# shimboard_revC_V4.net
KiCad netlist of a schematic drawn in EAGLE
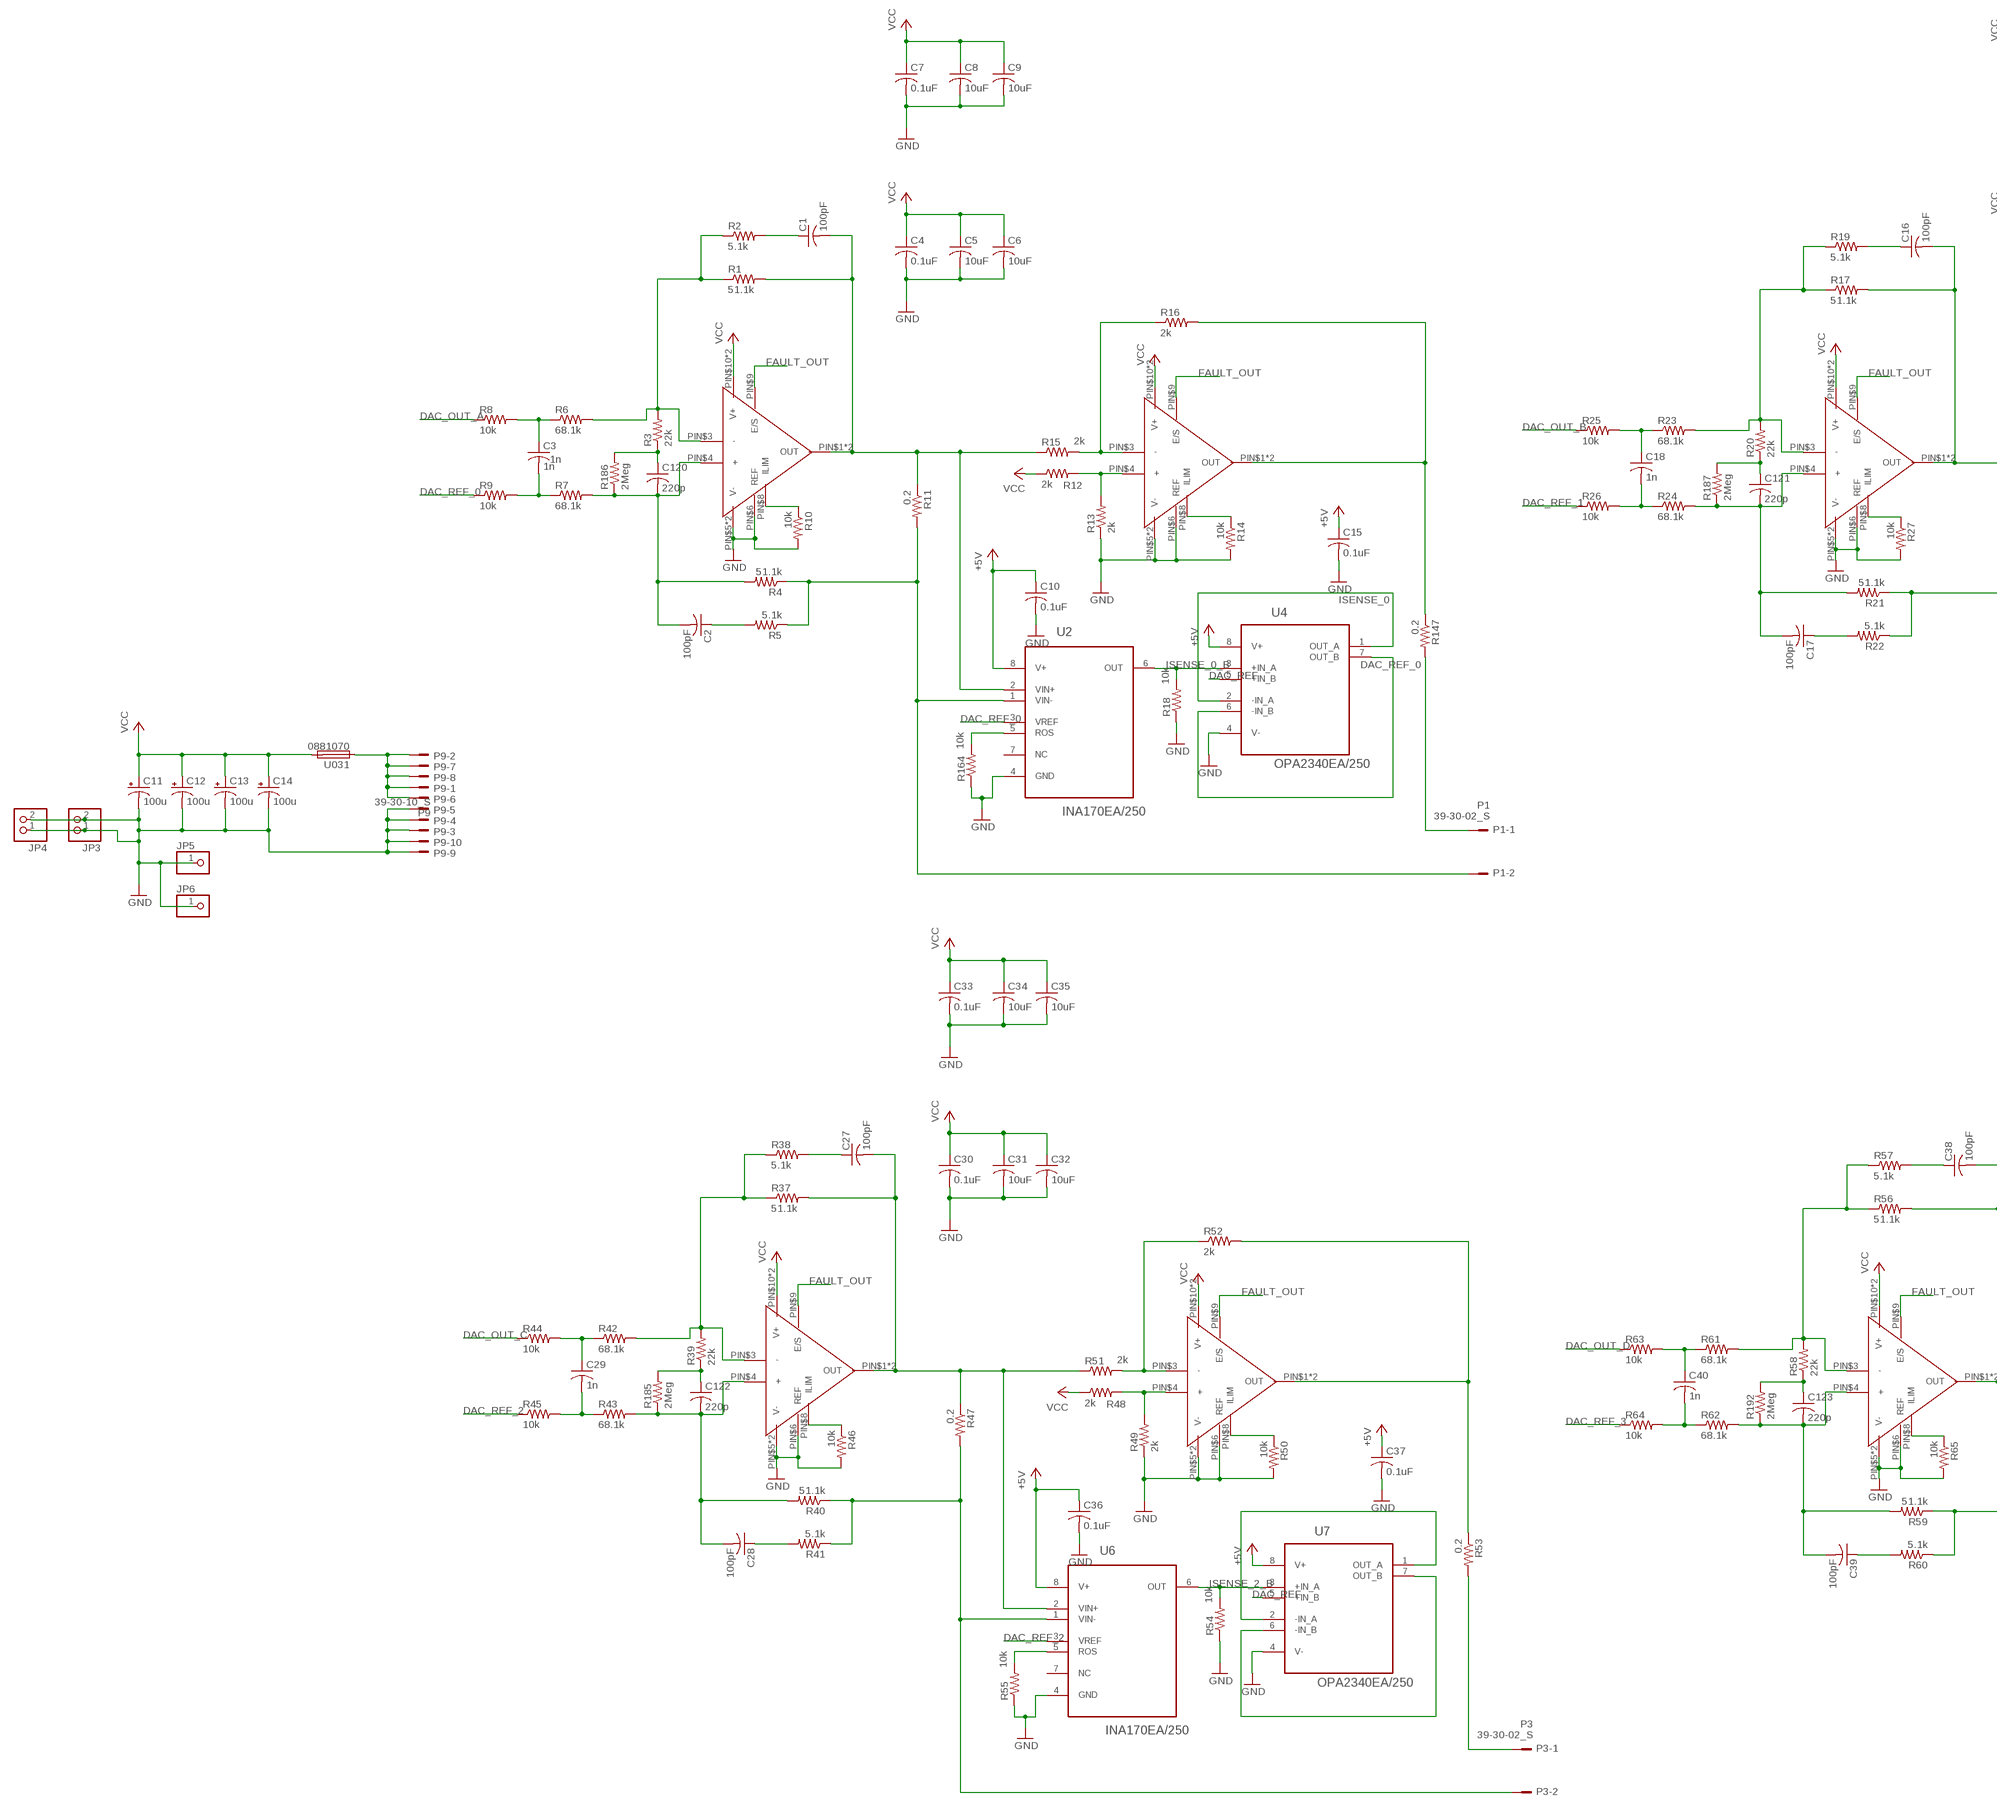
[diagram p0: schematic, sheet 1, part 1 of 3]
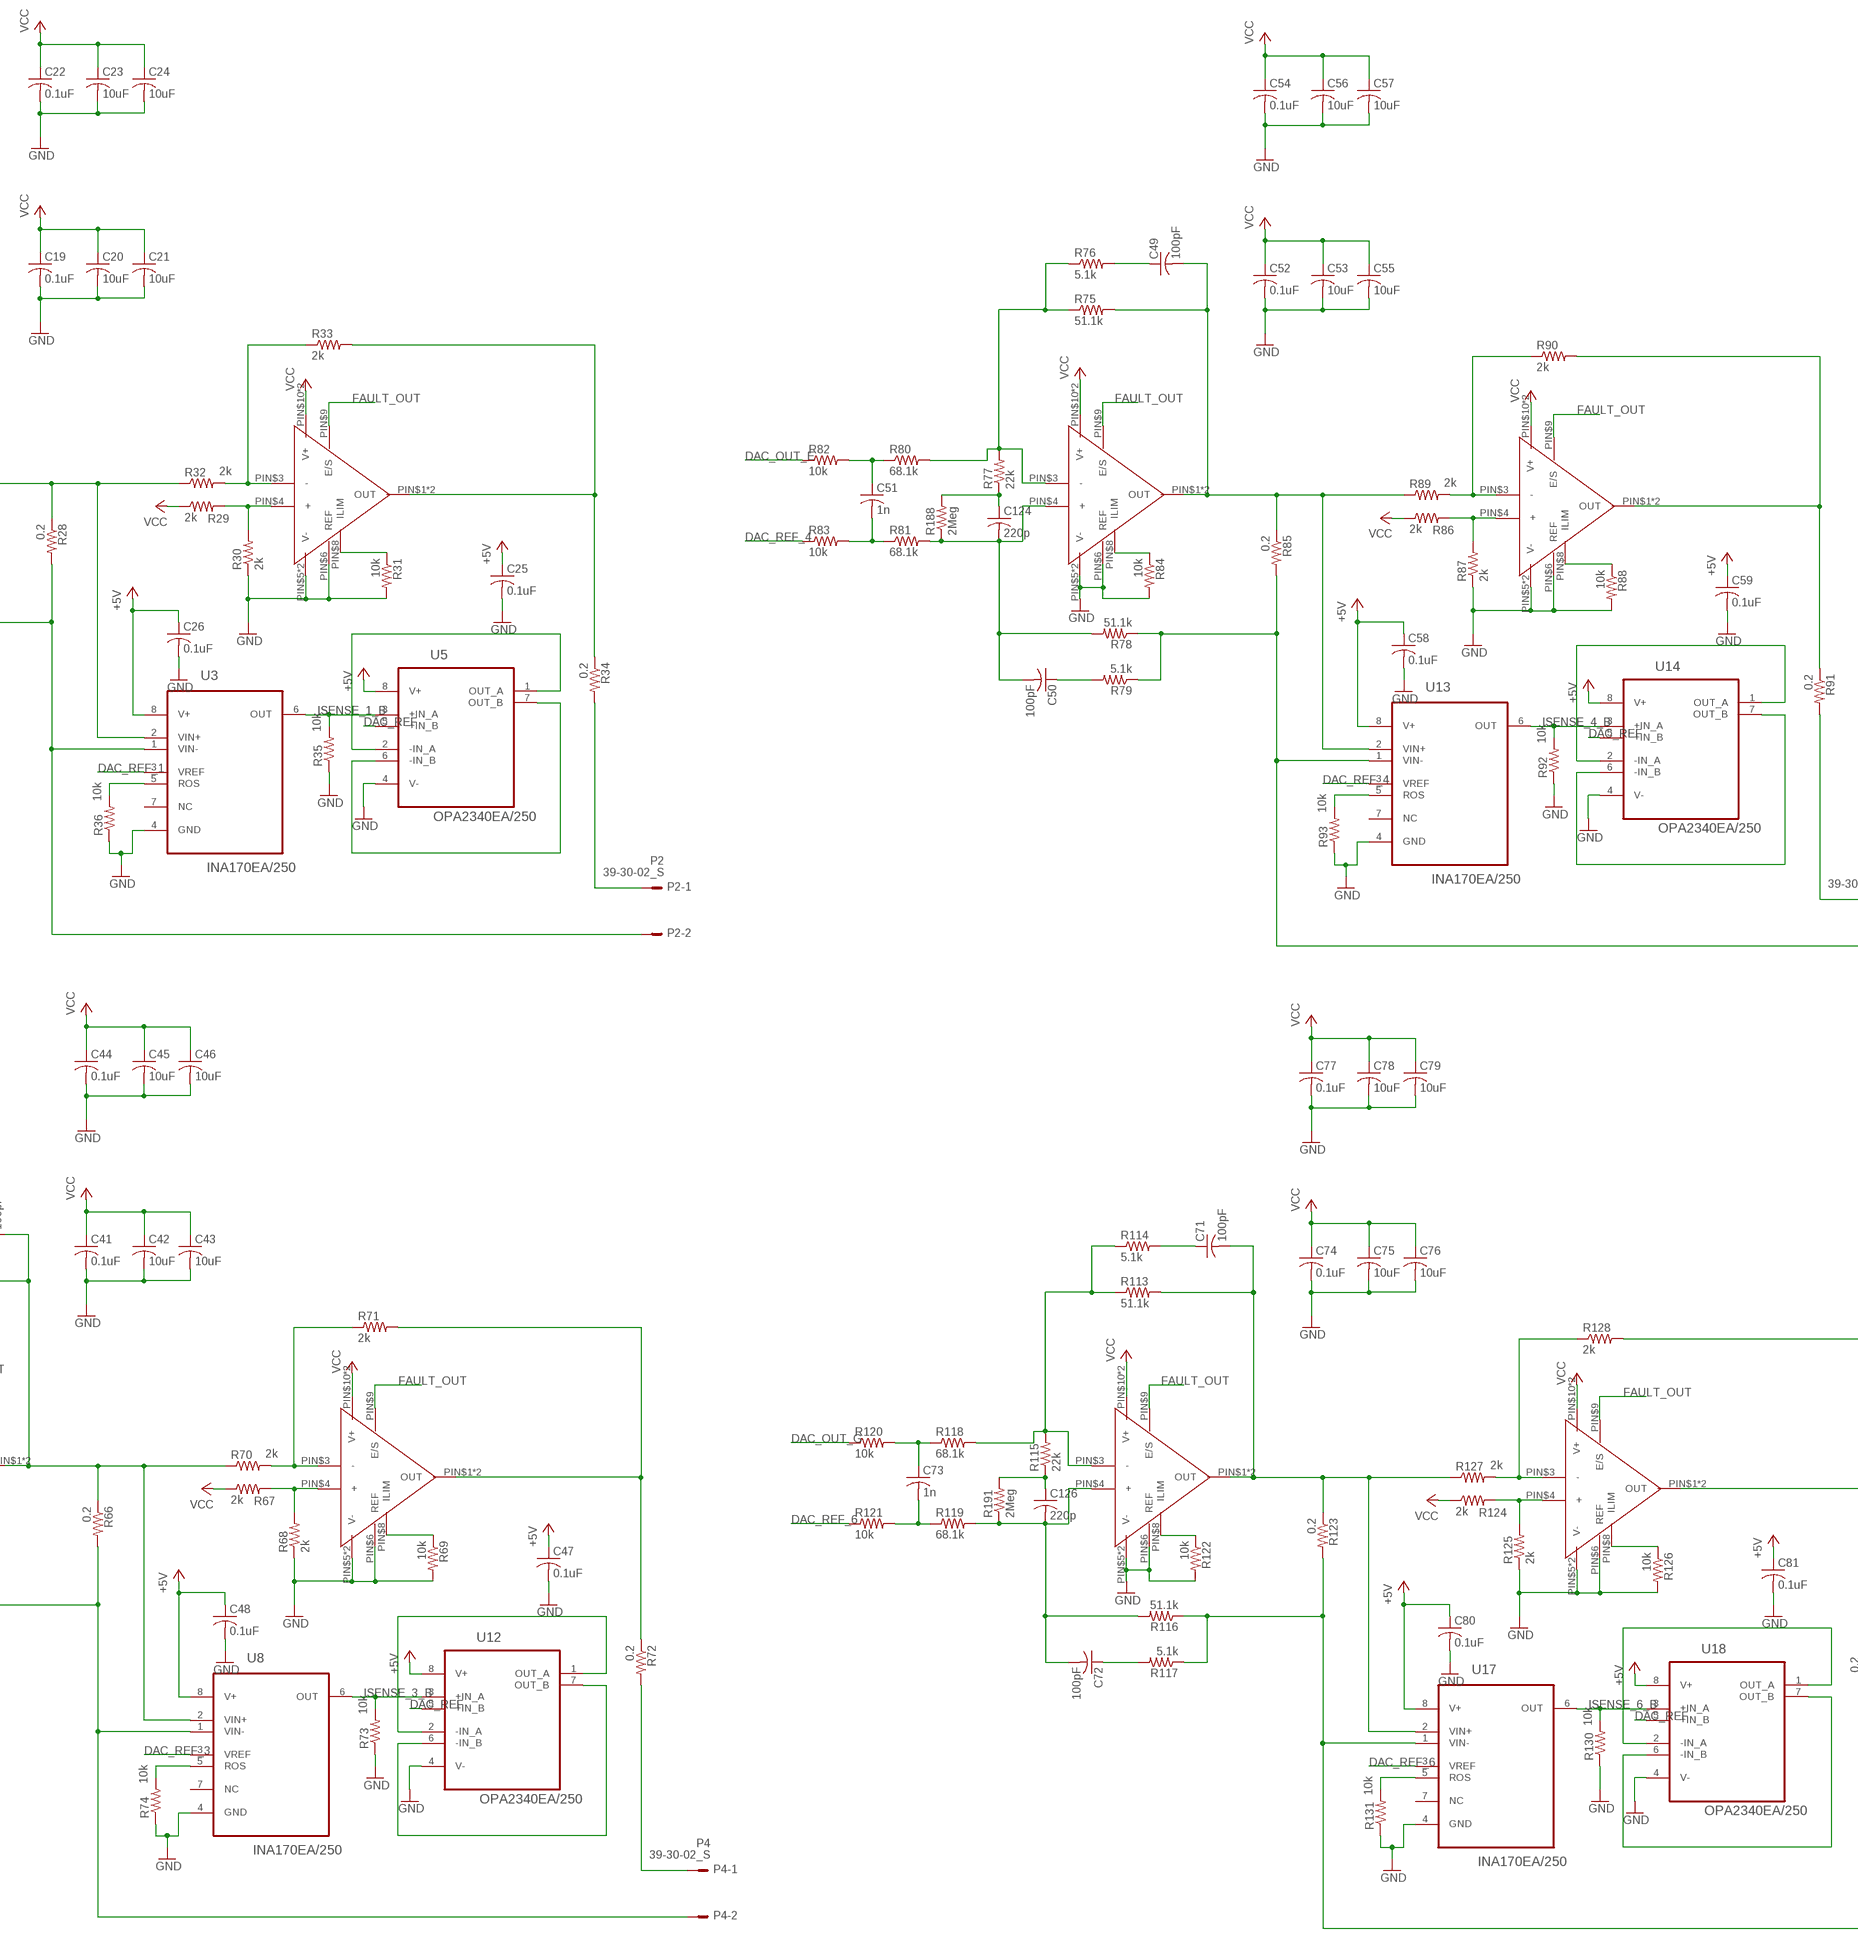
[diagram p1: schematic, sheet 1, part 2 of 3]
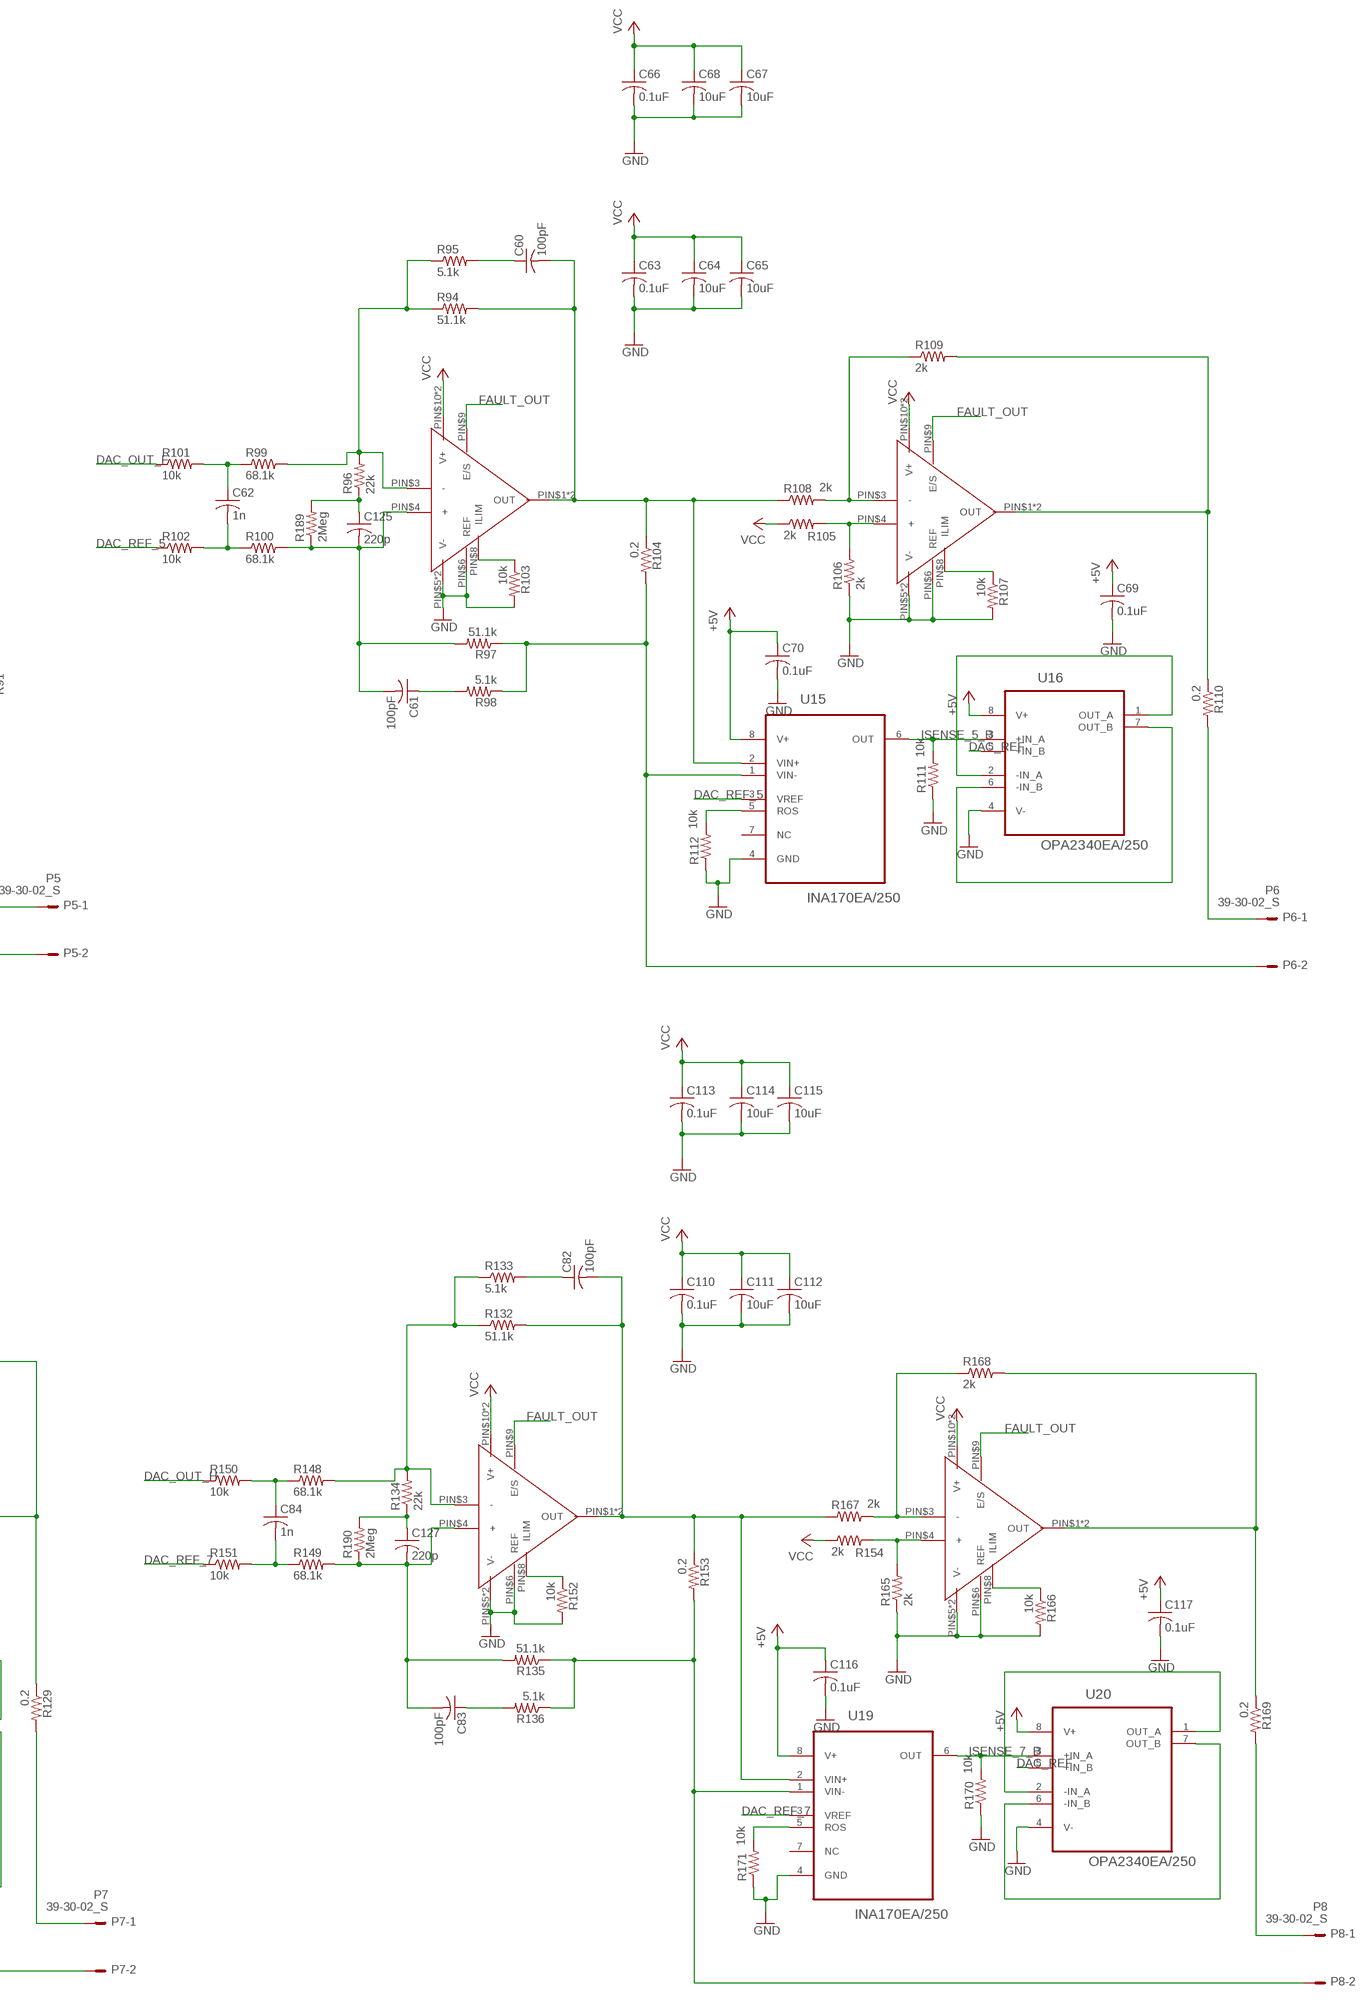
[diagram p2: schematic, sheet 1, part 3 of 3]
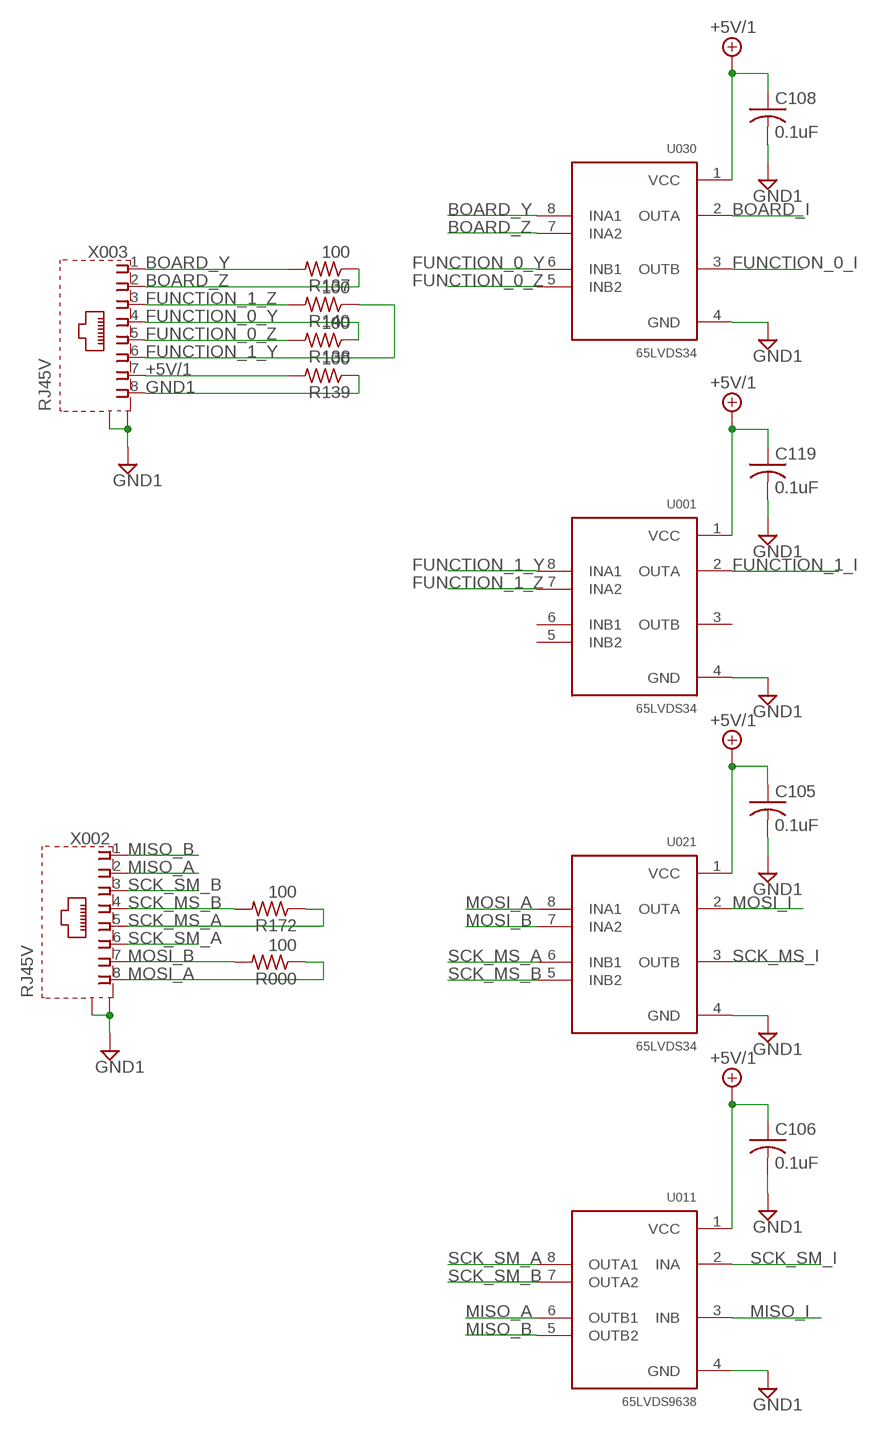
[diagram p3: schematic, sheet 2, part 1 of 2]
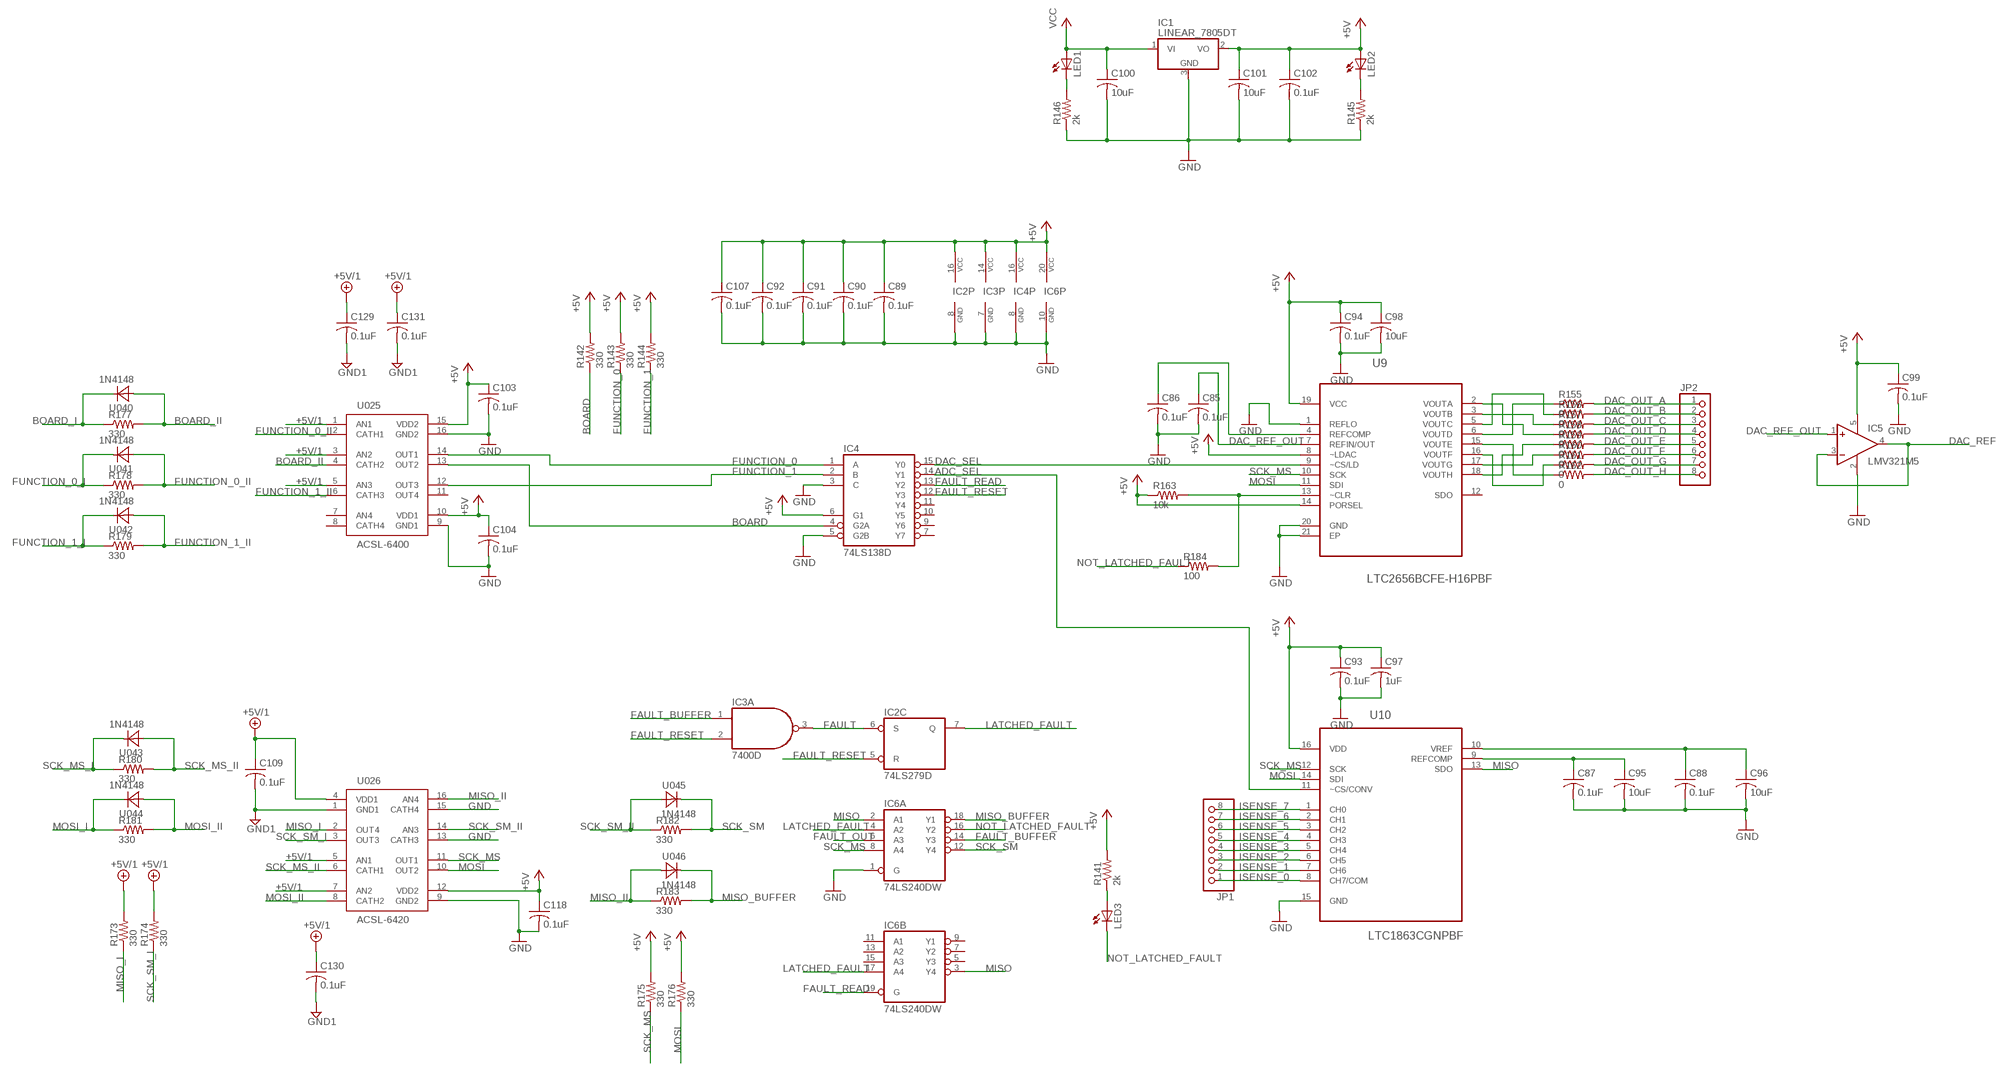
[diagram p4: schematic, sheet 2, part 2 of 2]

(export (version "E")
  (design (tool "Eeschema 10.0.6"))
  (components
    (comp (ref "C1")
      (value "100pF")
      (footprint "eagle-import:C0805")
      (libsource (lib "eagle-import") (part "C-USC0805"))
    )
    (comp (ref "C2")
      (value "100pF")
      (footprint "eagle-import:C0805")
      (libsource (lib "eagle-import") (part "C-USC0805"))
    )
    (comp (ref "C3")
      (value "1n")
      (footprint "eagle-import:C0805")
      (fields (field (name "SPICEPREFIX") "C") (field (name "SPICEPREFIX_1") "1n"))
      (libsource (lib "eagle-import") (part "C-USC0805"))
    )
    (comp (ref "C4")
      (value "0.1uF")
      (footprint "eagle-import:C0805")
      (libsource (lib "eagle-import") (part "C-USC0805"))
    )
    (comp (ref "C5")
      (value "10uF")
      (footprint "eagle-import:C1206")
      (libsource (lib "eagle-import") (part "C-USC1206"))
    )
    (comp (ref "C6")
      (value "10uF")
      (footprint "eagle-import:C1206")
      (libsource (lib "eagle-import") (part "C-USC1206"))
    )
    (comp (ref "C7")
      (value "0.1uF")
      (footprint "eagle-import:C0805")
      (libsource (lib "eagle-import") (part "C-USC0805"))
    )
    (comp (ref "C8")
      (value "10uF")
      (footprint "eagle-import:C1206")
      (libsource (lib "eagle-import") (part "C-USC1206"))
    )
    (comp (ref "C9")
      (value "10uF")
      (footprint "eagle-import:C1206")
      (libsource (lib "eagle-import") (part "C-USC1206"))
    )
    (comp (ref "C10")
      (value "0.1uF")
      (footprint "eagle-import:C0805")
      (libsource (lib "eagle-import") (part "C-USC0805"))
    )
    (comp (ref "C11")
      (value "100u")
      (footprint "eagle-import:D_7343-31W")
      (libsource (lib "eagle-import") (part "CPOL-USD/7343-31W"))
    )
    (comp (ref "C12")
      (value "100u")
      (footprint "eagle-import:D_7343-31W")
      (libsource (lib "eagle-import") (part "CPOL-USD/7343-31W"))
    )
    (comp (ref "C13")
      (value "100u")
      (footprint "eagle-import:D_7343-31W")
      (libsource (lib "eagle-import") (part "CPOL-USD/7343-31W"))
    )
    (comp (ref "C14")
      (value "100u")
      (footprint "eagle-import:D_7343-31W")
      (libsource (lib "eagle-import") (part "CPOL-USD/7343-31W"))
    )
    (comp (ref "C15")
      (value "0.1uF")
      (footprint "eagle-import:C0805")
      (libsource (lib "eagle-import") (part "C-USC0805"))
    )
    (comp (ref "C16")
      (value "100pF")
      (footprint "eagle-import:C0805")
      (libsource (lib "eagle-import") (part "C-USC0805"))
    )
    (comp (ref "C17")
      (value "100pF")
      (footprint "eagle-import:C0805")
      (libsource (lib "eagle-import") (part "C-USC0805"))
    )
    (comp (ref "C18")
      (value "1n")
      (footprint "eagle-import:C0805")
      (libsource (lib "eagle-import") (part "C-USC0805"))
    )
    (comp (ref "C19")
      (value "0.1uF")
      (footprint "eagle-import:C0805")
      (libsource (lib "eagle-import") (part "C-USC0805"))
    )
    (comp (ref "C20")
      (value "10uF")
      (footprint "eagle-import:C1206")
      (libsource (lib "eagle-import") (part "C-USC1206"))
    )
    (comp (ref "C21")
      (value "10uF")
      (footprint "eagle-import:C1206")
      (libsource (lib "eagle-import") (part "C-USC1206"))
    )
    (comp (ref "C22")
      (value "0.1uF")
      (footprint "eagle-import:C0805")
      (libsource (lib "eagle-import") (part "C-USC0805"))
    )
    (comp (ref "C23")
      (value "10uF")
      (footprint "eagle-import:C1206")
      (libsource (lib "eagle-import") (part "C-USC1206"))
    )
    (comp (ref "C24")
      (value "10uF")
      (footprint "eagle-import:C1206")
      (libsource (lib "eagle-import") (part "C-USC1206"))
    )
    (comp (ref "C25")
      (value "0.1uF")
      (footprint "eagle-import:C0805")
      (libsource (lib "eagle-import") (part "C-USC0805"))
    )
    (comp (ref "C26")
      (value "0.1uF")
      (footprint "eagle-import:C0805")
      (libsource (lib "eagle-import") (part "C-USC0805"))
    )
    (comp (ref "C27")
      (value "100pF")
      (footprint "eagle-import:C0805")
      (libsource (lib "eagle-import") (part "C-USC0805"))
    )
    (comp (ref "C28")
      (value "100pF")
      (footprint "eagle-import:C0805")
      (libsource (lib "eagle-import") (part "C-USC0805"))
    )
    (comp (ref "C29")
      (value "1n")
      (footprint "eagle-import:C0805")
      (libsource (lib "eagle-import") (part "C-USC0805"))
    )
    (comp (ref "C30")
      (value "0.1uF")
      (footprint "eagle-import:C0805")
      (libsource (lib "eagle-import") (part "C-USC0805"))
    )
    (comp (ref "C31")
      (value "10uF")
      (footprint "eagle-import:C1206")
      (libsource (lib "eagle-import") (part "C-USC1206"))
    )
    (comp (ref "C32")
      (value "10uF")
      (footprint "eagle-import:C1206")
      (libsource (lib "eagle-import") (part "C-USC1206"))
    )
    (comp (ref "C33")
      (value "0.1uF")
      (footprint "eagle-import:C0805")
      (libsource (lib "eagle-import") (part "C-USC0805"))
    )
    (comp (ref "C34")
      (value "10uF")
      (footprint "eagle-import:C1206")
      (libsource (lib "eagle-import") (part "C-USC1206"))
    )
    (comp (ref "C35")
      (value "10uF")
      (footprint "eagle-import:C1206")
      (libsource (lib "eagle-import") (part "C-USC1206"))
    )
    (comp (ref "C36")
      (value "0.1uF")
      (footprint "eagle-import:C0805")
      (libsource (lib "eagle-import") (part "C-USC0805"))
    )
    (comp (ref "C37")
      (value "0.1uF")
      (footprint "eagle-import:C0805")
      (libsource (lib "eagle-import") (part "C-USC0805"))
    )
    (comp (ref "C38")
      (value "100pF")
      (footprint "eagle-import:C0805")
      (libsource (lib "eagle-import") (part "C-USC0805"))
    )
    (comp (ref "C39")
      (value "100pF")
      (footprint "eagle-import:C0805")
      (libsource (lib "eagle-import") (part "C-USC0805"))
    )
    (comp (ref "C40")
      (value "1n")
      (footprint "eagle-import:C0805")
      (libsource (lib "eagle-import") (part "C-USC0805"))
    )
    (comp (ref "C41")
      (value "0.1uF")
      (footprint "eagle-import:C0805")
      (libsource (lib "eagle-import") (part "C-USC0805"))
    )
    (comp (ref "C42")
      (value "10uF")
      (footprint "eagle-import:C1206")
      (libsource (lib "eagle-import") (part "C-USC1206"))
    )
    (comp (ref "C43")
      (value "10uF")
      (footprint "eagle-import:C1206")
      (libsource (lib "eagle-import") (part "C-USC1206"))
    )
    (comp (ref "C44")
      (value "0.1uF")
      (footprint "eagle-import:C0805")
      (libsource (lib "eagle-import") (part "C-USC0805"))
    )
    (comp (ref "C45")
      (value "10uF")
      (footprint "eagle-import:C1206")
      (libsource (lib "eagle-import") (part "C-USC1206"))
    )
    (comp (ref "C46")
      (value "10uF")
      (footprint "eagle-import:C1206")
      (libsource (lib "eagle-import") (part "C-USC1206"))
    )
    (comp (ref "C47")
      (value "0.1uF")
      (footprint "eagle-import:C0805")
      (libsource (lib "eagle-import") (part "C-USC0805"))
    )
    (comp (ref "C48")
      (value "0.1uF")
      (footprint "eagle-import:C0805")
      (libsource (lib "eagle-import") (part "C-USC0805"))
    )
    (comp (ref "C49")
      (value "100pF")
      (footprint "eagle-import:C0805")
      (libsource (lib "eagle-import") (part "C-USC0805"))
    )
    (comp (ref "C50")
      (value "100pF")
      (footprint "eagle-import:C0805")
      (libsource (lib "eagle-import") (part "C-USC0805"))
    )
    (comp (ref "C51")
      (value "1n")
      (footprint "eagle-import:C0805")
      (libsource (lib "eagle-import") (part "C-USC0805"))
    )
    (comp (ref "C52")
      (value "0.1uF")
      (footprint "eagle-import:C0805")
      (libsource (lib "eagle-import") (part "C-USC0805"))
    )
    (comp (ref "C53")
      (value "10uF")
      (footprint "eagle-import:C1206")
      (libsource (lib "eagle-import") (part "C-USC1206"))
    )
    (comp (ref "C54")
      (value "0.1uF")
      (footprint "eagle-import:C0805")
      (libsource (lib "eagle-import") (part "C-USC0805"))
    )
    (comp (ref "C55")
      (value "10uF")
      (footprint "eagle-import:C1206")
      (libsource (lib "eagle-import") (part "C-USC1206"))
    )
    (comp (ref "C56")
      (value "10uF")
      (footprint "eagle-import:C1206")
      (libsource (lib "eagle-import") (part "C-USC1206"))
    )
    (comp (ref "C57")
      (value "10uF")
      (footprint "eagle-import:C1206")
      (libsource (lib "eagle-import") (part "C-USC1206"))
    )
    (comp (ref "C58")
      (value "0.1uF")
      (footprint "eagle-import:C0805")
      (libsource (lib "eagle-import") (part "C-USC0805"))
    )
    (comp (ref "C59")
      (value "0.1uF")
      (footprint "eagle-import:C0805")
      (libsource (lib "eagle-import") (part "C-USC0805"))
    )
    (comp (ref "C60")
      (value "100pF")
      (footprint "eagle-import:C0805")
      (libsource (lib "eagle-import") (part "C-USC0805"))
    )
    (comp (ref "C61")
      (value "100pF")
      (footprint "eagle-import:C0805")
      (libsource (lib "eagle-import") (part "C-USC0805"))
    )
    (comp (ref "C62")
      (value "1n")
      (footprint "eagle-import:C0805")
      (libsource (lib "eagle-import") (part "C-USC0805"))
    )
    (comp (ref "C63")
      (value "0.1uF")
      (footprint "eagle-import:C0805")
      (libsource (lib "eagle-import") (part "C-USC0805"))
    )
    (comp (ref "C64")
      (value "10uF")
      (footprint "eagle-import:C1206")
      (libsource (lib "eagle-import") (part "C-USC1206"))
    )
    (comp (ref "C65")
      (value "10uF")
      (footprint "eagle-import:C1206")
      (libsource (lib "eagle-import") (part "C-USC1206"))
    )
    (comp (ref "C66")
      (value "0.1uF")
      (footprint "eagle-import:C0805")
      (libsource (lib "eagle-import") (part "C-USC0805"))
    )
    (comp (ref "C67")
      (value "10uF")
      (footprint "eagle-import:C1206")
      (libsource (lib "eagle-import") (part "C-USC1206"))
    )
    (comp (ref "C68")
      (value "10uF")
      (footprint "eagle-import:C1206")
      (libsource (lib "eagle-import") (part "C-USC1206"))
    )
    (comp (ref "C69")
      (value "0.1uF")
      (footprint "eagle-import:C0805")
      (libsource (lib "eagle-import") (part "C-USC0805"))
    )
    (comp (ref "C70")
      (value "0.1uF")
      (footprint "eagle-import:C0805")
      (libsource (lib "eagle-import") (part "C-USC0805"))
    )
    (comp (ref "C71")
      (value "100pF")
      (footprint "eagle-import:C0805")
      (libsource (lib "eagle-import") (part "C-USC0805"))
    )
    (comp (ref "C72")
      (value "100pF")
      (footprint "eagle-import:C0805")
      (libsource (lib "eagle-import") (part "C-USC0805"))
    )
    (comp (ref "C73")
      (value "1n")
      (footprint "eagle-import:C0805")
      (libsource (lib "eagle-import") (part "C-USC0805"))
    )
    (comp (ref "C74")
      (value "0.1uF")
      (footprint "eagle-import:C0805")
      (libsource (lib "eagle-import") (part "C-USC0805"))
    )
    (comp (ref "C75")
      (value "10uF")
      (footprint "eagle-import:C1206")
      (libsource (lib "eagle-import") (part "C-USC1206"))
    )
    (comp (ref "C76")
      (value "10uF")
      (footprint "eagle-import:C1206")
      (libsource (lib "eagle-import") (part "C-USC1206"))
    )
    (comp (ref "C77")
      (value "0.1uF")
      (footprint "eagle-import:C0805")
      (libsource (lib "eagle-import") (part "C-USC0805"))
    )
    (comp (ref "C78")
      (value "10uF")
      (footprint "eagle-import:C1206")
      (libsource (lib "eagle-import") (part "C-USC1206"))
    )
    (comp (ref "C79")
      (value "10uF")
      (footprint "eagle-import:C1206")
      (libsource (lib "eagle-import") (part "C-USC1206"))
    )
    (comp (ref "C80")
      (value "0.1uF")
      (footprint "eagle-import:C0805")
      (libsource (lib "eagle-import") (part "C-USC0805"))
    )
    (comp (ref "C81")
      (value "0.1uF")
      (footprint "eagle-import:C0805")
      (libsource (lib "eagle-import") (part "C-USC0805"))
    )
    (comp (ref "C82")
      (value "100pF")
      (footprint "eagle-import:C0805")
      (libsource (lib "eagle-import") (part "C-USC0805"))
    )
    (comp (ref "C83")
      (value "100pF")
      (footprint "eagle-import:C0805")
      (libsource (lib "eagle-import") (part "C-USC0805"))
    )
    (comp (ref "C84")
      (value "1n")
      (footprint "eagle-import:C0805")
      (libsource (lib "eagle-import") (part "C-USC0805"))
    )
    (comp (ref "C110")
      (value "0.1uF")
      (footprint "eagle-import:C0805")
      (libsource (lib "eagle-import") (part "C-USC0805"))
    )
    (comp (ref "C111")
      (value "10uF")
      (footprint "eagle-import:C1206")
      (libsource (lib "eagle-import") (part "C-USC1206"))
    )
    (comp (ref "C112")
      (value "10uF")
      (footprint "eagle-import:C1206")
      (libsource (lib "eagle-import") (part "C-USC1206"))
    )
    (comp (ref "C113")
      (value "0.1uF")
      (footprint "eagle-import:C0805")
      (libsource (lib "eagle-import") (part "C-USC0805"))
    )
    (comp (ref "C114")
      (value "10uF")
      (footprint "eagle-import:C1206")
      (libsource (lib "eagle-import") (part "C-USC1206"))
    )
    (comp (ref "C115")
      (value "10uF")
      (footprint "eagle-import:C1206")
      (libsource (lib "eagle-import") (part "C-USC1206"))
    )
    (comp (ref "C116")
      (value "0.1uF")
      (footprint "eagle-import:C0805")
      (libsource (lib "eagle-import") (part "C-USC0805"))
    )
    (comp (ref "C117")
      (value "0.1uF")
      (footprint "eagle-import:C0805")
      (libsource (lib "eagle-import") (part "C-USC0805"))
    )
    (comp (ref "C120")
      (value "220p")
      (footprint "eagle-import:C0805")
      (libsource (lib "eagle-import") (part "C-USC0805"))
    )
    (comp (ref "C121")
      (value "220p")
      (footprint "eagle-import:C0805")
      (libsource (lib "eagle-import") (part "C-USC0805"))
    )
    (comp (ref "C122")
      (value "220p")
      (footprint "eagle-import:C0805")
      (libsource (lib "eagle-import") (part "C-USC0805"))
    )
    (comp (ref "C123")
      (value "220p")
      (footprint "eagle-import:C0805")
      (libsource (lib "eagle-import") (part "C-USC0805"))
    )
    (comp (ref "C124")
      (value "220p")
      (footprint "eagle-import:C0805")
      (libsource (lib "eagle-import") (part "C-USC0805"))
    )
    (comp (ref "C125")
      (value "220p")
      (footprint "eagle-import:C0805")
      (libsource (lib "eagle-import") (part "C-USC0805"))
    )
    (comp (ref "C126")
      (value "220p")
      (footprint "eagle-import:C0805")
      (libsource (lib "eagle-import") (part "C-USC0805"))
    )
    (comp (ref "C127")
      (value "220p")
      (footprint "eagle-import:C0805")
      (libsource (lib "eagle-import") (part "C-USC0805"))
    )
    (comp (ref "JP3")
      (value "PINHD-1X2")
      (footprint "eagle-import:1X02")
      (libsource (lib "eagle-import") (part "PINHD-1X2"))
    )
    (comp (ref "JP4")
      (value "PINHD-1X2")
      (footprint "eagle-import:1X02")
      (libsource (lib "eagle-import") (part "PINHD-1X2"))
    )
    (comp (ref "JP5")
      (value "PINHD-1X1")
      (footprint "eagle-import:1X01")
      (libsource (lib "eagle-import") (part "PINHD-1X1"))
    )
    (comp (ref "JP6")
      (value "PINHD-1X1")
      (footprint "eagle-import:1X01")
      (libsource (lib "eagle-import") (part "PINHD-1X1"))
    )
    (comp (ref "P1")
      (value "39-30-02_S")
      (footprint "eagle-import:39-30-_02_")
      (libsource (lib "eagle-import") (part "39-30-?02?_S"))
    )
    (comp (ref "P2")
      (value "39-30-02_S")
      (footprint "eagle-import:39-30-_02_")
      (libsource (lib "eagle-import") (part "39-30-?02?_S"))
    )
    (comp (ref "P3")
      (value "39-30-02_S")
      (footprint "eagle-import:39-30-_02_")
      (libsource (lib "eagle-import") (part "39-30-?02?_S"))
    )
    (comp (ref "P4")
      (value "39-30-02_S")
      (footprint "eagle-import:39-30-_02_")
      (libsource (lib "eagle-import") (part "39-30-?02?_S"))
    )
    (comp (ref "P5")
      (value "39-30-02_S")
      (footprint "eagle-import:39-30-_02_")
      (libsource (lib "eagle-import") (part "39-30-?02?_S"))
    )
    (comp (ref "P6")
      (value "39-30-02_S")
      (footprint "eagle-import:39-30-_02_")
      (libsource (lib "eagle-import") (part "39-30-?02?_S"))
    )
    (comp (ref "P7")
      (value "39-30-02_S")
      (footprint "eagle-import:39-30-_02_")
      (libsource (lib "eagle-import") (part "39-30-?02?_S"))
    )
    (comp (ref "P8")
      (value "39-30-02_S")
      (footprint "eagle-import:39-30-_02_")
      (libsource (lib "eagle-import") (part "39-30-?02?_S"))
    )
    (comp (ref "P9")
      (value "39-30-10_S")
      (footprint "eagle-import:39-30-_10_")
      (libsource (lib "eagle-import") (part "39-30-?10?_S"))
    )
    (comp (ref "R1")
      (value "51.1k")
      (footprint "eagle-import:R0805")
      (libsource (lib "eagle-import") (part "R-US_R0805"))
    )
    (comp (ref "R2")
      (value "5.1k")
      (footprint "eagle-import:R0805")
      (libsource (lib "eagle-import") (part "R-US_R0805"))
    )
    (comp (ref "R3")
      (value "22k")
      (footprint "eagle-import:R0805")
      (libsource (lib "eagle-import") (part "R-US_R0805"))
    )
    (comp (ref "R4")
      (value "51.1k")
      (footprint "eagle-import:R0805")
      (libsource (lib "eagle-import") (part "R-US_R0805"))
    )
    (comp (ref "R5")
      (value "5.1k")
      (footprint "eagle-import:R0805")
      (libsource (lib "eagle-import") (part "R-US_R0805"))
    )
    (comp (ref "R6")
      (value "68.1k")
      (footprint "eagle-import:R0805")
      (libsource (lib "eagle-import") (part "R-US_R0805"))
    )
    (comp (ref "R7")
      (value "68.1k")
      (footprint "eagle-import:R0805")
      (libsource (lib "eagle-import") (part "R-US_R0805"))
    )
    (comp (ref "R8")
      (value "10k")
      (footprint "eagle-import:R0805")
      (libsource (lib "eagle-import") (part "R-US_R0805"))
    )
    (comp (ref "R9")
      (value "10k")
      (footprint "eagle-import:R0805")
      (libsource (lib "eagle-import") (part "R-US_R0805"))
    )
    (comp (ref "R10")
      (value "10k")
      (footprint "eagle-import:R0805")
      (libsource (lib "eagle-import") (part "R-US_R0805"))
    )
    (comp (ref "R11")
      (value "0.2")
      (footprint "eagle-import:R4527")
      (libsource (lib "eagle-import") (part "R-US_R4527"))
    )
    (comp (ref "R12")
      (value "2k")
      (footprint "eagle-import:M0805")
      (libsource (lib "eagle-import") (part "R-US_M0805"))
    )
    (comp (ref "R13")
      (value "2k")
      (footprint "eagle-import:R0805")
      (libsource (lib "eagle-import") (part "R-US_R0805"))
    )
    (comp (ref "R14")
      (value "10k")
      (footprint "eagle-import:R0805")
      (libsource (lib "eagle-import") (part "R-US_R0805"))
    )
    (comp (ref "R15")
      (value "2k")
      (footprint "eagle-import:R0805")
      (libsource (lib "eagle-import") (part "R-US_R0805"))
    )
    (comp (ref "R16")
      (value "2k")
      (footprint "eagle-import:R0805")
      (libsource (lib "eagle-import") (part "R-US_R0805"))
    )
    (comp (ref "R17")
      (value "51.1k")
      (footprint "eagle-import:R0805")
      (libsource (lib "eagle-import") (part "R-US_R0805"))
    )
    (comp (ref "R18")
      (value "10k")
      (footprint "eagle-import:R0805")
      (libsource (lib "eagle-import") (part "R-US_R0805"))
    )
    (comp (ref "R19")
      (value "5.1k")
      (footprint "eagle-import:R0805")
      (libsource (lib "eagle-import") (part "R-US_R0805"))
    )
    (comp (ref "R20")
      (value "22k")
      (footprint "eagle-import:R0805")
      (libsource (lib "eagle-import") (part "R-US_R0805"))
    )
    (comp (ref "R21")
      (value "51.1k")
      (footprint "eagle-import:R0805")
      (libsource (lib "eagle-import") (part "R-US_R0805"))
    )
    (comp (ref "R22")
      (value "5.1k")
      (footprint "eagle-import:R0805")
      (libsource (lib "eagle-import") (part "R-US_R0805"))
    )
    (comp (ref "R23")
      (value "68.1k")
      (footprint "eagle-import:R0805")
      (libsource (lib "eagle-import") (part "R-US_R0805"))
    )
    (comp (ref "R24")
      (value "68.1k")
      (footprint "eagle-import:R0805")
      (libsource (lib "eagle-import") (part "R-US_R0805"))
    )
    (comp (ref "R25")
      (value "10k")
      (footprint "eagle-import:R0805")
      (libsource (lib "eagle-import") (part "R-US_R0805"))
    )
    (comp (ref "R26")
      (value "10k")
      (footprint "eagle-import:R0805")
      (libsource (lib "eagle-import") (part "R-US_R0805"))
    )
    (comp (ref "R27")
      (value "10k")
      (footprint "eagle-import:R0805")
      (libsource (lib "eagle-import") (part "R-US_R0805"))
    )
    (comp (ref "R28")
      (value "0.2")
      (footprint "eagle-import:R4527")
      (libsource (lib "eagle-import") (part "R-US_R4527"))
    )
    (comp (ref "R29")
      (value "2k")
      (footprint "eagle-import:M0805")
      (libsource (lib "eagle-import") (part "R-US_M0805"))
    )
    (comp (ref "R30")
      (value "2k")
      (footprint "eagle-import:R0805")
      (libsource (lib "eagle-import") (part "R-US_R0805"))
    )
    (comp (ref "R31")
      (value "10k")
      (footprint "eagle-import:R0805")
      (libsource (lib "eagle-import") (part "R-US_R0805"))
    )
    (comp (ref "R32")
      (value "2k")
      (footprint "eagle-import:R0805")
      (libsource (lib "eagle-import") (part "R-US_R0805"))
    )
    (comp (ref "R33")
      (value "2k")
      (footprint "eagle-import:R0805")
      (libsource (lib "eagle-import") (part "R-US_R0805"))
    )
    (comp (ref "R34")
      (value "0.2")
      (footprint "eagle-import:R4527")
      (libsource (lib "eagle-import") (part "R-US_R4527"))
    )
    (comp (ref "R35")
      (value "10k")
      (footprint "eagle-import:R0805")
      (libsource (lib "eagle-import") (part "R-US_R0805"))
    )
    (comp (ref "R36")
      (value "10k")
      (footprint "eagle-import:R0805")
      (libsource (lib "eagle-import") (part "R-US_R0805"))
    )
    (comp (ref "R37")
      (value "51.1k")
      (footprint "eagle-import:R0805")
      (libsource (lib "eagle-import") (part "R-US_R0805"))
    )
    (comp (ref "R38")
      (value "5.1k")
      (footprint "eagle-import:R0805")
      (libsource (lib "eagle-import") (part "R-US_R0805"))
    )
    (comp (ref "R39")
      (value "22k")
      (footprint "eagle-import:R0805")
      (libsource (lib "eagle-import") (part "R-US_R0805"))
    )
    (comp (ref "R40")
      (value "51.1k")
      (footprint "eagle-import:R0805")
      (libsource (lib "eagle-import") (part "R-US_R0805"))
    )
    (comp (ref "R41")
      (value "5.1k")
      (footprint "eagle-import:R0805")
      (libsource (lib "eagle-import") (part "R-US_R0805"))
    )
    (comp (ref "R42")
      (value "68.1k")
      (footprint "eagle-import:R0805")
      (libsource (lib "eagle-import") (part "R-US_R0805"))
    )
    (comp (ref "R43")
      (value "68.1k")
      (footprint "eagle-import:R0805")
      (libsource (lib "eagle-import") (part "R-US_R0805"))
    )
    (comp (ref "R44")
      (value "10k")
      (footprint "eagle-import:R0805")
      (libsource (lib "eagle-import") (part "R-US_R0805"))
    )
    (comp (ref "R45")
      (value "10k")
      (footprint "eagle-import:R0805")
      (libsource (lib "eagle-import") (part "R-US_R0805"))
    )
    (comp (ref "R46")
      (value "10k")
      (footprint "eagle-import:R0805")
      (libsource (lib "eagle-import") (part "R-US_R0805"))
    )
    (comp (ref "R47")
      (value "0.2")
      (footprint "eagle-import:R4527")
      (libsource (lib "eagle-import") (part "R-US_R4527"))
    )
    (comp (ref "R48")
      (value "2k")
      (footprint "eagle-import:M0805")
      (libsource (lib "eagle-import") (part "R-US_M0805"))
    )
    (comp (ref "R49")
      (value "2k")
      (footprint "eagle-import:R0805")
      (libsource (lib "eagle-import") (part "R-US_R0805"))
    )
    (comp (ref "R50")
      (value "10k")
      (footprint "eagle-import:R0805")
      (libsource (lib "eagle-import") (part "R-US_R0805"))
    )
    (comp (ref "R51")
      (value "2k")
      (footprint "eagle-import:R0805")
      (libsource (lib "eagle-import") (part "R-US_R0805"))
    )
    (comp (ref "R52")
      (value "2k")
      (footprint "eagle-import:R0805")
      (libsource (lib "eagle-import") (part "R-US_R0805"))
    )
    (comp (ref "R53")
      (value "0.2")
      (footprint "eagle-import:R4527")
      (libsource (lib "eagle-import") (part "R-US_R4527"))
    )
    (comp (ref "R54")
      (value "10k")
      (footprint "eagle-import:R0805")
      (libsource (lib "eagle-import") (part "R-US_R0805"))
    )
    (comp (ref "R55")
      (value "10k")
      (footprint "eagle-import:R0805")
      (libsource (lib "eagle-import") (part "R-US_R0805"))
    )
    (comp (ref "R56")
      (value "51.1k")
      (footprint "eagle-import:R0805")
      (libsource (lib "eagle-import") (part "R-US_R0805"))
    )
    (comp (ref "R57")
      (value "5.1k")
      (footprint "eagle-import:R0805")
      (libsource (lib "eagle-import") (part "R-US_R0805"))
    )
    (comp (ref "R58")
      (value "22k")
      (footprint "eagle-import:R0805")
      (libsource (lib "eagle-import") (part "R-US_R0805"))
    )
    (comp (ref "R59")
      (value "51.1k")
      (footprint "eagle-import:R0805")
      (libsource (lib "eagle-import") (part "R-US_R0805"))
    )
    (comp (ref "R60")
      (value "5.1k")
      (footprint "eagle-import:R0805")
      (libsource (lib "eagle-import") (part "R-US_R0805"))
    )
    (comp (ref "R61")
      (value "68.1k")
      (footprint "eagle-import:R0805")
      (libsource (lib "eagle-import") (part "R-US_R0805"))
    )
    (comp (ref "R62")
      (value "68.1k")
      (footprint "eagle-import:R0805")
      (libsource (lib "eagle-import") (part "R-US_R0805"))
    )
    (comp (ref "R63")
      (value "10k")
      (footprint "eagle-import:R0805")
      (libsource (lib "eagle-import") (part "R-US_R0805"))
    )
    (comp (ref "R64")
      (value "10k")
      (footprint "eagle-import:R0805")
      (libsource (lib "eagle-import") (part "R-US_R0805"))
    )
    (comp (ref "R65")
      (value "10k")
      (footprint "eagle-import:R0805")
      (libsource (lib "eagle-import") (part "R-US_R0805"))
    )
    (comp (ref "R66")
      (value "0.2")
      (footprint "eagle-import:R4527")
      (libsource (lib "eagle-import") (part "R-US_R4527"))
    )
    (comp (ref "R67")
      (value "2k")
      (footprint "eagle-import:M0805")
      (libsource (lib "eagle-import") (part "R-US_M0805"))
    )
    (comp (ref "R68")
      (value "2k")
      (footprint "eagle-import:R0805")
      (libsource (lib "eagle-import") (part "R-US_R0805"))
    )
    (comp (ref "R69")
      (value "10k")
      (footprint "eagle-import:R0805")
      (libsource (lib "eagle-import") (part "R-US_R0805"))
    )
    (comp (ref "R70")
      (value "2k")
      (footprint "eagle-import:R0805")
      (libsource (lib "eagle-import") (part "R-US_R0805"))
    )
    (comp (ref "R71")
      (value "2k")
      (footprint "eagle-import:R0805")
      (libsource (lib "eagle-import") (part "R-US_R0805"))
    )
    (comp (ref "R72")
      (value "0.2")
      (footprint "eagle-import:R4527")
      (libsource (lib "eagle-import") (part "R-US_R4527"))
    )
    (comp (ref "R73")
      (value "10k")
      (footprint "eagle-import:R0805")
      (libsource (lib "eagle-import") (part "R-US_R0805"))
    )
    (comp (ref "R74")
      (value "10k")
      (footprint "eagle-import:R0805")
      (libsource (lib "eagle-import") (part "R-US_R0805"))
    )
    (comp (ref "R75")
      (value "51.1k")
      (footprint "eagle-import:R0805")
      (libsource (lib "eagle-import") (part "R-US_R0805"))
    )
    (comp (ref "R76")
      (value "5.1k")
      (footprint "eagle-import:R0805")
      (libsource (lib "eagle-import") (part "R-US_R0805"))
    )
    (comp (ref "R77")
      (value "22k")
      (footprint "eagle-import:R0805")
      (libsource (lib "eagle-import") (part "R-US_R0805"))
    )
    (comp (ref "R78")
      (value "51.1k")
      (footprint "eagle-import:R0805")
      (libsource (lib "eagle-import") (part "R-US_R0805"))
    )
    (comp (ref "R79")
      (value "5.1k")
      (footprint "eagle-import:R0805")
      (libsource (lib "eagle-import") (part "R-US_R0805"))
    )
    (comp (ref "R80")
      (value "68.1k")
      (footprint "eagle-import:R0805")
      (libsource (lib "eagle-import") (part "R-US_R0805"))
    )
    (comp (ref "R81")
      (value "68.1k")
      (footprint "eagle-import:R0805")
      (libsource (lib "eagle-import") (part "R-US_R0805"))
    )
    (comp (ref "R82")
      (value "10k")
      (footprint "eagle-import:R0805")
      (libsource (lib "eagle-import") (part "R-US_R0805"))
    )
    (comp (ref "R83")
      (value "10k")
      (footprint "eagle-import:R0805")
      (libsource (lib "eagle-import") (part "R-US_R0805"))
    )
    (comp (ref "R84")
      (value "10k")
      (footprint "eagle-import:R0805")
      (libsource (lib "eagle-import") (part "R-US_R0805"))
    )
    (comp (ref "R85")
      (value "0.2")
      (footprint "eagle-import:R4527")
      (libsource (lib "eagle-import") (part "R-US_R4527"))
    )
    (comp (ref "R86")
      (value "2k")
      (footprint "eagle-import:M0805")
      (libsource (lib "eagle-import") (part "R-US_M0805"))
    )
    (comp (ref "R87")
      (value "2k")
      (footprint "eagle-import:R0805")
      (libsource (lib "eagle-import") (part "R-US_R0805"))
    )
    (comp (ref "R88")
      (value "10k")
      (footprint "eagle-import:R0805")
      (libsource (lib "eagle-import") (part "R-US_R0805"))
    )
    (comp (ref "R89")
      (value "2k")
      (footprint "eagle-import:R0805")
      (libsource (lib "eagle-import") (part "R-US_R0805"))
    )
    (comp (ref "R90")
      (value "2k")
      (footprint "eagle-import:R0805")
      (libsource (lib "eagle-import") (part "R-US_R0805"))
    )
    (comp (ref "R91")
      (value "0.2")
      (footprint "eagle-import:R4527")
      (libsource (lib "eagle-import") (part "R-US_R4527"))
    )
    (comp (ref "R92")
      (value "10k")
      (footprint "eagle-import:R0805")
      (libsource (lib "eagle-import") (part "R-US_R0805"))
    )
    (comp (ref "R93")
      (value "10k")
      (footprint "eagle-import:R0805")
      (libsource (lib "eagle-import") (part "R-US_R0805"))
    )
    (comp (ref "R94")
      (value "51.1k")
      (footprint "eagle-import:R0805")
      (libsource (lib "eagle-import") (part "R-US_R0805"))
    )
    (comp (ref "R95")
      (value "5.1k")
      (footprint "eagle-import:R0805")
      (libsource (lib "eagle-import") (part "R-US_R0805"))
    )
    (comp (ref "R96")
      (value "22k")
      (footprint "eagle-import:R0805")
      (libsource (lib "eagle-import") (part "R-US_R0805"))
    )
    (comp (ref "R97")
      (value "51.1k")
      (footprint "eagle-import:R0805")
      (libsource (lib "eagle-import") (part "R-US_R0805"))
    )
    (comp (ref "R98")
      (value "5.1k")
      (footprint "eagle-import:R0805")
      (libsource (lib "eagle-import") (part "R-US_R0805"))
    )
    (comp (ref "R99")
      (value "68.1k")
      (footprint "eagle-import:R0805")
      (libsource (lib "eagle-import") (part "R-US_R0805"))
    )
    (comp (ref "R100")
      (value "68.1k")
      (footprint "eagle-import:R0805")
      (libsource (lib "eagle-import") (part "R-US_R0805"))
    )
    (comp (ref "R101")
      (value "10k")
      (footprint "eagle-import:R0805")
      (libsource (lib "eagle-import") (part "R-US_R0805"))
    )
    (comp (ref "R102")
      (value "10k")
      (footprint "eagle-import:R0805")
      (libsource (lib "eagle-import") (part "R-US_R0805"))
    )
    (comp (ref "R103")
      (value "10k")
      (footprint "eagle-import:R0805")
      (libsource (lib "eagle-import") (part "R-US_R0805"))
    )
    (comp (ref "R104")
      (value "0.2")
      (footprint "eagle-import:R4527")
      (libsource (lib "eagle-import") (part "R-US_R4527"))
    )
    (comp (ref "R105")
      (value "2k")
      (footprint "eagle-import:M0805")
      (libsource (lib "eagle-import") (part "R-US_M0805"))
    )
    (comp (ref "R106")
      (value "2k")
      (footprint "eagle-import:R0805")
      (libsource (lib "eagle-import") (part "R-US_R0805"))
    )
    (comp (ref "R107")
      (value "10k")
      (footprint "eagle-import:R0805")
      (libsource (lib "eagle-import") (part "R-US_R0805"))
    )
    (comp (ref "R108")
      (value "2k")
      (footprint "eagle-import:R0805")
      (libsource (lib "eagle-import") (part "R-US_R0805"))
    )
    (comp (ref "R109")
      (value "2k")
      (footprint "eagle-import:R0805")
      (libsource (lib "eagle-import") (part "R-US_R0805"))
    )
    (comp (ref "R110")
      (value "0.2")
      (footprint "eagle-import:R4527")
      (libsource (lib "eagle-import") (part "R-US_R4527"))
    )
    (comp (ref "R111")
      (value "10k")
      (footprint "eagle-import:R0805")
      (libsource (lib "eagle-import") (part "R-US_R0805"))
    )
    (comp (ref "R112")
      (value "10k")
      (footprint "eagle-import:R0805")
      (libsource (lib "eagle-import") (part "R-US_R0805"))
    )
    (comp (ref "R113")
      (value "51.1k")
      (footprint "eagle-import:R0805")
      (libsource (lib "eagle-import") (part "R-US_R0805"))
    )
    (comp (ref "R114")
      (value "5.1k")
      (footprint "eagle-import:R0805")
      (libsource (lib "eagle-import") (part "R-US_R0805"))
    )
    (comp (ref "R115")
      (value "22k")
      (footprint "eagle-import:R0805")
      (libsource (lib "eagle-import") (part "R-US_R0805"))
    )
    (comp (ref "R116")
      (value "51.1k")
      (footprint "eagle-import:R0805")
      (libsource (lib "eagle-import") (part "R-US_R0805"))
    )
    (comp (ref "R117")
      (value "5.1k")
      (footprint "eagle-import:R0805")
      (libsource (lib "eagle-import") (part "R-US_R0805"))
    )
    (comp (ref "R118")
      (value "68.1k")
      (footprint "eagle-import:R0805")
      (libsource (lib "eagle-import") (part "R-US_R0805"))
    )
    (comp (ref "R119")
      (value "68.1k")
      (footprint "eagle-import:R0805")
      (libsource (lib "eagle-import") (part "R-US_R0805"))
    )
    (comp (ref "R120")
      (value "10k")
      (footprint "eagle-import:R0805")
      (libsource (lib "eagle-import") (part "R-US_R0805"))
    )
    (comp (ref "R121")
      (value "10k")
      (footprint "eagle-import:R0805")
      (libsource (lib "eagle-import") (part "R-US_R0805"))
    )
    (comp (ref "R122")
      (value "10k")
      (footprint "eagle-import:R0805")
      (libsource (lib "eagle-import") (part "R-US_R0805"))
    )
    (comp (ref "R123")
      (value "0.2")
      (footprint "eagle-import:R4527")
      (libsource (lib "eagle-import") (part "R-US_R4527"))
    )
    (comp (ref "R124")
      (value "2k")
      (footprint "eagle-import:M0805")
      (libsource (lib "eagle-import") (part "R-US_M0805"))
    )
    (comp (ref "R125")
      (value "2k")
      (footprint "eagle-import:R0805")
      (libsource (lib "eagle-import") (part "R-US_R0805"))
    )
    (comp (ref "R126")
      (value "10k")
      (footprint "eagle-import:R0805")
      (libsource (lib "eagle-import") (part "R-US_R0805"))
    )
    (comp (ref "R127")
      (value "2k")
      (footprint "eagle-import:R0805")
      (libsource (lib "eagle-import") (part "R-US_R0805"))
    )
    (comp (ref "R128")
      (value "2k")
      (footprint "eagle-import:R0805")
      (libsource (lib "eagle-import") (part "R-US_R0805"))
    )
    (comp (ref "R129")
      (value "0.2")
      (footprint "eagle-import:R4527")
      (libsource (lib "eagle-import") (part "R-US_R4527"))
    )
    (comp (ref "R130")
      (value "10k")
      (footprint "eagle-import:R0805")
      (libsource (lib "eagle-import") (part "R-US_R0805"))
    )
    (comp (ref "R131")
      (value "10k")
      (footprint "eagle-import:R0805")
      (libsource (lib "eagle-import") (part "R-US_R0805"))
    )
    (comp (ref "R132")
      (value "51.1k")
      (footprint "eagle-import:R0805")
      (libsource (lib "eagle-import") (part "R-US_R0805"))
    )
    (comp (ref "R133")
      (value "5.1k")
      (footprint "eagle-import:R0805")
      (libsource (lib "eagle-import") (part "R-US_R0805"))
    )
    (comp (ref "R134")
      (value "22k")
      (footprint "eagle-import:R0805")
      (libsource (lib "eagle-import") (part "R-US_R0805"))
    )
    (comp (ref "R135")
      (value "51.1k")
      (footprint "eagle-import:R0805")
      (libsource (lib "eagle-import") (part "R-US_R0805"))
    )
    (comp (ref "R136")
      (value "5.1k")
      (footprint "eagle-import:R0805")
      (libsource (lib "eagle-import") (part "R-US_R0805"))
    )
    (comp (ref "R147")
      (value "0.2")
      (footprint "eagle-import:R4527")
      (libsource (lib "eagle-import") (part "R-US_R4527"))
    )
    (comp (ref "R148")
      (value "68.1k")
      (footprint "eagle-import:R0805")
      (libsource (lib "eagle-import") (part "R-US_R0805"))
    )
    (comp (ref "R149")
      (value "68.1k")
      (footprint "eagle-import:R0805")
      (libsource (lib "eagle-import") (part "R-US_R0805"))
    )
    (comp (ref "R150")
      (value "10k")
      (footprint "eagle-import:R0805")
      (libsource (lib "eagle-import") (part "R-US_R0805"))
    )
    (comp (ref "R151")
      (value "10k")
      (footprint "eagle-import:R0805")
      (libsource (lib "eagle-import") (part "R-US_R0805"))
    )
    (comp (ref "R152")
      (value "10k")
      (footprint "eagle-import:R0805")
      (libsource (lib "eagle-import") (part "R-US_R0805"))
    )
    (comp (ref "R153")
      (value "0.2")
      (footprint "eagle-import:R4527")
      (libsource (lib "eagle-import") (part "R-US_R4527"))
    )
    (comp (ref "R154")
      (value "2k")
      (footprint "eagle-import:M0805")
      (libsource (lib "eagle-import") (part "R-US_M0805"))
    )
    (comp (ref "R164")
      (value "10k")
      (footprint "eagle-import:R0805")
      (libsource (lib "eagle-import") (part "R-US_R0805"))
    )
    (comp (ref "R165")
      (value "2k")
      (footprint "eagle-import:R0805")
      (libsource (lib "eagle-import") (part "R-US_R0805"))
    )
    (comp (ref "R166")
      (value "10k")
      (footprint "eagle-import:R0805")
      (libsource (lib "eagle-import") (part "R-US_R0805"))
    )
    (comp (ref "R167")
      (value "2k")
      (footprint "eagle-import:R0805")
      (libsource (lib "eagle-import") (part "R-US_R0805"))
    )
    (comp (ref "R168")
      (value "2k")
      (footprint "eagle-import:R0805")
      (libsource (lib "eagle-import") (part "R-US_R0805"))
    )
    (comp (ref "R169")
      (value "0.2")
      (footprint "eagle-import:R4527")
      (libsource (lib "eagle-import") (part "R-US_R4527"))
    )
    (comp (ref "R170")
      (value "10k")
      (footprint "eagle-import:R0805")
      (libsource (lib "eagle-import") (part "R-US_R0805"))
    )
    (comp (ref "R171")
      (value "10k")
      (footprint "eagle-import:R0805")
      (libsource (lib "eagle-import") (part "R-US_R0805"))
    )
    (comp (ref "R185")
      (value "2Meg")
      (footprint "eagle-import:R0805")
      (libsource (lib "eagle-import") (part "R-US_R0805"))
    )
    (comp (ref "R186")
      (value "2Meg")
      (footprint "eagle-import:R0805")
      (libsource (lib "eagle-import") (part "R-US_R0805"))
    )
    (comp (ref "R187")
      (value "2Meg")
      (footprint "eagle-import:R0805")
      (libsource (lib "eagle-import") (part "R-US_R0805"))
    )
    (comp (ref "R188")
      (value "2Meg")
      (footprint "eagle-import:R0805")
      (libsource (lib "eagle-import") (part "R-US_R0805"))
    )
    (comp (ref "R189")
      (value "2Meg")
      (footprint "eagle-import:R0805")
      (libsource (lib "eagle-import") (part "R-US_R0805"))
    )
    (comp (ref "R190")
      (value "2Meg")
      (footprint "eagle-import:R0805")
      (libsource (lib "eagle-import") (part "R-US_R0805"))
    )
    (comp (ref "R191")
      (value "2Meg")
      (footprint "eagle-import:R0805")
      (libsource (lib "eagle-import") (part "R-US_R0805"))
    )
    (comp (ref "R192")
      (value "2Meg")
      (footprint "eagle-import:R0805")
      (libsource (lib "eagle-import") (part "R-US_R0805"))
    )
    (comp (ref "U$1")
      (value "OPA549_HS677NOHS")
      (footprint "eagle-import:OPA549")
      (libsource (lib "eagle-import") (part "OPA549_HS677NOHS"))
    )
    (comp (ref "U$2")
      (value "OPA549_HS677NOHS")
      (footprint "eagle-import:OPA549")
      (libsource (lib "eagle-import") (part "OPA549_HS677NOHS"))
    )
    (comp (ref "U$3")
      (value "OPA549_HS677NOHS")
      (footprint "eagle-import:OPA549")
      (libsource (lib "eagle-import") (part "OPA549_HS677NOHS"))
    )
    (comp (ref "U$4")
      (value "OPA549_HS677NOHS")
      (footprint "eagle-import:OPA549")
      (libsource (lib "eagle-import") (part "OPA549_HS677NOHS"))
    )
    (comp (ref "U$5")
      (value "OPA549_HS677NOHS")
      (footprint "eagle-import:OPA549")
      (libsource (lib "eagle-import") (part "OPA549_HS677NOHS"))
    )
    (comp (ref "U$6")
      (value "OPA549_HS677NOHS")
      (footprint "eagle-import:OPA549")
      (libsource (lib "eagle-import") (part "OPA549_HS677NOHS"))
    )
    (comp (ref "U$7")
      (value "OPA549_HS677NOHS")
      (footprint "eagle-import:OPA549")
      (libsource (lib "eagle-import") (part "OPA549_HS677NOHS"))
    )
    (comp (ref "U$8")
      (value "OPA549_HS677NOHS")
      (footprint "eagle-import:OPA549")
      (libsource (lib "eagle-import") (part "OPA549_HS677NOHS"))
    )
    (comp (ref "U$9")
      (value "OPA549_HS677NOHS")
      (footprint "eagle-import:OPA549")
      (libsource (lib "eagle-import") (part "OPA549_HS677NOHS"))
    )
    (comp (ref "U$10")
      (value "OPA549_HS677NOHS")
      (footprint "eagle-import:OPA549")
      (libsource (lib "eagle-import") (part "OPA549_HS677NOHS"))
    )
    (comp (ref "U$11")
      (value "OPA549_HS677NOHS")
      (footprint "eagle-import:OPA549")
      (libsource (lib "eagle-import") (part "OPA549_HS677NOHS"))
    )
    (comp (ref "U$12")
      (value "OPA549_HS677NOHS")
      (footprint "eagle-import:OPA549")
      (libsource (lib "eagle-import") (part "OPA549_HS677NOHS"))
    )
    (comp (ref "U$13")
      (value "OPA549_HS677NOHS")
      (footprint "eagle-import:OPA549")
      (libsource (lib "eagle-import") (part "OPA549_HS677NOHS"))
    )
    (comp (ref "U$14")
      (value "OPA549_HS677NOHS")
      (footprint "eagle-import:OPA549")
      (libsource (lib "eagle-import") (part "OPA549_HS677NOHS"))
    )
    (comp (ref "U$15")
      (value "OPA549_HS677NOHS")
      (footprint "eagle-import:OPA549")
      (libsource (lib "eagle-import") (part "OPA549_HS677NOHS"))
    )
    (comp (ref "U$16")
      (value "OPA549_HS677NOHS")
      (footprint "eagle-import:OPA549")
      (libsource (lib "eagle-import") (part "OPA549_HS677NOHS"))
    )
    (comp (ref "U2")
      (value "INA170EA/250")
      (footprint "eagle-import:SOP65P490X110-8N")
      (libsource (lib "eagle-import") (part "INA170EA/250"))
    )
    (comp (ref "U3")
      (value "INA170EA/250")
      (footprint "eagle-import:SOP65P490X110-8N")
      (libsource (lib "eagle-import") (part "INA170EA/250"))
    )
    (comp (ref "U4")
      (value "OPA2340EA/250")
      (footprint "eagle-import:SOP65P490X110-8N")
      (libsource (lib "eagle-import") (part "OPA2340EA/250"))
    )
    (comp (ref "U5")
      (value "OPA2340EA/250")
      (footprint "eagle-import:SOP65P490X110-8N")
      (libsource (lib "eagle-import") (part "OPA2340EA/250"))
    )
    (comp (ref "U6")
      (value "INA170EA/250")
      (footprint "eagle-import:SOP65P490X110-8N")
      (libsource (lib "eagle-import") (part "INA170EA/250"))
    )
    (comp (ref "U7")
      (value "OPA2340EA/250")
      (footprint "eagle-import:SOP65P490X110-8N")
      (libsource (lib "eagle-import") (part "OPA2340EA/250"))
    )
    (comp (ref "U8")
      (value "INA170EA/250")
      (footprint "eagle-import:SOP65P490X110-8N")
      (libsource (lib "eagle-import") (part "INA170EA/250"))
    )
    (comp (ref "U12")
      (value "OPA2340EA/250")
      (footprint "eagle-import:SOP65P490X110-8N")
      (libsource (lib "eagle-import") (part "OPA2340EA/250"))
    )
    (comp (ref "U13")
      (value "INA170EA/250")
      (footprint "eagle-import:SOP65P490X110-8N")
      (libsource (lib "eagle-import") (part "INA170EA/250"))
    )
    (comp (ref "U14")
      (value "OPA2340EA/250")
      (footprint "eagle-import:SOP65P490X110-8N")
      (libsource (lib "eagle-import") (part "OPA2340EA/250"))
    )
    (comp (ref "U15")
      (value "INA170EA/250")
      (footprint "eagle-import:SOP65P490X110-8N")
      (libsource (lib "eagle-import") (part "INA170EA/250"))
    )
    (comp (ref "U16")
      (value "OPA2340EA/250")
      (footprint "eagle-import:SOP65P490X110-8N")
      (libsource (lib "eagle-import") (part "OPA2340EA/250"))
    )
    (comp (ref "U17")
      (value "INA170EA/250")
      (footprint "eagle-import:SOP65P490X110-8N")
      (libsource (lib "eagle-import") (part "INA170EA/250"))
    )
    (comp (ref "U18")
      (value "OPA2340EA/250")
      (footprint "eagle-import:SOP65P490X110-8N")
      (libsource (lib "eagle-import") (part "OPA2340EA/250"))
    )
    (comp (ref "U19")
      (value "INA170EA/250")
      (footprint "eagle-import:SOP65P490X110-8N")
      (libsource (lib "eagle-import") (part "INA170EA/250"))
    )
    (comp (ref "U20")
      (value "OPA2340EA/250")
      (footprint "eagle-import:SOP65P490X110-8N")
      (libsource (lib "eagle-import") (part "OPA2340EA/250"))
    )
    (comp (ref "U031")
      (value "0881070")
      (footprint "eagle-import:881")
      (libsource (lib "eagle-import") (part "0881070"))
    )
    (comp (ref "C85")
      (value "0.1uF")
      (footprint "eagle-import:C0603")
      (libsource (lib "eagle-import") (part "C-USC0603"))
    )
    (comp (ref "C86")
      (value "0.1uF")
      (footprint "eagle-import:C0603")
      (libsource (lib "eagle-import") (part "C-USC0603"))
    )
    (comp (ref "C87")
      (value "0.1uF")
      (footprint "eagle-import:C0603")
      (libsource (lib "eagle-import") (part "C-USC0603"))
    )
    (comp (ref "C88")
      (value "0.1uF")
      (footprint "eagle-import:C0603")
      (libsource (lib "eagle-import") (part "C-USC0603"))
    )
    (comp (ref "C89")
      (value "0.1uF")
      (footprint "eagle-import:C0603")
      (libsource (lib "eagle-import") (part "C-USC0603"))
    )
    (comp (ref "C90")
      (value "0.1uF")
      (footprint "eagle-import:C0603")
      (libsource (lib "eagle-import") (part "C-USC0603"))
    )
    (comp (ref "C91")
      (value "0.1uF")
      (footprint "eagle-import:C0603")
      (libsource (lib "eagle-import") (part "C-USC0603"))
    )
    (comp (ref "C92")
      (value "0.1uF")
      (footprint "eagle-import:C0603")
      (libsource (lib "eagle-import") (part "C-USC0603"))
    )
    (comp (ref "C93")
      (value "0.1uF")
      (footprint "eagle-import:C0603")
      (libsource (lib "eagle-import") (part "C-USC0603"))
    )
    (comp (ref "C94")
      (value "0.1uF")
      (footprint "eagle-import:C0603")
      (libsource (lib "eagle-import") (part "C-USC0603"))
    )
    (comp (ref "C95")
      (value "10uF")
      (footprint "eagle-import:C1206")
      (libsource (lib "eagle-import") (part "C-USC1206"))
    )
    (comp (ref "C96")
      (value "10uF")
      (footprint "eagle-import:C1206")
      (libsource (lib "eagle-import") (part "C-USC1206"))
    )
    (comp (ref "C97")
      (value "1uF")
      (footprint "eagle-import:C0603")
      (libsource (lib "eagle-import") (part "C-USC0603"))
    )
    (comp (ref "C98")
      (value "10uF")
      (footprint "eagle-import:C1206")
      (libsource (lib "eagle-import") (part "C-USC1206"))
    )
    (comp (ref "C99")
      (value "0.1uF")
      (footprint "eagle-import:C0603")
      (libsource (lib "eagle-import") (part "C-USC0603"))
    )
    (comp (ref "C100")
      (value "10uF")
      (footprint "eagle-import:C1206")
      (libsource (lib "eagle-import") (part "C-USC1206"))
    )
    (comp (ref "C101")
      (value "10uF")
      (footprint "eagle-import:C1206")
      (libsource (lib "eagle-import") (part "C-USC1206"))
    )
    (comp (ref "C102")
      (value "0.1uF")
      (footprint "eagle-import:C0603")
      (libsource (lib "eagle-import") (part "C-USC0603"))
    )
    (comp (ref "C103")
      (value "0.1uF")
      (footprint "eagle-import:C0603")
      (libsource (lib "eagle-import") (part "C-USC0603"))
    )
    (comp (ref "C104")
      (value "0.1uF")
      (footprint "eagle-import:C0603")
      (libsource (lib "eagle-import") (part "C-USC0603"))
    )
    (comp (ref "C105")
      (value "0.1uF")
      (footprint "eagle-import:C0603")
      (libsource (lib "eagle-import") (part "C-USC0603"))
    )
    (comp (ref "C106")
      (value "0.1uF")
      (footprint "eagle-import:C0603")
      (libsource (lib "eagle-import") (part "C-USC0603"))
    )
    (comp (ref "C107")
      (value "0.1uF")
      (footprint "eagle-import:C0603")
      (libsource (lib "eagle-import") (part "C-USC0603"))
    )
    (comp (ref "C108")
      (value "0.1uF")
      (footprint "eagle-import:C0603")
      (libsource (lib "eagle-import") (part "C-USC0603"))
    )
    (comp (ref "C109")
      (value "0.1uF")
      (footprint "eagle-import:C0603")
      (libsource (lib "eagle-import") (part "C-USC0603"))
    )
    (comp (ref "C118")
      (value "0.1uF")
      (footprint "eagle-import:C0603")
      (libsource (lib "eagle-import") (part "C-USC0603"))
    )
    (comp (ref "C119")
      (value "0.1uF")
      (footprint "eagle-import:C0603")
      (libsource (lib "eagle-import") (part "C-USC0603"))
    )
    (comp (ref "C129")
      (value "0.1uF")
      (footprint "eagle-import:C0603")
      (libsource (lib "eagle-import") (part "C-USC0603"))
    )
    (comp (ref "C130")
      (value "0.1uF")
      (footprint "eagle-import:C0603")
      (libsource (lib "eagle-import") (part "C-USC0603"))
    )
    (comp (ref "C131")
      (value "0.1uF")
      (footprint "eagle-import:C0603")
      (libsource (lib "eagle-import") (part "C-USC0603"))
    )
    (comp (ref "IC1")
      (value "LINEAR_7805DT")
      (footprint "eagle-import:LINEAR_TO252")
      (libsource (lib "eagle-import") (part "LINEAR_78DT05"))
    )
    (comp (ref "IC2")
      (value "74LS279D")
      (footprint "eagle-import:SO16")
      (libsource (lib "eagle-import") (part "74279DLS"))
    )
    (comp (ref "IC3")
      (value "7400D")
      (footprint "eagle-import:SO14")
      (libsource (lib "eagle-import") (part "7400D"))
    )
    (comp (ref "IC4")
      (value "74LS138D")
      (footprint "eagle-import:SO16")
      (libsource (lib "eagle-import") (part "74138DLS"))
    )
    (comp (ref "IC5")
      (value "LMV321M5")
      (footprint "eagle-import:SOT23-5")
      (libsource (lib "eagle-import") (part "LMV321?M5"))
    )
    (comp (ref "IC6")
      (value "74LS240DW")
      (footprint "eagle-import:SO20W")
      (libsource (lib "eagle-import") (part "74240DWLS"))
    )
    (comp (ref "JP1")
      (value "PINHD-1X8")
      (footprint "eagle-import:1X08")
      (libsource (lib "eagle-import") (part "PINHD-1X8"))
    )
    (comp (ref "JP2")
      (value "PINHD-1X8")
      (footprint "eagle-import:1X08")
      (libsource (lib "eagle-import") (part "PINHD-1X8"))
    )
    (comp (ref "LED1")
      (value "LEDCHIPLED_0805")
      (footprint "eagle-import:CHIPLED_0805")
      (libsource (lib "eagle-import") (part "LEDCHIPLED_0805"))
    )
    (comp (ref "LED2")
      (value "LEDCHIPLED_0805")
      (footprint "eagle-import:CHIPLED_0805")
      (libsource (lib "eagle-import") (part "LEDCHIPLED_0805"))
    )
    (comp (ref "LED3")
      (value "LEDCHIPLED_0805")
      (footprint "eagle-import:CHIPLED_0805")
      (libsource (lib "eagle-import") (part "LEDCHIPLED_0805"))
    )
    (comp (ref "R000")
      (value "100")
      (footprint "eagle-import:R0805")
      (fields (field (name "SPICEPREFIX") "100"))
      (libsource (lib "eagle-import") (part "R-US_R0805"))
    )
    (comp (ref "R137")
      (value "100")
      (footprint "eagle-import:R0805")
      (fields (field (name "SPICEPREFIX") "100"))
      (libsource (lib "eagle-import") (part "R-US_R0805"))
    )
    (comp (ref "R138")
      (value "100")
      (footprint "eagle-import:R0805")
      (fields (field (name "SPICEPREFIX") "100"))
      (libsource (lib "eagle-import") (part "R-US_R0805"))
    )
    (comp (ref "R139")
      (value "100")
      (footprint "eagle-import:R0805")
      (fields (field (name "SPICEPREFIX") "100"))
      (libsource (lib "eagle-import") (part "R-US_R0805"))
    )
    (comp (ref "R140")
      (value "100")
      (footprint "eagle-import:R0805")
      (fields (field (name "SPICEPREFIX") "100"))
      (libsource (lib "eagle-import") (part "R-US_R0805"))
    )
    (comp (ref "R141")
      (value "2k")
      (footprint "eagle-import:R0805")
      (fields (field (name "SPICEPREFIX") "2k"))
      (libsource (lib "eagle-import") (part "R-US_R0805"))
    )
    (comp (ref "R142")
      (value "330")
      (footprint "eagle-import:R0805")
      (fields (field (name "SPICEPREFIX") "330"))
      (libsource (lib "eagle-import") (part "R-US_R0805"))
    )
    (comp (ref "R143")
      (value "330")
      (footprint "eagle-import:R0805")
      (fields (field (name "SPICEPREFIX") "330"))
      (libsource (lib "eagle-import") (part "R-US_R0805"))
    )
    (comp (ref "R144")
      (value "330")
      (footprint "eagle-import:R0805")
      (fields (field (name "SPICEPREFIX") "330"))
      (libsource (lib "eagle-import") (part "R-US_R0805"))
    )
    (comp (ref "R145")
      (value "2k")
      (footprint "eagle-import:R0805")
      (libsource (lib "eagle-import") (part "R-US_R0805"))
    )
    (comp (ref "R146")
      (value "2k")
      (footprint "eagle-import:R0805")
      (libsource (lib "eagle-import") (part "R-US_R0805"))
    )
    (comp (ref "R155")
      (value "0")
      (footprint "eagle-import:R0603")
      (libsource (lib "eagle-import") (part "R-US_R0603"))
    )
    (comp (ref "R156")
      (value "0")
      (footprint "eagle-import:R0603")
      (libsource (lib "eagle-import") (part "R-US_R0603"))
    )
    (comp (ref "R157")
      (value "0")
      (footprint "eagle-import:R0603")
      (libsource (lib "eagle-import") (part "R-US_R0603"))
    )
    (comp (ref "R158")
      (value "0")
      (footprint "eagle-import:R0603")
      (libsource (lib "eagle-import") (part "R-US_R0603"))
    )
    (comp (ref "R159")
      (value "0")
      (footprint "eagle-import:R0603")
      (libsource (lib "eagle-import") (part "R-US_R0603"))
    )
    (comp (ref "R160")
      (value "0")
      (footprint "eagle-import:R0603")
      (libsource (lib "eagle-import") (part "R-US_R0603"))
    )
    (comp (ref "R161")
      (value "0")
      (footprint "eagle-import:R0603")
      (libsource (lib "eagle-import") (part "R-US_R0603"))
    )
    (comp (ref "R162")
      (value "0")
      (footprint "eagle-import:R0603")
      (libsource (lib "eagle-import") (part "R-US_R0603"))
    )
    (comp (ref "R163")
      (value "10k")
      (footprint "eagle-import:R0603")
      (libsource (lib "eagle-import") (part "R-US_R0603"))
    )
    (comp (ref "R172")
      (value "100")
      (footprint "eagle-import:R0805")
      (fields (field (name "SPICEPREFIX") "100"))
      (libsource (lib "eagle-import") (part "R-US_R0805"))
    )
    (comp (ref "R173")
      (value "330")
      (footprint "eagle-import:R0805")
      (fields (field (name "SPICEPREFIX") "330"))
      (libsource (lib "eagle-import") (part "R-US_R0805"))
    )
    (comp (ref "R174")
      (value "330")
      (footprint "eagle-import:R0805")
      (fields (field (name "SPICEPREFIX") "330"))
      (libsource (lib "eagle-import") (part "R-US_R0805"))
    )
    (comp (ref "R175")
      (value "330")
      (footprint "eagle-import:R0805")
      (fields (field (name "SPICEPREFIX") "330"))
      (libsource (lib "eagle-import") (part "R-US_R0805"))
    )
    (comp (ref "R176")
      (value "330")
      (footprint "eagle-import:R0805")
      (fields (field (name "SPICEPREFIX") "330"))
      (libsource (lib "eagle-import") (part "R-US_R0805"))
    )
    (comp (ref "R177")
      (value "330")
      (footprint "eagle-import:R0805")
      (fields (field (name "SPICEPREFIX") "330"))
      (libsource (lib "eagle-import") (part "R-US_R0805"))
    )
    (comp (ref "R178")
      (value "330")
      (footprint "eagle-import:R0805")
      (fields (field (name "SPICEPREFIX") "330"))
      (libsource (lib "eagle-import") (part "R-US_R0805"))
    )
    (comp (ref "R179")
      (value "330")
      (footprint "eagle-import:R0805")
      (fields (field (name "SPICEPREFIX") "330"))
      (libsource (lib "eagle-import") (part "R-US_R0805"))
    )
    (comp (ref "R180")
      (value "330")
      (footprint "eagle-import:R0805")
      (fields (field (name "SPICEPREFIX") "330"))
      (libsource (lib "eagle-import") (part "R-US_R0805"))
    )
    (comp (ref "R181")
      (value "330")
      (footprint "eagle-import:R0805")
      (fields (field (name "SPICEPREFIX") "330"))
      (libsource (lib "eagle-import") (part "R-US_R0805"))
    )
    (comp (ref "R182")
      (value "330")
      (footprint "eagle-import:R0805")
      (fields (field (name "SPICEPREFIX") "330"))
      (libsource (lib "eagle-import") (part "R-US_R0805"))
    )
    (comp (ref "R183")
      (value "330")
      (footprint "eagle-import:R0805")
      (fields (field (name "SPICEPREFIX") "330"))
      (libsource (lib "eagle-import") (part "R-US_R0805"))
    )
    (comp (ref "R184")
      (value "100")
      (footprint "eagle-import:R0805")
      (fields (field (name "SPICEPREFIX") "100"))
      (libsource (lib "eagle-import") (part "R-US_R0805"))
    )
    (comp (ref "U001")
      (value "65LVDS34")
      (footprint "eagle-import:SO08-1")
      (libsource (lib "eagle-import") (part "DS9637A"))
    )
    (comp (ref "U9")
      (value "LTC2656BCFE-H16PBF")
      (footprint "eagle-import:SOP65P640X120-21N")
      (fields (field (name "MPN") "LTC2656BCFE-H16#PBF"))
      (libsource (lib "eagle-import") (part "LTC2656BCFE-H16PBF"))
    )
    (comp (ref "U10")
      (value "LTC1863CGNPBF")
      (footprint "eagle-import:SOP63P600X175-16N")
      (fields (field (name "MPN") "LTC1863CGN#PBF"))
      (libsource (lib "eagle-import") (part "LTC1863CGNPBF"))
    )
    (comp (ref "U011")
      (value "65LVDS9638")
      (footprint "eagle-import:SO08-1")
      (libsource (lib "eagle-import") (part "DS9638"))
    )
    (comp (ref "U021")
      (value "65LVDS34")
      (footprint "eagle-import:SO08-1")
      (libsource (lib "eagle-import") (part "DS9637A"))
    )
    (comp (ref "U025")
      (value "ACSL-6400")
      (footprint "eagle-import:ACSL-SO16")
      (libsource (lib "eagle-import") (part "ACSL-6400"))
    )
    (comp (ref "U026")
      (value "ACSL-6420")
      (footprint "eagle-import:ACSL-SO16")
      (libsource (lib "eagle-import") (part "ACSL-6420"))
    )
    (comp (ref "U030")
      (value "65LVDS34")
      (footprint "eagle-import:SO08-1")
      (libsource (lib "eagle-import") (part "DS9637A"))
    )
    (comp (ref "U040")
      (value "1N4148")
      (footprint "eagle-import:1N4148")
      (libsource (lib "eagle-import") (part "1N4148"))
    )
    (comp (ref "U041")
      (value "1N4148")
      (footprint "eagle-import:1N4148")
      (libsource (lib "eagle-import") (part "1N4148"))
    )
    (comp (ref "U042")
      (value "1N4148")
      (footprint "eagle-import:1N4148")
      (libsource (lib "eagle-import") (part "1N4148"))
    )
    (comp (ref "U043")
      (value "1N4148")
      (footprint "eagle-import:1N4148")
      (libsource (lib "eagle-import") (part "1N4148"))
    )
    (comp (ref "U044")
      (value "1N4148")
      (footprint "eagle-import:1N4148")
      (libsource (lib "eagle-import") (part "1N4148"))
    )
    (comp (ref "U045")
      (value "1N4148")
      (footprint "eagle-import:1N4148")
      (libsource (lib "eagle-import") (part "1N4148"))
    )
    (comp (ref "U046")
      (value "1N4148")
      (footprint "eagle-import:1N4148")
      (libsource (lib "eagle-import") (part "1N4148"))
    )
    (comp (ref "X002")
      (value "RJ45V")
      (footprint "eagle-import:RJ45-VERTICAL")
      (libsource (lib "eagle-import") (part "RJ45V"))
    )
    (comp (ref "X003")
      (value "RJ45V")
      (footprint "eagle-import:RJ45-VERTICAL")
      (libsource (lib "eagle-import") (part "RJ45V"))
    )
  )
  (nets
    (net (code "1") (name "+5V") (class "Default")
      (node (ref "C10") (pin "1") (pinfunction "1_1") (pintype "passive"))
      (node (ref "C101") (pin "1") (pinfunction "1_1") (pintype "passive"))
      (node (ref "C102") (pin "1") (pinfunction "1_1") (pintype "passive"))
      (node (ref "C103") (pin "1") (pinfunction "1_1") (pintype "passive"))
      (node (ref "C104") (pin "1") (pinfunction "1_1") (pintype "passive"))
      (node (ref "C107") (pin "1") (pinfunction "1_1") (pintype "passive"))
      (node (ref "C116") (pin "1") (pinfunction "1_1") (pintype "passive"))
      (node (ref "C117") (pin "1") (pinfunction "1_1") (pintype "passive"))
      (node (ref "C118") (pin "1") (pinfunction "1_1") (pintype "passive"))
      (node (ref "C15") (pin "1") (pinfunction "1_1") (pintype "passive"))
      (node (ref "C25") (pin "1") (pinfunction "1_1") (pintype "passive"))
      (node (ref "C26") (pin "1") (pinfunction "1_1") (pintype "passive"))
      (node (ref "C36") (pin "1") (pinfunction "1_1") (pintype "passive"))
      (node (ref "C37") (pin "1") (pinfunction "1_1") (pintype "passive"))
      (node (ref "C47") (pin "1") (pinfunction "1_1") (pintype "passive"))
      (node (ref "C48") (pin "1") (pinfunction "1_1") (pintype "passive"))
      (node (ref "C58") (pin "1") (pinfunction "1_1") (pintype "passive"))
      (node (ref "C59") (pin "1") (pinfunction "1_1") (pintype "passive"))
      (node (ref "C69") (pin "1") (pinfunction "1_1") (pintype "passive"))
      (node (ref "C70") (pin "1") (pinfunction "1_1") (pintype "passive"))
      (node (ref "C80") (pin "1") (pinfunction "1_1") (pintype "passive"))
      (node (ref "C81") (pin "1") (pinfunction "1_1") (pintype "passive"))
      (node (ref "C89") (pin "1") (pinfunction "1_1") (pintype "passive"))
      (node (ref "C90") (pin "1") (pinfunction "1_1") (pintype "passive"))
      (node (ref "C91") (pin "1") (pinfunction "1_1") (pintype "passive"))
      (node (ref "C92") (pin "1") (pinfunction "1_1") (pintype "passive"))
      (node (ref "C93") (pin "1") (pinfunction "1_1") (pintype "passive"))
      (node (ref "C94") (pin "1") (pinfunction "1_1") (pintype "passive"))
      (node (ref "C97") (pin "1") (pinfunction "1_1") (pintype "passive"))
      (node (ref "C98") (pin "1") (pinfunction "1_1") (pintype "passive"))
      (node (ref "C99") (pin "1") (pinfunction "1_1") (pintype "passive"))
      (node (ref "IC1") (pin "2") (pinfunction "VO_2") (pintype "passive"))
      (node (ref "IC2") (pin "16") (pinfunction "VCC_16") (pintype "power_in"))
      (node (ref "IC3") (pin "14") (pinfunction "VCC_14") (pintype "power_in"))
      (node (ref "IC4") (pin "16") (pinfunction "VCC_16") (pintype "power_in"))
      (node (ref "IC4") (pin "6") (pinfunction "G1_6") (pintype "input"))
      (node (ref "IC5") (pin "5") (pinfunction "V+_5") (pintype "power_in"))
      (node (ref "IC6") (pin "20") (pinfunction "VCC_20") (pintype "power_in"))
      (node (ref "LED2") (pin "A") (pinfunction "A_A") (pintype "passive"))
      (node (ref "R141") (pin "2") (pinfunction "2_2") (pintype "passive"))
      (node (ref "R142") (pin "2") (pinfunction "2_2") (pintype "passive"))
      (node (ref "R143") (pin "2") (pinfunction "2_2") (pintype "passive"))
      (node (ref "R144") (pin "2") (pinfunction "2_2") (pintype "passive"))
      (node (ref "R163") (pin "1") (pinfunction "1_1") (pintype "passive"))
      (node (ref "R175") (pin "2") (pinfunction "2_2") (pintype "passive"))
      (node (ref "R176") (pin "2") (pinfunction "2_2") (pintype "passive"))
      (node (ref "U025") (pin "10") (pinfunction "VDD1_10") (pintype "bidirectional"))
      (node (ref "U025") (pin "15") (pinfunction "VDD2_15") (pintype "bidirectional"))
      (node (ref "U026") (pin "12") (pinfunction "VDD2_12") (pintype "bidirectional"))
      (node (ref "U10") (pin "16") (pinfunction "VDD_16") (pintype "power_in"))
      (node (ref "U12") (pin "8") (pinfunction "V+_8") (pintype "power_in"))
      (node (ref "U13") (pin "8") (pinfunction "V+_8") (pintype "power_in"))
      (node (ref "U14") (pin "8") (pinfunction "V+_8") (pintype "power_in"))
      (node (ref "U15") (pin "8") (pinfunction "V+_8") (pintype "power_in"))
      (node (ref "U16") (pin "8") (pinfunction "V+_8") (pintype "power_in"))
      (node (ref "U17") (pin "8") (pinfunction "V+_8") (pintype "power_in"))
      (node (ref "U18") (pin "8") (pinfunction "V+_8") (pintype "power_in"))
      (node (ref "U19") (pin "8") (pinfunction "V+_8") (pintype "power_in"))
      (node (ref "U2") (pin "8") (pinfunction "V+_8") (pintype "power_in"))
      (node (ref "U20") (pin "8") (pinfunction "V+_8") (pintype "power_in"))
      (node (ref "U3") (pin "8") (pinfunction "V+_8") (pintype "power_in"))
      (node (ref "U4") (pin "8") (pinfunction "V+_8") (pintype "power_in"))
      (node (ref "U5") (pin "8") (pinfunction "V+_8") (pintype "power_in"))
      (node (ref "U6") (pin "8") (pinfunction "V+_8") (pintype "power_in"))
      (node (ref "U7") (pin "8") (pinfunction "V+_8") (pintype "power_in"))
      (node (ref "U8") (pin "8") (pinfunction "V+_8") (pintype "power_in"))
      (node (ref "U9") (pin "14") (pinfunction "PORSEL_14") (pintype "input"))
      (node (ref "U9") (pin "19") (pinfunction "VCC_19") (pintype "power_in"))
      (node (ref "U9") (pin "8") (pinfunction "~{LDAC}_8") (pintype "input"))
    )
    (net (code "2") (name "+5V{slash}1") (class "Default")
      (node (ref "C105") (pin "1") (pinfunction "1_1") (pintype "passive"))
      (node (ref "C106") (pin "1") (pinfunction "1_1") (pintype "passive"))
      (node (ref "C108") (pin "1") (pinfunction "1_1") (pintype "passive"))
      (node (ref "C109") (pin "1") (pinfunction "1_1") (pintype "passive"))
      (node (ref "C119") (pin "1") (pinfunction "1_1") (pintype "passive"))
      (node (ref "C129") (pin "1") (pinfunction "1_1") (pintype "passive"))
      (node (ref "C130") (pin "1") (pinfunction "1_1") (pintype "passive"))
      (node (ref "C131") (pin "1") (pinfunction "1_1") (pintype "passive"))
      (node (ref "R139") (pin "2") (pinfunction "2_2") (pintype "passive"))
      (node (ref "R173") (pin "2") (pinfunction "2_2") (pintype "passive"))
      (node (ref "R174") (pin "2") (pinfunction "2_2") (pintype "passive"))
      (node (ref "U001") (pin "1") (pinfunction "VCC_1") (pintype "bidirectional"))
      (node (ref "U011") (pin "1") (pinfunction "VCC_1") (pintype "bidirectional"))
      (node (ref "U021") (pin "1") (pinfunction "VCC_1") (pintype "bidirectional"))
      (node (ref "U025") (pin "1") (pinfunction "AN1_1") (pintype "bidirectional"))
      (node (ref "U025") (pin "3") (pinfunction "AN2_3") (pintype "bidirectional"))
      (node (ref "U025") (pin "5") (pinfunction "AN3_5") (pintype "bidirectional"))
      (node (ref "U026") (pin "4") (pinfunction "VDD1_4") (pintype "bidirectional"))
      (node (ref "U026") (pin "5") (pinfunction "AN1_5") (pintype "bidirectional"))
      (node (ref "U026") (pin "7") (pinfunction "AN2_7") (pintype "bidirectional"))
      (node (ref "U030") (pin "1") (pinfunction "VCC_1") (pintype "bidirectional"))
      (node (ref "X003") (pin "7") (pinfunction "7_7") (pintype "passive"))
    )
    (net (code "3") (name "ADC_SEL") (class "Default")
      (node (ref "IC4") (pin "14") (pinfunction "Y1_14") (pintype "output"))
      (node (ref "U10") (pin "11") (pinfunction "~{CS/CONV}_11") (pintype "input"))
    )
    (net (code "4") (name "BOARD") (class "Default")
      (node (ref "IC4") (pin "4") (pinfunction "G2A_4") (pintype "input"))
      (node (ref "R142") (pin "1") (pinfunction "1_1") (pintype "passive"))
      (node (ref "U025") (pin "13") (pinfunction "OUT2_13") (pintype "bidirectional"))
    )
    (net (code "5") (name "BOARD_I") (class "Default")
      (node (ref "R177") (pin "1") (pinfunction "1_1") (pintype "passive"))
      (node (ref "U030") (pin "2") (pinfunction "OUTA_2") (pintype "bidirectional"))
      (node (ref "U040") (pin "2") (pinfunction "C_2") (pintype "passive"))
    )
    (net (code "6") (name "BOARD_II") (class "Default")
      (node (ref "R177") (pin "2") (pinfunction "2_2") (pintype "passive"))
      (node (ref "U025") (pin "4") (pinfunction "CATH2_4") (pintype "bidirectional"))
      (node (ref "U040") (pin "1") (pinfunction "A_1") (pintype "passive"))
    )
    (net (code "7") (name "BOARD_Y") (class "Default")
      (node (ref "R137") (pin "2") (pinfunction "2_2") (pintype "passive"))
      (node (ref "U030") (pin "8") (pinfunction "INA1_8") (pintype "bidirectional"))
      (node (ref "X003") (pin "1") (pinfunction "1_1") (pintype "passive"))
    )
    (net (code "8") (name "BOARD_Z") (class "Default")
      (node (ref "R137") (pin "1") (pinfunction "1_1") (pintype "passive"))
      (node (ref "U030") (pin "7") (pinfunction "INA2_7") (pintype "bidirectional"))
      (node (ref "X003") (pin "2") (pinfunction "2_2") (pintype "passive"))
    )
    (net (code "9") (name "DAC_OUT_A") (class "Default")
      (node (ref "JP2") (pin "1") (pinfunction "1_1") (pintype "passive"))
      (node (ref "R155") (pin "2") (pinfunction "2_2") (pintype "passive"))
      (node (ref "R8") (pin "1") (pinfunction "1_1") (pintype "passive"))
    )
    (net (code "10") (name "DAC_OUT_B") (class "Default")
      (node (ref "JP2") (pin "2") (pinfunction "2_2") (pintype "passive"))
      (node (ref "R156") (pin "2") (pinfunction "2_2") (pintype "passive"))
      (node (ref "R25") (pin "1") (pinfunction "1_1") (pintype "passive"))
    )
    (net (code "11") (name "DAC_OUT_C") (class "Default")
      (node (ref "JP2") (pin "3") (pinfunction "3_3") (pintype "passive"))
      (node (ref "R157") (pin "2") (pinfunction "2_2") (pintype "passive"))
      (node (ref "R44") (pin "1") (pinfunction "1_1") (pintype "passive"))
    )
    (net (code "12") (name "DAC_OUT_D") (class "Default")
      (node (ref "JP2") (pin "4") (pinfunction "4_4") (pintype "passive"))
      (node (ref "R158") (pin "2") (pinfunction "2_2") (pintype "passive"))
      (node (ref "R63") (pin "1") (pinfunction "1_1") (pintype "passive"))
    )
    (net (code "13") (name "DAC_OUT_E") (class "Default")
      (node (ref "JP2") (pin "5") (pinfunction "5_5") (pintype "passive"))
      (node (ref "R159") (pin "2") (pinfunction "2_2") (pintype "passive"))
      (node (ref "R82") (pin "1") (pinfunction "1_1") (pintype "passive"))
    )
    (net (code "14") (name "DAC_OUT_F") (class "Default")
      (node (ref "JP2") (pin "6") (pinfunction "6_6") (pintype "passive"))
      (node (ref "R101") (pin "1") (pinfunction "1_1") (pintype "passive"))
      (node (ref "R160") (pin "2") (pinfunction "2_2") (pintype "passive"))
    )
    (net (code "15") (name "DAC_OUT_G") (class "Default")
      (node (ref "JP2") (pin "7") (pinfunction "7_7") (pintype "passive"))
      (node (ref "R120") (pin "1") (pinfunction "1_1") (pintype "passive"))
      (node (ref "R161") (pin "2") (pinfunction "2_2") (pintype "passive"))
    )
    (net (code "16") (name "DAC_OUT_H") (class "Default")
      (node (ref "JP2") (pin "8") (pinfunction "8_8") (pintype "passive"))
      (node (ref "R150") (pin "1") (pinfunction "1_1") (pintype "passive"))
      (node (ref "R162") (pin "2") (pinfunction "2_2") (pintype "passive"))
    )
    (net (code "17") (name "DAC_REF") (class "Default")
      (node (ref "IC5") (pin "3") (pinfunction "-IN_3") (pintype "input"))
      (node (ref "IC5") (pin "4") (pinfunction "OUT_4") (pintype "output"))
      (node (ref "U12") (pin "5") (pinfunction "+IN_B_5") (pintype "input"))
      (node (ref "U14") (pin "5") (pinfunction "+IN_B_5") (pintype "input"))
      (node (ref "U16") (pin "5") (pinfunction "+IN_B_5") (pintype "input"))
      (node (ref "U18") (pin "5") (pinfunction "+IN_B_5") (pintype "input"))
      (node (ref "U20") (pin "5") (pinfunction "+IN_B_5") (pintype "input"))
      (node (ref "U4") (pin "5") (pinfunction "+IN_B_5") (pintype "input"))
      (node (ref "U5") (pin "5") (pinfunction "+IN_B_5") (pintype "input"))
      (node (ref "U7") (pin "5") (pinfunction "+IN_B_5") (pintype "input"))
    )
    (net (code "18") (name "DAC_REF_0") (class "Default")
      (node (ref "R9") (pin "1") (pinfunction "1_1") (pintype "passive"))
      (node (ref "U2") (pin "3") (pinfunction "VREF_3") (pintype "input"))
      (node (ref "U4") (pin "6") (pinfunction "-IN_B_6") (pintype "input"))
      (node (ref "U4") (pin "7") (pinfunction "OUT_B_7") (pintype "output"))
    )
    (net (code "19") (name "DAC_REF_1") (class "Default")
      (node (ref "R26") (pin "1") (pinfunction "1_1") (pintype "passive"))
      (node (ref "U3") (pin "3") (pinfunction "VREF_3") (pintype "input"))
      (node (ref "U5") (pin "6") (pinfunction "-IN_B_6") (pintype "input"))
      (node (ref "U5") (pin "7") (pinfunction "OUT_B_7") (pintype "output"))
    )
    (net (code "20") (name "DAC_REF_2") (class "Default")
      (node (ref "R45") (pin "1") (pinfunction "1_1") (pintype "passive"))
      (node (ref "U6") (pin "3") (pinfunction "VREF_3") (pintype "input"))
      (node (ref "U7") (pin "6") (pinfunction "-IN_B_6") (pintype "input"))
      (node (ref "U7") (pin "7") (pinfunction "OUT_B_7") (pintype "output"))
    )
    (net (code "21") (name "DAC_REF_3") (class "Default")
      (node (ref "R64") (pin "1") (pinfunction "1_1") (pintype "passive"))
      (node (ref "U12") (pin "6") (pinfunction "-IN_B_6") (pintype "input"))
      (node (ref "U12") (pin "7") (pinfunction "OUT_B_7") (pintype "output"))
      (node (ref "U8") (pin "3") (pinfunction "VREF_3") (pintype "input"))
    )
    (net (code "22") (name "DAC_REF_4") (class "Default")
      (node (ref "R83") (pin "1") (pinfunction "1_1") (pintype "passive"))
      (node (ref "U13") (pin "3") (pinfunction "VREF_3") (pintype "input"))
      (node (ref "U14") (pin "6") (pinfunction "-IN_B_6") (pintype "input"))
      (node (ref "U14") (pin "7") (pinfunction "OUT_B_7") (pintype "output"))
    )
    (net (code "23") (name "DAC_REF_5") (class "Default")
      (node (ref "R102") (pin "1") (pinfunction "1_1") (pintype "passive"))
      (node (ref "U15") (pin "3") (pinfunction "VREF_3") (pintype "input"))
      (node (ref "U16") (pin "6") (pinfunction "-IN_B_6") (pintype "input"))
      (node (ref "U16") (pin "7") (pinfunction "OUT_B_7") (pintype "output"))
    )
    (net (code "24") (name "DAC_REF_6") (class "Default")
      (node (ref "R121") (pin "1") (pinfunction "1_1") (pintype "passive"))
      (node (ref "U17") (pin "3") (pinfunction "VREF_3") (pintype "input"))
      (node (ref "U18") (pin "6") (pinfunction "-IN_B_6") (pintype "input"))
      (node (ref "U18") (pin "7") (pinfunction "OUT_B_7") (pintype "output"))
    )
    (net (code "25") (name "DAC_REF_7") (class "Default")
      (node (ref "R151") (pin "1") (pinfunction "1_1") (pintype "passive"))
      (node (ref "U19") (pin "3") (pinfunction "VREF_3") (pintype "input"))
      (node (ref "U20") (pin "6") (pinfunction "-IN_B_6") (pintype "input"))
      (node (ref "U20") (pin "7") (pinfunction "OUT_B_7") (pintype "output"))
    )
    (net (code "26") (name "DAC_REF_OUT") (class "Default")
      (node (ref "C85") (pin "1") (pinfunction "1_1") (pintype "passive"))
      (node (ref "IC5") (pin "1") (pinfunction "+IN_1") (pintype "input"))
      (node (ref "U9") (pin "7") (pinfunction "REFIN/OUT_7") (pintype "bidirectional"))
    )
    (net (code "27") (name "DAC_SEL") (class "Default")
      (node (ref "IC4") (pin "15") (pinfunction "Y0_15") (pintype "output"))
      (node (ref "U9") (pin "9") (pinfunction "~{CS/LD}_9") (pintype "input"))
    )
    (net (code "28") (name "FAULT") (class "Default")
      (node (ref "IC2") (pin "6") (pinfunction "S_6") (pintype "input"))
      (node (ref "IC3") (pin "3") (pinfunction "O_3") (pintype "output"))
    )
    (net (code "29") (name "FAULT_BUFFER") (class "Default")
      (node (ref "IC3") (pin "1") (pinfunction "I0_1") (pintype "input"))
      (node (ref "IC6") (pin "14") (pinfunction "Y3_14") (pintype "tri_state"))
    )
    (net (code "30") (name "FAULT_OUT") (class "Default")
      (node (ref "IC6") (pin "6") (pinfunction "A3_6") (pintype "input"))
      (node (ref "U$1") (pin "PIN$9") (pinfunction "E/S_PIN$9") (pintype "bidirectional"))
      (node (ref "U$10") (pin "PIN$9") (pinfunction "E/S_PIN$9") (pintype "bidirectional"))
      (node (ref "U$11") (pin "PIN$9") (pinfunction "E/S_PIN$9") (pintype "bidirectional"))
      (node (ref "U$12") (pin "PIN$9") (pinfunction "E/S_PIN$9") (pintype "bidirectional"))
      (node (ref "U$13") (pin "PIN$9") (pinfunction "E/S_PIN$9") (pintype "bidirectional"))
      (node (ref "U$14") (pin "PIN$9") (pinfunction "E/S_PIN$9") (pintype "bidirectional"))
      (node (ref "U$15") (pin "PIN$9") (pinfunction "E/S_PIN$9") (pintype "bidirectional"))
      (node (ref "U$16") (pin "PIN$9") (pinfunction "E/S_PIN$9") (pintype "bidirectional"))
      (node (ref "U$2") (pin "PIN$9") (pinfunction "E/S_PIN$9") (pintype "bidirectional"))
      (node (ref "U$3") (pin "PIN$9") (pinfunction "E/S_PIN$9") (pintype "bidirectional"))
      (node (ref "U$4") (pin "PIN$9") (pinfunction "E/S_PIN$9") (pintype "bidirectional"))
      (node (ref "U$5") (pin "PIN$9") (pinfunction "E/S_PIN$9") (pintype "bidirectional"))
      (node (ref "U$6") (pin "PIN$9") (pinfunction "E/S_PIN$9") (pintype "bidirectional"))
      (node (ref "U$7") (pin "PIN$9") (pinfunction "E/S_PIN$9") (pintype "bidirectional"))
      (node (ref "U$8") (pin "PIN$9") (pinfunction "E/S_PIN$9") (pintype "bidirectional"))
      (node (ref "U$9") (pin "PIN$9") (pinfunction "E/S_PIN$9") (pintype "bidirectional"))
    )
    (net (code "31") (name "FAULT_READ") (class "Default")
      (node (ref "IC4") (pin "13") (pinfunction "Y2_13") (pintype "output"))
      (node (ref "IC6") (pin "19") (pinfunction "G_19") (pintype "input"))
    )
    (net (code "32") (name "FAULT_RESET") (class "Default")
      (node (ref "IC2") (pin "5") (pinfunction "R_5") (pintype "input"))
      (node (ref "IC3") (pin "2") (pinfunction "I1_2") (pintype "input"))
      (node (ref "IC4") (pin "12") (pinfunction "Y3_12") (pintype "output"))
    )
    (net (code "33") (name "FUNCTION_0") (class "Default")
      (node (ref "IC4") (pin "1") (pinfunction "A_1") (pintype "input"))
      (node (ref "R143") (pin "1") (pinfunction "1_1") (pintype "passive"))
      (node (ref "U025") (pin "14") (pinfunction "OUT1_14") (pintype "bidirectional"))
    )
    (net (code "34") (name "FUNCTION_0_I") (class "Default")
      (node (ref "R178") (pin "1") (pinfunction "1_1") (pintype "passive"))
      (node (ref "U030") (pin "3") (pinfunction "OUTB_3") (pintype "bidirectional"))
      (node (ref "U041") (pin "2") (pinfunction "C_2") (pintype "passive"))
    )
    (net (code "35") (name "FUNCTION_0_II") (class "Default")
      (node (ref "R178") (pin "2") (pinfunction "2_2") (pintype "passive"))
      (node (ref "U025") (pin "2") (pinfunction "CATH1_2") (pintype "bidirectional"))
      (node (ref "U041") (pin "1") (pinfunction "A_1") (pintype "passive"))
    )
    (net (code "36") (name "FUNCTION_0_Y") (class "Default")
      (node (ref "R138") (pin "1") (pinfunction "1_1") (pintype "passive"))
      (node (ref "U030") (pin "6") (pinfunction "INB1_6") (pintype "bidirectional"))
      (node (ref "X003") (pin "4") (pinfunction "4_4") (pintype "passive"))
    )
    (net (code "37") (name "FUNCTION_0_Z") (class "Default")
      (node (ref "R138") (pin "2") (pinfunction "2_2") (pintype "passive"))
      (node (ref "U030") (pin "5") (pinfunction "INB2_5") (pintype "bidirectional"))
      (node (ref "X003") (pin "5") (pinfunction "5_5") (pintype "passive"))
    )
    (net (code "38") (name "FUNCTION_1") (class "Default")
      (node (ref "IC4") (pin "2") (pinfunction "B_2") (pintype "input"))
      (node (ref "R144") (pin "1") (pinfunction "1_1") (pintype "passive"))
      (node (ref "U025") (pin "12") (pinfunction "OUT3_12") (pintype "bidirectional"))
    )
    (net (code "39") (name "FUNCTION_1_I") (class "Default")
      (node (ref "R179") (pin "1") (pinfunction "1_1") (pintype "passive"))
      (node (ref "U001") (pin "2") (pinfunction "OUTA_2") (pintype "bidirectional"))
      (node (ref "U042") (pin "2") (pinfunction "C_2") (pintype "passive"))
    )
    (net (code "40") (name "FUNCTION_1_II") (class "Default")
      (node (ref "R179") (pin "2") (pinfunction "2_2") (pintype "passive"))
      (node (ref "U025") (pin "6") (pinfunction "CATH3_6") (pintype "bidirectional"))
      (node (ref "U042") (pin "1") (pinfunction "A_1") (pintype "passive"))
    )
    (net (code "41") (name "FUNCTION_1_Y") (class "Default")
      (node (ref "R140") (pin "1") (pinfunction "1_1") (pintype "passive"))
      (node (ref "U001") (pin "8") (pinfunction "INA1_8") (pintype "bidirectional"))
      (node (ref "X003") (pin "6") (pinfunction "6_6") (pintype "passive"))
    )
    (net (code "42") (name "FUNCTION_1_Z") (class "Default")
      (node (ref "R140") (pin "2") (pinfunction "2_2") (pintype "passive"))
      (node (ref "U001") (pin "7") (pinfunction "INA2_7") (pintype "bidirectional"))
      (node (ref "X003") (pin "3") (pinfunction "3_3") (pintype "passive"))
    )
    (net (code "43") (name "GND") (class "Default")
      (node (ref "C10") (pin "2") (pinfunction "2_2") (pintype "passive"))
      (node (ref "C100") (pin "2") (pinfunction "2_2") (pintype "passive"))
      (node (ref "C101") (pin "2") (pinfunction "2_2") (pintype "passive"))
      (node (ref "C102") (pin "2") (pinfunction "2_2") (pintype "passive"))
      (node (ref "C103") (pin "2") (pinfunction "2_2") (pintype "passive"))
      (node (ref "C104") (pin "2") (pinfunction "2_2") (pintype "passive"))
      (node (ref "C107") (pin "2") (pinfunction "2_2") (pintype "passive"))
      (node (ref "C11") (pin "-") (pinfunction "-_-") (pintype "passive"))
      (node (ref "C110") (pin "2") (pinfunction "2_2") (pintype "passive"))
      (node (ref "C111") (pin "2") (pinfunction "2_2") (pintype "passive"))
      (node (ref "C112") (pin "2") (pinfunction "2_2") (pintype "passive"))
      (node (ref "C113") (pin "2") (pinfunction "2_2") (pintype "passive"))
      (node (ref "C114") (pin "2") (pinfunction "2_2") (pintype "passive"))
      (node (ref "C115") (pin "2") (pinfunction "2_2") (pintype "passive"))
      (node (ref "C116") (pin "2") (pinfunction "2_2") (pintype "passive"))
      (node (ref "C117") (pin "2") (pinfunction "2_2") (pintype "passive"))
      (node (ref "C118") (pin "2") (pinfunction "2_2") (pintype "passive"))
      (node (ref "C12") (pin "-") (pinfunction "-_-") (pintype "passive"))
      (node (ref "C13") (pin "-") (pinfunction "-_-") (pintype "passive"))
      (node (ref "C14") (pin "-") (pinfunction "-_-") (pintype "passive"))
      (node (ref "C15") (pin "2") (pinfunction "2_2") (pintype "passive"))
      (node (ref "C19") (pin "2") (pinfunction "2_2") (pintype "passive"))
      (node (ref "C20") (pin "2") (pinfunction "2_2") (pintype "passive"))
      (node (ref "C21") (pin "2") (pinfunction "2_2") (pintype "passive"))
      (node (ref "C22") (pin "2") (pinfunction "2_2") (pintype "passive"))
      (node (ref "C23") (pin "2") (pinfunction "2_2") (pintype "passive"))
      (node (ref "C24") (pin "2") (pinfunction "2_2") (pintype "passive"))
      (node (ref "C25") (pin "2") (pinfunction "2_2") (pintype "passive"))
      (node (ref "C26") (pin "2") (pinfunction "2_2") (pintype "passive"))
      (node (ref "C30") (pin "2") (pinfunction "2_2") (pintype "passive"))
      (node (ref "C31") (pin "2") (pinfunction "2_2") (pintype "passive"))
      (node (ref "C32") (pin "2") (pinfunction "2_2") (pintype "passive"))
      (node (ref "C33") (pin "2") (pinfunction "2_2") (pintype "passive"))
      (node (ref "C34") (pin "2") (pinfunction "2_2") (pintype "passive"))
      (node (ref "C35") (pin "2") (pinfunction "2_2") (pintype "passive"))
      (node (ref "C36") (pin "2") (pinfunction "2_2") (pintype "passive"))
      (node (ref "C37") (pin "2") (pinfunction "2_2") (pintype "passive"))
      (node (ref "C4") (pin "2") (pinfunction "2_2") (pintype "passive"))
      (node (ref "C41") (pin "2") (pinfunction "2_2") (pintype "passive"))
      (node (ref "C42") (pin "2") (pinfunction "2_2") (pintype "passive"))
      (node (ref "C43") (pin "2") (pinfunction "2_2") (pintype "passive"))
      (node (ref "C44") (pin "2") (pinfunction "2_2") (pintype "passive"))
      (node (ref "C45") (pin "2") (pinfunction "2_2") (pintype "passive"))
      (node (ref "C46") (pin "2") (pinfunction "2_2") (pintype "passive"))
      (node (ref "C47") (pin "2") (pinfunction "2_2") (pintype "passive"))
      (node (ref "C48") (pin "2") (pinfunction "2_2") (pintype "passive"))
      (node (ref "C5") (pin "2") (pinfunction "2_2") (pintype "passive"))
      (node (ref "C52") (pin "2") (pinfunction "2_2") (pintype "passive"))
      (node (ref "C53") (pin "2") (pinfunction "2_2") (pintype "passive"))
      (node (ref "C54") (pin "2") (pinfunction "2_2") (pintype "passive"))
      (node (ref "C55") (pin "2") (pinfunction "2_2") (pintype "passive"))
      (node (ref "C56") (pin "2") (pinfunction "2_2") (pintype "passive"))
      (node (ref "C57") (pin "2") (pinfunction "2_2") (pintype "passive"))
      (node (ref "C58") (pin "2") (pinfunction "2_2") (pintype "passive"))
      (node (ref "C59") (pin "2") (pinfunction "2_2") (pintype "passive"))
      (node (ref "C6") (pin "2") (pinfunction "2_2") (pintype "passive"))
      (node (ref "C63") (pin "2") (pinfunction "2_2") (pintype "passive"))
      (node (ref "C64") (pin "2") (pinfunction "2_2") (pintype "passive"))
      (node (ref "C65") (pin "2") (pinfunction "2_2") (pintype "passive"))
      (node (ref "C66") (pin "2") (pinfunction "2_2") (pintype "passive"))
      (node (ref "C67") (pin "2") (pinfunction "2_2") (pintype "passive"))
      (node (ref "C68") (pin "2") (pinfunction "2_2") (pintype "passive"))
      (node (ref "C69") (pin "2") (pinfunction "2_2") (pintype "passive"))
      (node (ref "C7") (pin "2") (pinfunction "2_2") (pintype "passive"))
      (node (ref "C70") (pin "2") (pinfunction "2_2") (pintype "passive"))
      (node (ref "C74") (pin "2") (pinfunction "2_2") (pintype "passive"))
      (node (ref "C75") (pin "2") (pinfunction "2_2") (pintype "passive"))
      (node (ref "C76") (pin "2") (pinfunction "2_2") (pintype "passive"))
      (node (ref "C77") (pin "2") (pinfunction "2_2") (pintype "passive"))
      (node (ref "C78") (pin "2") (pinfunction "2_2") (pintype "passive"))
      (node (ref "C79") (pin "2") (pinfunction "2_2") (pintype "passive"))
      (node (ref "C8") (pin "2") (pinfunction "2_2") (pintype "passive"))
      (node (ref "C80") (pin "2") (pinfunction "2_2") (pintype "passive"))
      (node (ref "C81") (pin "2") (pinfunction "2_2") (pintype "passive"))
      (node (ref "C85") (pin "2") (pinfunction "2_2") (pintype "passive"))
      (node (ref "C86") (pin "2") (pinfunction "2_2") (pintype "passive"))
      (node (ref "C87") (pin "2") (pinfunction "2_2") (pintype "passive"))
      (node (ref "C88") (pin "2") (pinfunction "2_2") (pintype "passive"))
      (node (ref "C89") (pin "2") (pinfunction "2_2") (pintype "passive"))
      (node (ref "C9") (pin "2") (pinfunction "2_2") (pintype "passive"))
      (node (ref "C90") (pin "2") (pinfunction "2_2") (pintype "passive"))
      (node (ref "C91") (pin "2") (pinfunction "2_2") (pintype "passive"))
      (node (ref "C92") (pin "2") (pinfunction "2_2") (pintype "passive"))
      (node (ref "C93") (pin "2") (pinfunction "2_2") (pintype "passive"))
      (node (ref "C94") (pin "2") (pinfunction "2_2") (pintype "passive"))
      (node (ref "C95") (pin "2") (pinfunction "2_2") (pintype "passive"))
      (node (ref "C96") (pin "2") (pinfunction "2_2") (pintype "passive"))
      (node (ref "C97") (pin "2") (pinfunction "2_2") (pintype "passive"))
      (node (ref "C98") (pin "2") (pinfunction "2_2") (pintype "passive"))
      (node (ref "C99") (pin "2") (pinfunction "2_2") (pintype "passive"))
      (node (ref "IC1") (pin "3") (pinfunction "GND_3") (pintype "passive"))
      (node (ref "IC2") (pin "8") (pinfunction "GND_8") (pintype "power_in"))
      (node (ref "IC3") (pin "7") (pinfunction "GND_7") (pintype "power_in"))
      (node (ref "IC4") (pin "3") (pinfunction "C_3") (pintype "input"))
      (node (ref "IC4") (pin "5") (pinfunction "G2B_5") (pintype "input"))
      (node (ref "IC4") (pin "8") (pinfunction "GND_8") (pintype "power_in"))
      (node (ref "IC5") (pin "2") (pinfunction "V-_2") (pintype "power_in"))
      (node (ref "IC6") (pin "1") (pinfunction "G_1") (pintype "input"))
      (node (ref "IC6") (pin "10") (pinfunction "GND_10") (pintype "power_in"))
      (node (ref "JP3") (pin "1") (pinfunction "1_1") (pintype "passive"))
      (node (ref "JP3") (pin "2") (pinfunction "2_2") (pintype "passive"))
      (node (ref "JP4") (pin "1") (pinfunction "1_1") (pintype "passive"))
      (node (ref "JP4") (pin "2") (pinfunction "2_2") (pintype "passive"))
      (node (ref "JP5") (pin "1") (pinfunction "1_1") (pintype "passive"))
      (node (ref "JP6") (pin "1") (pinfunction "1_1") (pintype "passive"))
      (node (ref "P9") (pin "10") (pinfunction "P_10") (pintype "passive"))
      (node (ref "P9") (pin "3") (pinfunction "P_3") (pintype "passive"))
      (node (ref "P9") (pin "4") (pinfunction "P_4") (pintype "passive"))
      (node (ref "P9") (pin "5") (pinfunction "P_5") (pintype "passive"))
      (node (ref "P9") (pin "9") (pinfunction "P_9") (pintype "passive"))
      (node (ref "R10") (pin "2") (pinfunction "2_2") (pintype "passive"))
      (node (ref "R103") (pin "2") (pinfunction "2_2") (pintype "passive"))
      (node (ref "R106") (pin "1") (pinfunction "1_1") (pintype "passive"))
      (node (ref "R107") (pin "2") (pinfunction "2_2") (pintype "passive"))
      (node (ref "R111") (pin "1") (pinfunction "1_1") (pintype "passive"))
      (node (ref "R112") (pin "1") (pinfunction "1_1") (pintype "passive"))
      (node (ref "R122") (pin "2") (pinfunction "2_2") (pintype "passive"))
      (node (ref "R125") (pin "1") (pinfunction "1_1") (pintype "passive"))
      (node (ref "R126") (pin "2") (pinfunction "2_2") (pintype "passive"))
      (node (ref "R13") (pin "1") (pinfunction "1_1") (pintype "passive"))
      (node (ref "R130") (pin "1") (pinfunction "1_1") (pintype "passive"))
      (node (ref "R131") (pin "1") (pinfunction "1_1") (pintype "passive"))
      (node (ref "R14") (pin "2") (pinfunction "2_2") (pintype "passive"))
      (node (ref "R145") (pin "1") (pinfunction "1_1") (pintype "passive"))
      (node (ref "R146") (pin "1") (pinfunction "1_1") (pintype "passive"))
      (node (ref "R152") (pin "2") (pinfunction "2_2") (pintype "passive"))
      (node (ref "R164") (pin "1") (pinfunction "1_1") (pintype "passive"))
      (node (ref "R165") (pin "1") (pinfunction "1_1") (pintype "passive"))
      (node (ref "R166") (pin "2") (pinfunction "2_2") (pintype "passive"))
      (node (ref "R170") (pin "1") (pinfunction "1_1") (pintype "passive"))
      (node (ref "R171") (pin "1") (pinfunction "1_1") (pintype "passive"))
      (node (ref "R18") (pin "1") (pinfunction "1_1") (pintype "passive"))
      (node (ref "R27") (pin "2") (pinfunction "2_2") (pintype "passive"))
      (node (ref "R30") (pin "1") (pinfunction "1_1") (pintype "passive"))
      (node (ref "R31") (pin "2") (pinfunction "2_2") (pintype "passive"))
      (node (ref "R35") (pin "1") (pinfunction "1_1") (pintype "passive"))
      (node (ref "R36") (pin "1") (pinfunction "1_1") (pintype "passive"))
      (node (ref "R46") (pin "2") (pinfunction "2_2") (pintype "passive"))
      (node (ref "R49") (pin "1") (pinfunction "1_1") (pintype "passive"))
      (node (ref "R50") (pin "2") (pinfunction "2_2") (pintype "passive"))
      (node (ref "R54") (pin "1") (pinfunction "1_1") (pintype "passive"))
      (node (ref "R55") (pin "1") (pinfunction "1_1") (pintype "passive"))
      (node (ref "R65") (pin "2") (pinfunction "2_2") (pintype "passive"))
      (node (ref "R68") (pin "1") (pinfunction "1_1") (pintype "passive"))
      (node (ref "R69") (pin "2") (pinfunction "2_2") (pintype "passive"))
      (node (ref "R73") (pin "1") (pinfunction "1_1") (pintype "passive"))
      (node (ref "R74") (pin "1") (pinfunction "1_1") (pintype "passive"))
      (node (ref "R84") (pin "2") (pinfunction "2_2") (pintype "passive"))
      (node (ref "R87") (pin "1") (pinfunction "1_1") (pintype "passive"))
      (node (ref "R88") (pin "2") (pinfunction "2_2") (pintype "passive"))
      (node (ref "R92") (pin "1") (pinfunction "1_1") (pintype "passive"))
      (node (ref "R93") (pin "1") (pinfunction "1_1") (pintype "passive"))
      (node (ref "U$1") (pin "PIN$5") (pinfunction "V-_PIN$5") (pintype "bidirectional"))
      (node (ref "U$1") (pin "PIN$6") (pinfunction "REF_PIN$6") (pintype "bidirectional"))
      (node (ref "U$1") (pin "PIN$7") (pinfunction "V-_PIN$7") (pintype "bidirectional"))
      (node (ref "U$10") (pin "PIN$5") (pinfunction "V-_PIN$5") (pintype "bidirectional"))
      (node (ref "U$10") (pin "PIN$6") (pinfunction "REF_PIN$6") (pintype "bidirectional"))
      (node (ref "U$10") (pin "PIN$7") (pinfunction "V-_PIN$7") (pintype "bidirectional"))
      (node (ref "U$11") (pin "PIN$5") (pinfunction "V-_PIN$5") (pintype "bidirectional"))
      (node (ref "U$11") (pin "PIN$6") (pinfunction "REF_PIN$6") (pintype "bidirectional"))
      (node (ref "U$11") (pin "PIN$7") (pinfunction "V-_PIN$7") (pintype "bidirectional"))
      (node (ref "U$12") (pin "PIN$5") (pinfunction "V-_PIN$5") (pintype "bidirectional"))
      (node (ref "U$12") (pin "PIN$6") (pinfunction "REF_PIN$6") (pintype "bidirectional"))
      (node (ref "U$12") (pin "PIN$7") (pinfunction "V-_PIN$7") (pintype "bidirectional"))
      (node (ref "U$13") (pin "PIN$5") (pinfunction "V-_PIN$5") (pintype "bidirectional"))
      (node (ref "U$13") (pin "PIN$6") (pinfunction "REF_PIN$6") (pintype "bidirectional"))
      (node (ref "U$13") (pin "PIN$7") (pinfunction "V-_PIN$7") (pintype "bidirectional"))
      (node (ref "U$14") (pin "PIN$5") (pinfunction "V-_PIN$5") (pintype "bidirectional"))
      (node (ref "U$14") (pin "PIN$6") (pinfunction "REF_PIN$6") (pintype "bidirectional"))
      (node (ref "U$14") (pin "PIN$7") (pinfunction "V-_PIN$7") (pintype "bidirectional"))
      (node (ref "U$15") (pin "PIN$5") (pinfunction "V-_PIN$5") (pintype "bidirectional"))
      (node (ref "U$15") (pin "PIN$6") (pinfunction "REF_PIN$6") (pintype "bidirectional"))
      (node (ref "U$15") (pin "PIN$7") (pinfunction "V-_PIN$7") (pintype "bidirectional"))
      (node (ref "U$16") (pin "PIN$5") (pinfunction "V-_PIN$5") (pintype "bidirectional"))
      (node (ref "U$16") (pin "PIN$6") (pinfunction "REF_PIN$6") (pintype "bidirectional"))
      (node (ref "U$16") (pin "PIN$7") (pinfunction "V-_PIN$7") (pintype "bidirectional"))
      (node (ref "U$2") (pin "PIN$5") (pinfunction "V-_PIN$5") (pintype "bidirectional"))
      (node (ref "U$2") (pin "PIN$6") (pinfunction "REF_PIN$6") (pintype "bidirectional"))
      (node (ref "U$2") (pin "PIN$7") (pinfunction "V-_PIN$7") (pintype "bidirectional"))
      (node (ref "U$3") (pin "PIN$5") (pinfunction "V-_PIN$5") (pintype "bidirectional"))
      (node (ref "U$3") (pin "PIN$6") (pinfunction "REF_PIN$6") (pintype "bidirectional"))
      (node (ref "U$3") (pin "PIN$7") (pinfunction "V-_PIN$7") (pintype "bidirectional"))
      (node (ref "U$4") (pin "PIN$5") (pinfunction "V-_PIN$5") (pintype "bidirectional"))
      (node (ref "U$4") (pin "PIN$6") (pinfunction "REF_PIN$6") (pintype "bidirectional"))
      (node (ref "U$4") (pin "PIN$7") (pinfunction "V-_PIN$7") (pintype "bidirectional"))
      (node (ref "U$5") (pin "PIN$5") (pinfunction "V-_PIN$5") (pintype "bidirectional"))
      (node (ref "U$5") (pin "PIN$6") (pinfunction "REF_PIN$6") (pintype "bidirectional"))
      (node (ref "U$5") (pin "PIN$7") (pinfunction "V-_PIN$7") (pintype "bidirectional"))
      (node (ref "U$6") (pin "PIN$5") (pinfunction "V-_PIN$5") (pintype "bidirectional"))
      (node (ref "U$6") (pin "PIN$6") (pinfunction "REF_PIN$6") (pintype "bidirectional"))
      (node (ref "U$6") (pin "PIN$7") (pinfunction "V-_PIN$7") (pintype "bidirectional"))
      (node (ref "U$7") (pin "PIN$5") (pinfunction "V-_PIN$5") (pintype "bidirectional"))
      (node (ref "U$7") (pin "PIN$6") (pinfunction "REF_PIN$6") (pintype "bidirectional"))
      (node (ref "U$7") (pin "PIN$7") (pinfunction "V-_PIN$7") (pintype "bidirectional"))
      (node (ref "U$8") (pin "PIN$5") (pinfunction "V-_PIN$5") (pintype "bidirectional"))
      (node (ref "U$8") (pin "PIN$6") (pinfunction "REF_PIN$6") (pintype "bidirectional"))
      (node (ref "U$8") (pin "PIN$7") (pinfunction "V-_PIN$7") (pintype "bidirectional"))
      (node (ref "U$9") (pin "PIN$5") (pinfunction "V-_PIN$5") (pintype "bidirectional"))
      (node (ref "U$9") (pin "PIN$6") (pinfunction "REF_PIN$6") (pintype "bidirectional"))
      (node (ref "U$9") (pin "PIN$7") (pinfunction "V-_PIN$7") (pintype "bidirectional"))
      (node (ref "U025") (pin "16") (pinfunction "GND2_16") (pintype "bidirectional"))
      (node (ref "U025") (pin "9") (pinfunction "GND1_9") (pintype "bidirectional"))
      (node (ref "U026") (pin "13") (pinfunction "CATH3_13") (pintype "bidirectional"))
      (node (ref "U026") (pin "15") (pinfunction "CATH4_15") (pintype "bidirectional"))
      (node (ref "U026") (pin "9") (pinfunction "GND2_9") (pintype "bidirectional"))
      (node (ref "U10") (pin "15") (pinfunction "GND_15") (pintype "passive"))
      (node (ref "U12") (pin "4") (pinfunction "V-_4") (pintype "power_in"))
      (node (ref "U13") (pin "4") (pinfunction "GND_4") (pintype "passive"))
      (node (ref "U14") (pin "4") (pinfunction "V-_4") (pintype "power_in"))
      (node (ref "U15") (pin "4") (pinfunction "GND_4") (pintype "passive"))
      (node (ref "U16") (pin "4") (pinfunction "V-_4") (pintype "power_in"))
      (node (ref "U17") (pin "4") (pinfunction "GND_4") (pintype "passive"))
      (node (ref "U18") (pin "4") (pinfunction "V-_4") (pintype "power_in"))
      (node (ref "U19") (pin "4") (pinfunction "GND_4") (pintype "passive"))
      (node (ref "U2") (pin "4") (pinfunction "GND_4") (pintype "passive"))
      (node (ref "U20") (pin "4") (pinfunction "V-_4") (pintype "power_in"))
      (node (ref "U3") (pin "4") (pinfunction "GND_4") (pintype "passive"))
      (node (ref "U4") (pin "4") (pinfunction "V-_4") (pintype "power_in"))
      (node (ref "U5") (pin "4") (pinfunction "V-_4") (pintype "power_in"))
      (node (ref "U6") (pin "4") (pinfunction "GND_4") (pintype "passive"))
      (node (ref "U7") (pin "4") (pinfunction "V-_4") (pintype "power_in"))
      (node (ref "U8") (pin "4") (pinfunction "GND_4") (pintype "passive"))
      (node (ref "U9") (pin "1") (pinfunction "REFLO_1") (pintype "input"))
      (node (ref "U9") (pin "20") (pinfunction "GND_20") (pintype "passive"))
      (node (ref "U9") (pin "21") (pinfunction "EP_21") (pintype "passive"))
    )
    (net (code "44") (name "GND1") (class "Default")
      (node (ref "C105") (pin "2") (pinfunction "2_2") (pintype "passive"))
      (node (ref "C106") (pin "2") (pinfunction "2_2") (pintype "passive"))
      (node (ref "C108") (pin "2") (pinfunction "2_2") (pintype "passive"))
      (node (ref "C109") (pin "2") (pinfunction "2_2") (pintype "passive"))
      (node (ref "C119") (pin "2") (pinfunction "2_2") (pintype "passive"))
      (node (ref "C129") (pin "2") (pinfunction "2_2") (pintype "passive"))
      (node (ref "C130") (pin "2") (pinfunction "2_2") (pintype "passive"))
      (node (ref "C131") (pin "2") (pinfunction "2_2") (pintype "passive"))
      (node (ref "R139") (pin "1") (pinfunction "1_1") (pintype "passive"))
      (node (ref "U001") (pin "4") (pinfunction "GND_4") (pintype "bidirectional"))
      (node (ref "U011") (pin "4") (pinfunction "GND_4") (pintype "bidirectional"))
      (node (ref "U021") (pin "4") (pinfunction "GND_4") (pintype "bidirectional"))
      (node (ref "U026") (pin "1") (pinfunction "GND1_1") (pintype "bidirectional"))
      (node (ref "U030") (pin "4") (pinfunction "GND_4") (pintype "bidirectional"))
      (node (ref "X002") (pin "G1") (pinfunction "S_G1") (pintype "passive"))
      (node (ref "X002") (pin "G2") (pinfunction "S_G2") (pintype "passive"))
      (node (ref "X003") (pin "8") (pinfunction "8_8") (pintype "passive"))
      (node (ref "X003") (pin "G1") (pinfunction "S_G1") (pintype "passive"))
      (node (ref "X003") (pin "G2") (pinfunction "S_G2") (pintype "passive"))
    )
    (net (code "45") (name "ISENSE_0") (class "Default")
      (node (ref "JP1") (pin "1") (pinfunction "1_1") (pintype "passive"))
      (node (ref "U10") (pin "8") (pinfunction "CH7/COM_8") (pintype "input"))
      (node (ref "U4") (pin "1") (pinfunction "OUT_A_1") (pintype "output"))
      (node (ref "U4") (pin "2") (pinfunction "-IN_A_2") (pintype "input"))
    )
    (net (code "46") (name "ISENSE_0_B") (class "Default")
      (node (ref "R18") (pin "2") (pinfunction "2_2") (pintype "passive"))
      (node (ref "U2") (pin "6") (pinfunction "OUT_6") (pintype "output"))
      (node (ref "U4") (pin "3") (pinfunction "+IN_A_3") (pintype "input"))
    )
    (net (code "47") (name "ISENSE_1") (class "Default")
      (node (ref "JP1") (pin "2") (pinfunction "2_2") (pintype "passive"))
      (node (ref "U10") (pin "7") (pinfunction "CH6_7") (pintype "input"))
      (node (ref "U5") (pin "1") (pinfunction "OUT_A_1") (pintype "output"))
      (node (ref "U5") (pin "2") (pinfunction "-IN_A_2") (pintype "input"))
    )
    (net (code "48") (name "ISENSE_1_B") (class "Default")
      (node (ref "R35") (pin "2") (pinfunction "2_2") (pintype "passive"))
      (node (ref "U3") (pin "6") (pinfunction "OUT_6") (pintype "output"))
      (node (ref "U5") (pin "3") (pinfunction "+IN_A_3") (pintype "input"))
    )
    (net (code "49") (name "ISENSE_2") (class "Default")
      (node (ref "JP1") (pin "3") (pinfunction "3_3") (pintype "passive"))
      (node (ref "U10") (pin "6") (pinfunction "CH5_6") (pintype "input"))
      (node (ref "U7") (pin "1") (pinfunction "OUT_A_1") (pintype "output"))
      (node (ref "U7") (pin "2") (pinfunction "-IN_A_2") (pintype "input"))
    )
    (net (code "50") (name "ISENSE_2_B") (class "Default")
      (node (ref "R54") (pin "2") (pinfunction "2_2") (pintype "passive"))
      (node (ref "U6") (pin "6") (pinfunction "OUT_6") (pintype "output"))
      (node (ref "U7") (pin "3") (pinfunction "+IN_A_3") (pintype "input"))
    )
    (net (code "51") (name "ISENSE_3") (class "Default")
      (node (ref "JP1") (pin "4") (pinfunction "4_4") (pintype "passive"))
      (node (ref "U10") (pin "5") (pinfunction "CH4_5") (pintype "input"))
      (node (ref "U12") (pin "1") (pinfunction "OUT_A_1") (pintype "output"))
      (node (ref "U12") (pin "2") (pinfunction "-IN_A_2") (pintype "input"))
    )
    (net (code "52") (name "ISENSE_3_B") (class "Default")
      (node (ref "R73") (pin "2") (pinfunction "2_2") (pintype "passive"))
      (node (ref "U12") (pin "3") (pinfunction "+IN_A_3") (pintype "input"))
      (node (ref "U8") (pin "6") (pinfunction "OUT_6") (pintype "output"))
    )
    (net (code "53") (name "ISENSE_4") (class "Default")
      (node (ref "JP1") (pin "5") (pinfunction "5_5") (pintype "passive"))
      (node (ref "U10") (pin "4") (pinfunction "CH3_4") (pintype "input"))
      (node (ref "U14") (pin "1") (pinfunction "OUT_A_1") (pintype "output"))
      (node (ref "U14") (pin "2") (pinfunction "-IN_A_2") (pintype "input"))
    )
    (net (code "54") (name "ISENSE_4_B") (class "Default")
      (node (ref "R92") (pin "2") (pinfunction "2_2") (pintype "passive"))
      (node (ref "U13") (pin "6") (pinfunction "OUT_6") (pintype "output"))
      (node (ref "U14") (pin "3") (pinfunction "+IN_A_3") (pintype "input"))
    )
    (net (code "55") (name "ISENSE_5") (class "Default")
      (node (ref "JP1") (pin "6") (pinfunction "6_6") (pintype "passive"))
      (node (ref "U10") (pin "3") (pinfunction "CH2_3") (pintype "input"))
      (node (ref "U16") (pin "1") (pinfunction "OUT_A_1") (pintype "output"))
      (node (ref "U16") (pin "2") (pinfunction "-IN_A_2") (pintype "input"))
    )
    (net (code "56") (name "ISENSE_5_B") (class "Default")
      (node (ref "R111") (pin "2") (pinfunction "2_2") (pintype "passive"))
      (node (ref "U15") (pin "6") (pinfunction "OUT_6") (pintype "output"))
      (node (ref "U16") (pin "3") (pinfunction "+IN_A_3") (pintype "input"))
    )
    (net (code "57") (name "ISENSE_6") (class "Default")
      (node (ref "JP1") (pin "7") (pinfunction "7_7") (pintype "passive"))
      (node (ref "U10") (pin "2") (pinfunction "CH1_2") (pintype "input"))
      (node (ref "U18") (pin "1") (pinfunction "OUT_A_1") (pintype "output"))
      (node (ref "U18") (pin "2") (pinfunction "-IN_A_2") (pintype "input"))
    )
    (net (code "58") (name "ISENSE_6_B") (class "Default")
      (node (ref "R130") (pin "2") (pinfunction "2_2") (pintype "passive"))
      (node (ref "U17") (pin "6") (pinfunction "OUT_6") (pintype "output"))
      (node (ref "U18") (pin "3") (pinfunction "+IN_A_3") (pintype "input"))
    )
    (net (code "59") (name "ISENSE_7") (class "Default")
      (node (ref "JP1") (pin "8") (pinfunction "8_8") (pintype "passive"))
      (node (ref "U10") (pin "1") (pinfunction "CH0_1") (pintype "input"))
      (node (ref "U20") (pin "1") (pinfunction "OUT_A_1") (pintype "output"))
      (node (ref "U20") (pin "2") (pinfunction "-IN_A_2") (pintype "input"))
    )
    (net (code "60") (name "ISENSE_7_B") (class "Default")
      (node (ref "R170") (pin "2") (pinfunction "2_2") (pintype "passive"))
      (node (ref "U19") (pin "6") (pinfunction "OUT_6") (pintype "output"))
      (node (ref "U20") (pin "3") (pinfunction "+IN_A_3") (pintype "input"))
    )
    (net (code "61") (name "LATCHED_FAULT") (class "Default")
      (node (ref "IC2") (pin "7") (pinfunction "Q_7") (pintype "output"))
      (node (ref "IC6") (pin "17") (pinfunction "A4_17") (pintype "input"))
      (node (ref "IC6") (pin "4") (pinfunction "A2_4") (pintype "input"))
    )
    (net (code "62") (name "MISO") (class "Default")
      (node (ref "IC6") (pin "2") (pinfunction "A1_2") (pintype "input"))
      (node (ref "IC6") (pin "3") (pinfunction "Y4_3") (pintype "tri_state"))
      (node (ref "U10") (pin "13") (pinfunction "SDO_13") (pintype "output"))
    )
    (net (code "63") (name "MISO_A") (class "Default")
      (node (ref "U011") (pin "6") (pinfunction "OUTB1_6") (pintype "bidirectional"))
      (node (ref "X002") (pin "2") (pinfunction "2_2") (pintype "passive"))
    )
    (net (code "64") (name "MISO_B") (class "Default")
      (node (ref "U011") (pin "5") (pinfunction "OUTB2_5") (pintype "bidirectional"))
      (node (ref "X002") (pin "1") (pinfunction "1_1") (pintype "passive"))
    )
    (net (code "65") (name "MISO_BUFFER") (class "Default")
      (node (ref "IC6") (pin "18") (pinfunction "Y1_18") (pintype "tri_state"))
      (node (ref "R183") (pin "2") (pinfunction "2_2") (pintype "passive"))
      (node (ref "U046") (pin "2") (pinfunction "C_2") (pintype "passive"))
    )
    (net (code "66") (name "MISO_I") (class "Default")
      (node (ref "R173") (pin "1") (pinfunction "1_1") (pintype "passive"))
      (node (ref "U011") (pin "3") (pinfunction "INB_3") (pintype "bidirectional"))
      (node (ref "U026") (pin "2") (pinfunction "OUT4_2") (pintype "bidirectional"))
    )
    (net (code "67") (name "MISO_II") (class "Default")
      (node (ref "R183") (pin "1") (pinfunction "1_1") (pintype "passive"))
      (node (ref "U026") (pin "16") (pinfunction "AN4_16") (pintype "bidirectional"))
      (node (ref "U046") (pin "1") (pinfunction "A_1") (pintype "passive"))
    )
    (net (code "68") (name "MOSI") (class "Default")
      (node (ref "R176") (pin "1") (pinfunction "1_1") (pintype "passive"))
      (node (ref "U026") (pin "10") (pinfunction "OUT2_10") (pintype "bidirectional"))
      (node (ref "U10") (pin "14") (pinfunction "SDI_14") (pintype "input"))
      (node (ref "U9") (pin "11") (pinfunction "SDI_11") (pintype "input"))
    )
    (net (code "69") (name "MOSI_A") (class "Default")
      (node (ref "R000") (pin "1") (pinfunction "1_1") (pintype "passive"))
      (node (ref "U021") (pin "8") (pinfunction "INA1_8") (pintype "bidirectional"))
      (node (ref "X002") (pin "8") (pinfunction "8_8") (pintype "passive"))
    )
    (net (code "70") (name "MOSI_B") (class "Default")
      (node (ref "R000") (pin "2") (pinfunction "2_2") (pintype "passive"))
      (node (ref "U021") (pin "7") (pinfunction "INA2_7") (pintype "bidirectional"))
      (node (ref "X002") (pin "7") (pinfunction "7_7") (pintype "passive"))
    )
    (net (code "71") (name "MOSI_I") (class "Default")
      (node (ref "R181") (pin "1") (pinfunction "1_1") (pintype "passive"))
      (node (ref "U021") (pin "2") (pinfunction "OUTA_2") (pintype "bidirectional"))
      (node (ref "U044") (pin "2") (pinfunction "C_2") (pintype "passive"))
    )
    (net (code "72") (name "MOSI_II") (class "Default")
      (node (ref "R181") (pin "2") (pinfunction "2_2") (pintype "passive"))
      (node (ref "U026") (pin "8") (pinfunction "CATH2_8") (pintype "bidirectional"))
      (node (ref "U044") (pin "1") (pinfunction "A_1") (pintype "passive"))
    )
    (net (code "73") (name "NOT_LATCHED_FAULT") (class "Default")
      (node (ref "IC6") (pin "16") (pinfunction "Y2_16") (pintype "tri_state"))
      (node (ref "LED3") (pin "C") (pinfunction "C_C") (pintype "passive"))
      (node (ref "R184") (pin "1") (pinfunction "1_1") (pintype "passive"))
    )
    (net (code "74") (name "Net-(C1-Pad1)") (class "Default")
      (node (ref "C1") (pin "1") (pinfunction "1_1") (pintype "passive"))
      (node (ref "R2") (pin "2") (pinfunction "2_2") (pintype "passive"))
    )
    (net (code "75") (name "Net-(C2-Pad1)") (class "Default")
      (node (ref "C2") (pin "1") (pinfunction "1_1") (pintype "passive"))
      (node (ref "R5") (pin "2") (pinfunction "2_2") (pintype "passive"))
    )
    (net (code "76") (name "Net-(C3-Pad1)") (class "Default")
      (node (ref "C3") (pin "1") (pinfunction "1_1") (pintype "passive"))
      (node (ref "R6") (pin "1") (pinfunction "1_1") (pintype "passive"))
      (node (ref "R8") (pin "2") (pinfunction "2_2") (pintype "passive"))
    )
    (net (code "77") (name "Net-(C3-Pad2)") (class "Default")
      (node (ref "C3") (pin "2") (pinfunction "2_2") (pintype "passive"))
      (node (ref "R7") (pin "1") (pinfunction "1_1") (pintype "passive"))
      (node (ref "R9") (pin "2") (pinfunction "2_2") (pintype "passive"))
    )
    (net (code "78") (name "Net-(C16-Pad1)") (class "Default")
      (node (ref "C16") (pin "1") (pinfunction "1_1") (pintype "passive"))
      (node (ref "R19") (pin "2") (pinfunction "2_2") (pintype "passive"))
    )
    (net (code "79") (name "Net-(C17-Pad1)") (class "Default")
      (node (ref "C17") (pin "1") (pinfunction "1_1") (pintype "passive"))
      (node (ref "R22") (pin "2") (pinfunction "2_2") (pintype "passive"))
    )
    (net (code "80") (name "Net-(C18-Pad1)") (class "Default")
      (node (ref "C18") (pin "1") (pinfunction "1_1") (pintype "passive"))
      (node (ref "R23") (pin "1") (pinfunction "1_1") (pintype "passive"))
      (node (ref "R25") (pin "2") (pinfunction "2_2") (pintype "passive"))
    )
    (net (code "81") (name "Net-(C18-Pad2)") (class "Default")
      (node (ref "C18") (pin "2") (pinfunction "2_2") (pintype "passive"))
      (node (ref "R24") (pin "1") (pinfunction "1_1") (pintype "passive"))
      (node (ref "R26") (pin "2") (pinfunction "2_2") (pintype "passive"))
    )
    (net (code "82") (name "Net-(C27-Pad1)") (class "Default")
      (node (ref "C27") (pin "1") (pinfunction "1_1") (pintype "passive"))
      (node (ref "R38") (pin "2") (pinfunction "2_2") (pintype "passive"))
    )
    (net (code "83") (name "Net-(C28-Pad1)") (class "Default")
      (node (ref "C28") (pin "1") (pinfunction "1_1") (pintype "passive"))
      (node (ref "R41") (pin "2") (pinfunction "2_2") (pintype "passive"))
    )
    (net (code "84") (name "Net-(C29-Pad1)") (class "Default")
      (node (ref "C29") (pin "1") (pinfunction "1_1") (pintype "passive"))
      (node (ref "R42") (pin "1") (pinfunction "1_1") (pintype "passive"))
      (node (ref "R44") (pin "2") (pinfunction "2_2") (pintype "passive"))
    )
    (net (code "85") (name "Net-(C29-Pad2)") (class "Default")
      (node (ref "C29") (pin "2") (pinfunction "2_2") (pintype "passive"))
      (node (ref "R43") (pin "1") (pinfunction "1_1") (pintype "passive"))
      (node (ref "R45") (pin "2") (pinfunction "2_2") (pintype "passive"))
    )
    (net (code "86") (name "Net-(C38-Pad1)") (class "Default")
      (node (ref "C38") (pin "1") (pinfunction "1_1") (pintype "passive"))
      (node (ref "R57") (pin "2") (pinfunction "2_2") (pintype "passive"))
    )
    (net (code "87") (name "Net-(C39-Pad1)") (class "Default")
      (node (ref "C39") (pin "1") (pinfunction "1_1") (pintype "passive"))
      (node (ref "R60") (pin "2") (pinfunction "2_2") (pintype "passive"))
    )
    (net (code "88") (name "Net-(C40-Pad1)") (class "Default")
      (node (ref "C40") (pin "1") (pinfunction "1_1") (pintype "passive"))
      (node (ref "R61") (pin "1") (pinfunction "1_1") (pintype "passive"))
      (node (ref "R63") (pin "2") (pinfunction "2_2") (pintype "passive"))
    )
    (net (code "89") (name "Net-(C40-Pad2)") (class "Default")
      (node (ref "C40") (pin "2") (pinfunction "2_2") (pintype "passive"))
      (node (ref "R62") (pin "1") (pinfunction "1_1") (pintype "passive"))
      (node (ref "R64") (pin "2") (pinfunction "2_2") (pintype "passive"))
    )
    (net (code "90") (name "Net-(C49-Pad1)") (class "Default")
      (node (ref "C49") (pin "1") (pinfunction "1_1") (pintype "passive"))
      (node (ref "R76") (pin "2") (pinfunction "2_2") (pintype "passive"))
    )
    (net (code "91") (name "Net-(C50-Pad1)") (class "Default")
      (node (ref "C50") (pin "1") (pinfunction "1_1") (pintype "passive"))
      (node (ref "R79") (pin "2") (pinfunction "2_2") (pintype "passive"))
    )
    (net (code "92") (name "Net-(C51-Pad1)") (class "Default")
      (node (ref "C51") (pin "1") (pinfunction "1_1") (pintype "passive"))
      (node (ref "R80") (pin "1") (pinfunction "1_1") (pintype "passive"))
      (node (ref "R82") (pin "2") (pinfunction "2_2") (pintype "passive"))
    )
    (net (code "93") (name "Net-(C51-Pad2)") (class "Default")
      (node (ref "C51") (pin "2") (pinfunction "2_2") (pintype "passive"))
      (node (ref "R81") (pin "1") (pinfunction "1_1") (pintype "passive"))
      (node (ref "R83") (pin "2") (pinfunction "2_2") (pintype "passive"))
    )
    (net (code "94") (name "Net-(C60-Pad1)") (class "Default")
      (node (ref "C60") (pin "1") (pinfunction "1_1") (pintype "passive"))
      (node (ref "R95") (pin "2") (pinfunction "2_2") (pintype "passive"))
    )
    (net (code "95") (name "Net-(C61-Pad1)") (class "Default")
      (node (ref "C61") (pin "1") (pinfunction "1_1") (pintype "passive"))
      (node (ref "R98") (pin "2") (pinfunction "2_2") (pintype "passive"))
    )
    (net (code "96") (name "Net-(C62-Pad1)") (class "Default")
      (node (ref "C62") (pin "1") (pinfunction "1_1") (pintype "passive"))
      (node (ref "R101") (pin "2") (pinfunction "2_2") (pintype "passive"))
      (node (ref "R99") (pin "1") (pinfunction "1_1") (pintype "passive"))
    )
    (net (code "97") (name "Net-(C62-Pad2)") (class "Default")
      (node (ref "C62") (pin "2") (pinfunction "2_2") (pintype "passive"))
      (node (ref "R100") (pin "1") (pinfunction "1_1") (pintype "passive"))
      (node (ref "R102") (pin "2") (pinfunction "2_2") (pintype "passive"))
    )
    (net (code "98") (name "Net-(C71-Pad1)") (class "Default")
      (node (ref "C71") (pin "1") (pinfunction "1_1") (pintype "passive"))
      (node (ref "R114") (pin "2") (pinfunction "2_2") (pintype "passive"))
    )
    (net (code "99") (name "Net-(C72-Pad1)") (class "Default")
      (node (ref "C72") (pin "1") (pinfunction "1_1") (pintype "passive"))
      (node (ref "R117") (pin "2") (pinfunction "2_2") (pintype "passive"))
    )
    (net (code "100") (name "Net-(C73-Pad1)") (class "Default")
      (node (ref "C73") (pin "1") (pinfunction "1_1") (pintype "passive"))
      (node (ref "R118") (pin "1") (pinfunction "1_1") (pintype "passive"))
      (node (ref "R120") (pin "2") (pinfunction "2_2") (pintype "passive"))
    )
    (net (code "101") (name "Net-(C73-Pad2)") (class "Default")
      (node (ref "C73") (pin "2") (pinfunction "2_2") (pintype "passive"))
      (node (ref "R119") (pin "1") (pinfunction "1_1") (pintype "passive"))
      (node (ref "R121") (pin "2") (pinfunction "2_2") (pintype "passive"))
    )
    (net (code "102") (name "Net-(C82-Pad1)") (class "Default")
      (node (ref "C82") (pin "1") (pinfunction "1_1") (pintype "passive"))
      (node (ref "R133") (pin "2") (pinfunction "2_2") (pintype "passive"))
    )
    (net (code "103") (name "Net-(C83-Pad1)") (class "Default")
      (node (ref "C83") (pin "1") (pinfunction "1_1") (pintype "passive"))
      (node (ref "R136") (pin "2") (pinfunction "2_2") (pintype "passive"))
    )
    (net (code "104") (name "Net-(C84-Pad1)") (class "Default")
      (node (ref "C84") (pin "1") (pinfunction "1_1") (pintype "passive"))
      (node (ref "R148") (pin "1") (pinfunction "1_1") (pintype "passive"))
      (node (ref "R150") (pin "2") (pinfunction "2_2") (pintype "passive"))
    )
    (net (code "105") (name "Net-(C84-Pad2)") (class "Default")
      (node (ref "C84") (pin "2") (pinfunction "2_2") (pintype "passive"))
      (node (ref "R149") (pin "1") (pinfunction "1_1") (pintype "passive"))
      (node (ref "R151") (pin "2") (pinfunction "2_2") (pintype "passive"))
    )
    (net (code "106") (name "Net-(C120-Pad1)") (class "Default")
      (node (ref "C120") (pin "1") (pinfunction "1_1") (pintype "passive"))
      (node (ref "R186") (pin "2") (pinfunction "2_2") (pintype "passive"))
      (node (ref "R3") (pin "1") (pinfunction "1_1") (pintype "passive"))
    )
    (net (code "107") (name "Net-(C121-Pad1)") (class "Default")
      (node (ref "C121") (pin "1") (pinfunction "1_1") (pintype "passive"))
      (node (ref "R187") (pin "2") (pinfunction "2_2") (pintype "passive"))
      (node (ref "R20") (pin "1") (pinfunction "1_1") (pintype "passive"))
    )
    (net (code "108") (name "Net-(C122-Pad1)") (class "Default")
      (node (ref "C122") (pin "1") (pinfunction "1_1") (pintype "passive"))
      (node (ref "R185") (pin "2") (pinfunction "2_2") (pintype "passive"))
      (node (ref "R39") (pin "1") (pinfunction "1_1") (pintype "passive"))
    )
    (net (code "109") (name "Net-(C123-Pad1)") (class "Default")
      (node (ref "C123") (pin "1") (pinfunction "1_1") (pintype "passive"))
      (node (ref "R192") (pin "2") (pinfunction "2_2") (pintype "passive"))
      (node (ref "R58") (pin "1") (pinfunction "1_1") (pintype "passive"))
    )
    (net (code "110") (name "Net-(C124-Pad1)") (class "Default")
      (node (ref "C124") (pin "1") (pinfunction "1_1") (pintype "passive"))
      (node (ref "R188") (pin "2") (pinfunction "2_2") (pintype "passive"))
      (node (ref "R77") (pin "1") (pinfunction "1_1") (pintype "passive"))
    )
    (net (code "111") (name "Net-(C125-Pad1)") (class "Default")
      (node (ref "C125") (pin "1") (pinfunction "1_1") (pintype "passive"))
      (node (ref "R189") (pin "2") (pinfunction "2_2") (pintype "passive"))
      (node (ref "R96") (pin "1") (pinfunction "1_1") (pintype "passive"))
    )
    (net (code "112") (name "Net-(C126-Pad1)") (class "Default")
      (node (ref "C126") (pin "1") (pinfunction "1_1") (pintype "passive"))
      (node (ref "R115") (pin "1") (pinfunction "1_1") (pintype "passive"))
      (node (ref "R191") (pin "2") (pinfunction "2_2") (pintype "passive"))
    )
    (net (code "113") (name "Net-(C127-Pad1)") (class "Default")
      (node (ref "C127") (pin "1") (pinfunction "1_1") (pintype "passive"))
      (node (ref "R134") (pin "1") (pinfunction "1_1") (pintype "passive"))
      (node (ref "R190") (pin "2") (pinfunction "2_2") (pintype "passive"))
    )
    (net (code "114") (name "Net-(LED1-PadC)") (class "Default")
      (node (ref "LED1") (pin "C") (pinfunction "C_C") (pintype "passive"))
      (node (ref "R146") (pin "2") (pinfunction "2_2") (pintype "passive"))
    )
    (net (code "115") (name "Net-(LED2-PadC)") (class "Default")
      (node (ref "LED2") (pin "C") (pinfunction "C_C") (pintype "passive"))
      (node (ref "R145") (pin "2") (pinfunction "2_2") (pintype "passive"))
    )
    (net (code "116") (name "Net-(LED3-PadA)") (class "Default")
      (node (ref "LED3") (pin "A") (pinfunction "A_A") (pintype "passive"))
      (node (ref "R141") (pin "1") (pinfunction "1_1") (pintype "passive"))
    )
    (net (code "117") (name "Net-(P1A-P)") (class "Default")
      (node (ref "P1") (pin "1") (pinfunction "P_1") (pintype "passive"))
      (node (ref "R147") (pin "2") (pinfunction "2_2") (pintype "passive"))
    )
    (net (code "118") (name "Net-(P1B-P)") (class "Default")
      (node (ref "P1") (pin "2") (pinfunction "P_2") (pintype "passive"))
      (node (ref "R11") (pin "2") (pinfunction "2_2") (pintype "passive"))
      (node (ref "R4") (pin "1") (pinfunction "1_1") (pintype "passive"))
      (node (ref "R5") (pin "1") (pinfunction "1_1") (pintype "passive"))
      (node (ref "U2") (pin "1") (pinfunction "VIN-_1") (pintype "input"))
    )
    (net (code "119") (name "Net-(P2A-P)") (class "Default")
      (node (ref "P2") (pin "1") (pinfunction "P_1") (pintype "passive"))
      (node (ref "R34") (pin "2") (pinfunction "2_2") (pintype "passive"))
    )
    (net (code "120") (name "Net-(P2B-P)") (class "Default")
      (node (ref "P2") (pin "2") (pinfunction "P_2") (pintype "passive"))
      (node (ref "R21") (pin "1") (pinfunction "1_1") (pintype "passive"))
      (node (ref "R22") (pin "1") (pinfunction "1_1") (pintype "passive"))
      (node (ref "R28") (pin "2") (pinfunction "2_2") (pintype "passive"))
      (node (ref "U3") (pin "1") (pinfunction "VIN-_1") (pintype "input"))
    )
    (net (code "121") (name "Net-(P3A-P)") (class "Default")
      (node (ref "P3") (pin "1") (pinfunction "P_1") (pintype "passive"))
      (node (ref "R53") (pin "2") (pinfunction "2_2") (pintype "passive"))
    )
    (net (code "122") (name "Net-(P3B-P)") (class "Default")
      (node (ref "P3") (pin "2") (pinfunction "P_2") (pintype "passive"))
      (node (ref "R40") (pin "1") (pinfunction "1_1") (pintype "passive"))
      (node (ref "R41") (pin "1") (pinfunction "1_1") (pintype "passive"))
      (node (ref "R47") (pin "2") (pinfunction "2_2") (pintype "passive"))
      (node (ref "U6") (pin "1") (pinfunction "VIN-_1") (pintype "input"))
    )
    (net (code "123") (name "Net-(P4A-P)") (class "Default")
      (node (ref "P4") (pin "1") (pinfunction "P_1") (pintype "passive"))
      (node (ref "R72") (pin "2") (pinfunction "2_2") (pintype "passive"))
    )
    (net (code "124") (name "Net-(P4B-P)") (class "Default")
      (node (ref "P4") (pin "2") (pinfunction "P_2") (pintype "passive"))
      (node (ref "R59") (pin "1") (pinfunction "1_1") (pintype "passive"))
      (node (ref "R60") (pin "1") (pinfunction "1_1") (pintype "passive"))
      (node (ref "R66") (pin "2") (pinfunction "2_2") (pintype "passive"))
      (node (ref "U8") (pin "1") (pinfunction "VIN-_1") (pintype "input"))
    )
    (net (code "125") (name "Net-(P5A-P)") (class "Default")
      (node (ref "P5") (pin "1") (pinfunction "P_1") (pintype "passive"))
      (node (ref "R91") (pin "2") (pinfunction "2_2") (pintype "passive"))
    )
    (net (code "126") (name "Net-(P5B-P)") (class "Default")
      (node (ref "P5") (pin "2") (pinfunction "P_2") (pintype "passive"))
      (node (ref "R78") (pin "1") (pinfunction "1_1") (pintype "passive"))
      (node (ref "R79") (pin "1") (pinfunction "1_1") (pintype "passive"))
      (node (ref "R85") (pin "2") (pinfunction "2_2") (pintype "passive"))
      (node (ref "U13") (pin "1") (pinfunction "VIN-_1") (pintype "input"))
    )
    (net (code "127") (name "Net-(P6A-P)") (class "Default")
      (node (ref "P6") (pin "1") (pinfunction "P_1") (pintype "passive"))
      (node (ref "R110") (pin "2") (pinfunction "2_2") (pintype "passive"))
    )
    (net (code "128") (name "Net-(P6B-P)") (class "Default")
      (node (ref "P6") (pin "2") (pinfunction "P_2") (pintype "passive"))
      (node (ref "R104") (pin "2") (pinfunction "2_2") (pintype "passive"))
      (node (ref "R97") (pin "1") (pinfunction "1_1") (pintype "passive"))
      (node (ref "R98") (pin "1") (pinfunction "1_1") (pintype "passive"))
      (node (ref "U15") (pin "1") (pinfunction "VIN-_1") (pintype "input"))
    )
    (net (code "129") (name "Net-(P7A-P)") (class "Default")
      (node (ref "P7") (pin "1") (pinfunction "P_1") (pintype "passive"))
      (node (ref "R129") (pin "2") (pinfunction "2_2") (pintype "passive"))
    )
    (net (code "130") (name "Net-(P7B-P)") (class "Default")
      (node (ref "P7") (pin "2") (pinfunction "P_2") (pintype "passive"))
      (node (ref "R116") (pin "1") (pinfunction "1_1") (pintype "passive"))
      (node (ref "R117") (pin "1") (pinfunction "1_1") (pintype "passive"))
      (node (ref "R123") (pin "2") (pinfunction "2_2") (pintype "passive"))
      (node (ref "U17") (pin "1") (pinfunction "VIN-_1") (pintype "input"))
    )
    (net (code "131") (name "Net-(P8A-P)") (class "Default")
      (node (ref "P8") (pin "1") (pinfunction "P_1") (pintype "passive"))
      (node (ref "R169") (pin "2") (pinfunction "2_2") (pintype "passive"))
    )
    (net (code "132") (name "Net-(P8B-P)") (class "Default")
      (node (ref "P8") (pin "2") (pinfunction "P_2") (pintype "passive"))
      (node (ref "R135") (pin "1") (pinfunction "1_1") (pintype "passive"))
      (node (ref "R136") (pin "1") (pinfunction "1_1") (pintype "passive"))
      (node (ref "R153") (pin "2") (pinfunction "2_2") (pintype "passive"))
      (node (ref "U19") (pin "1") (pinfunction "VIN-_1") (pintype "input"))
    )
    (net (code "133") (name "Net-(P9A-P)") (class "Default")
      (node (ref "P9") (pin "1") (pinfunction "P_1") (pintype "passive"))
      (node (ref "P9") (pin "2") (pinfunction "P_2") (pintype "passive"))
      (node (ref "P9") (pin "6") (pinfunction "P_6") (pintype "passive"))
      (node (ref "P9") (pin "7") (pinfunction "P_7") (pintype "passive"))
      (node (ref "P9") (pin "8") (pinfunction "P_8") (pintype "passive"))
      (node (ref "U031") (pin "P$1") (pinfunction "1_P$1") (pintype "passive"))
    )
    (net (code "134") (name "Net-(R33-Pad2)") (class "Default")
      (node (ref "R33") (pin "2") (pinfunction "2_2") (pintype "passive"))
      (node (ref "R34") (pin "1") (pinfunction "1_1") (pintype "passive"))
      (node (ref "U$4") (pin "PIN$1") (pinfunction "OUT_PIN$1") (pintype "bidirectional"))
      (node (ref "U$4") (pin "PIN$2") (pinfunction "OUT_PIN$2") (pintype "bidirectional"))
    )
    (net (code "135") (name "Net-(R52-Pad2)") (class "Default")
      (node (ref "R52") (pin "2") (pinfunction "2_2") (pintype "passive"))
      (node (ref "R53") (pin "1") (pinfunction "1_1") (pintype "passive"))
      (node (ref "U$6") (pin "PIN$1") (pinfunction "OUT_PIN$1") (pintype "bidirectional"))
      (node (ref "U$6") (pin "PIN$2") (pinfunction "OUT_PIN$2") (pintype "bidirectional"))
    )
    (net (code "136") (name "Net-(R71-Pad2)") (class "Default")
      (node (ref "R71") (pin "2") (pinfunction "2_2") (pintype "passive"))
      (node (ref "R72") (pin "1") (pinfunction "1_1") (pintype "passive"))
      (node (ref "U$8") (pin "PIN$1") (pinfunction "OUT_PIN$1") (pintype "bidirectional"))
      (node (ref "U$8") (pin "PIN$2") (pinfunction "OUT_PIN$2") (pintype "bidirectional"))
    )
    (net (code "137") (name "Net-(R90-Pad2)") (class "Default")
      (node (ref "R90") (pin "2") (pinfunction "2_2") (pintype "passive"))
      (node (ref "R91") (pin "1") (pinfunction "1_1") (pintype "passive"))
      (node (ref "U$10") (pin "PIN$1") (pinfunction "OUT_PIN$1") (pintype "bidirectional"))
      (node (ref "U$10") (pin "PIN$2") (pinfunction "OUT_PIN$2") (pintype "bidirectional"))
    )
    (net (code "138") (name "Net-(R109-Pad2)") (class "Default")
      (node (ref "R109") (pin "2") (pinfunction "2_2") (pintype "passive"))
      (node (ref "R110") (pin "1") (pinfunction "1_1") (pintype "passive"))
      (node (ref "U$12") (pin "PIN$1") (pinfunction "OUT_PIN$1") (pintype "bidirectional"))
      (node (ref "U$12") (pin "PIN$2") (pinfunction "OUT_PIN$2") (pintype "bidirectional"))
    )
    (net (code "139") (name "Net-(R128-Pad2)") (class "Default")
      (node (ref "R128") (pin "2") (pinfunction "2_2") (pintype "passive"))
      (node (ref "R129") (pin "1") (pinfunction "1_1") (pintype "passive"))
      (node (ref "U$14") (pin "PIN$1") (pinfunction "OUT_PIN$1") (pintype "bidirectional"))
      (node (ref "U$14") (pin "PIN$2") (pinfunction "OUT_PIN$2") (pintype "bidirectional"))
    )
    (net (code "140") (name "Net-(R147-Pad1)") (class "Default")
      (node (ref "R147") (pin "1") (pinfunction "1_1") (pintype "passive"))
      (node (ref "R16") (pin "2") (pinfunction "2_2") (pintype "passive"))
      (node (ref "U$2") (pin "PIN$1") (pinfunction "OUT_PIN$1") (pintype "bidirectional"))
      (node (ref "U$2") (pin "PIN$2") (pinfunction "OUT_PIN$2") (pintype "bidirectional"))
    )
    (net (code "141") (name "Net-(R168-Pad2)") (class "Default")
      (node (ref "R168") (pin "2") (pinfunction "2_2") (pintype "passive"))
      (node (ref "R169") (pin "1") (pinfunction "1_1") (pintype "passive"))
      (node (ref "U$16") (pin "PIN$1") (pinfunction "OUT_PIN$1") (pintype "bidirectional"))
      (node (ref "U$16") (pin "PIN$2") (pinfunction "OUT_PIN$2") (pintype "bidirectional"))
    )
    (net (code "142") (name "Net-(U$1-+)") (class "Default")
      (node (ref "C120") (pin "2") (pinfunction "2_2") (pintype "passive"))
      (node (ref "C2") (pin "2") (pinfunction "2_2") (pintype "passive"))
      (node (ref "R186") (pin "1") (pinfunction "1_1") (pintype "passive"))
      (node (ref "R4") (pin "2") (pinfunction "2_2") (pintype "passive"))
      (node (ref "R7") (pin "2") (pinfunction "2_2") (pintype "passive"))
      (node (ref "U$1") (pin "PIN$4") (pinfunction "+_PIN$4") (pintype "bidirectional"))
    )
    (net (code "143") (name "Net-(U$1--)") (class "Default")
      (node (ref "R1") (pin "1") (pinfunction "1_1") (pintype "passive"))
      (node (ref "R2") (pin "1") (pinfunction "1_1") (pintype "passive"))
      (node (ref "R3") (pin "2") (pinfunction "2_2") (pintype "passive"))
      (node (ref "R6") (pin "2") (pinfunction "2_2") (pintype "passive"))
      (node (ref "U$1") (pin "PIN$3") (pinfunction "-_PIN$3") (pintype "bidirectional"))
    )
    (net (code "144") (name "Net-(U$1-ILIM)") (class "Default")
      (node (ref "R10") (pin "1") (pinfunction "1_1") (pintype "passive"))
      (node (ref "U$1") (pin "PIN$8") (pinfunction "ILIM_PIN$8") (pintype "bidirectional"))
    )
    (net (code "145") (name "Net-(U$2-+)") (class "Default")
      (node (ref "R12") (pin "2") (pinfunction "2_2") (pintype "passive"))
      (node (ref "R13") (pin "2") (pinfunction "2_2") (pintype "passive"))
      (node (ref "U$2") (pin "PIN$4") (pinfunction "+_PIN$4") (pintype "bidirectional"))
    )
    (net (code "146") (name "Net-(U$2--)") (class "Default")
      (node (ref "R15") (pin "2") (pinfunction "2_2") (pintype "passive"))
      (node (ref "R16") (pin "1") (pinfunction "1_1") (pintype "passive"))
      (node (ref "U$2") (pin "PIN$3") (pinfunction "-_PIN$3") (pintype "bidirectional"))
    )
    (net (code "147") (name "Net-(U$2-ILIM)") (class "Default")
      (node (ref "R14") (pin "1") (pinfunction "1_1") (pintype "passive"))
      (node (ref "U$2") (pin "PIN$8") (pinfunction "ILIM_PIN$8") (pintype "bidirectional"))
    )
    (net (code "148") (name "Net-(U$3-+)") (class "Default")
      (node (ref "C121") (pin "2") (pinfunction "2_2") (pintype "passive"))
      (node (ref "C17") (pin "2") (pinfunction "2_2") (pintype "passive"))
      (node (ref "R187") (pin "1") (pinfunction "1_1") (pintype "passive"))
      (node (ref "R21") (pin "2") (pinfunction "2_2") (pintype "passive"))
      (node (ref "R24") (pin "2") (pinfunction "2_2") (pintype "passive"))
      (node (ref "U$3") (pin "PIN$4") (pinfunction "+_PIN$4") (pintype "bidirectional"))
    )
    (net (code "149") (name "Net-(U$3--)") (class "Default")
      (node (ref "R17") (pin "1") (pinfunction "1_1") (pintype "passive"))
      (node (ref "R19") (pin "1") (pinfunction "1_1") (pintype "passive"))
      (node (ref "R20") (pin "2") (pinfunction "2_2") (pintype "passive"))
      (node (ref "R23") (pin "2") (pinfunction "2_2") (pintype "passive"))
      (node (ref "U$3") (pin "PIN$3") (pinfunction "-_PIN$3") (pintype "bidirectional"))
    )
    (net (code "150") (name "Net-(U$3-ILIM)") (class "Default")
      (node (ref "R27") (pin "1") (pinfunction "1_1") (pintype "passive"))
      (node (ref "U$3") (pin "PIN$8") (pinfunction "ILIM_PIN$8") (pintype "bidirectional"))
    )
    (net (code "151") (name "Net-(U$4-+)") (class "Default")
      (node (ref "R29") (pin "2") (pinfunction "2_2") (pintype "passive"))
      (node (ref "R30") (pin "2") (pinfunction "2_2") (pintype "passive"))
      (node (ref "U$4") (pin "PIN$4") (pinfunction "+_PIN$4") (pintype "bidirectional"))
    )
    (net (code "152") (name "Net-(U$4--)") (class "Default")
      (node (ref "R32") (pin "2") (pinfunction "2_2") (pintype "passive"))
      (node (ref "R33") (pin "1") (pinfunction "1_1") (pintype "passive"))
      (node (ref "U$4") (pin "PIN$3") (pinfunction "-_PIN$3") (pintype "bidirectional"))
    )
    (net (code "153") (name "Net-(U$4-ILIM)") (class "Default")
      (node (ref "R31") (pin "1") (pinfunction "1_1") (pintype "passive"))
      (node (ref "U$4") (pin "PIN$8") (pinfunction "ILIM_PIN$8") (pintype "bidirectional"))
    )
    (net (code "154") (name "Net-(U$5-+)") (class "Default")
      (node (ref "C122") (pin "2") (pinfunction "2_2") (pintype "passive"))
      (node (ref "C28") (pin "2") (pinfunction "2_2") (pintype "passive"))
      (node (ref "R185") (pin "1") (pinfunction "1_1") (pintype "passive"))
      (node (ref "R40") (pin "2") (pinfunction "2_2") (pintype "passive"))
      (node (ref "R43") (pin "2") (pinfunction "2_2") (pintype "passive"))
      (node (ref "U$5") (pin "PIN$4") (pinfunction "+_PIN$4") (pintype "bidirectional"))
    )
    (net (code "155") (name "Net-(U$5--)") (class "Default")
      (node (ref "R37") (pin "1") (pinfunction "1_1") (pintype "passive"))
      (node (ref "R38") (pin "1") (pinfunction "1_1") (pintype "passive"))
      (node (ref "R39") (pin "2") (pinfunction "2_2") (pintype "passive"))
      (node (ref "R42") (pin "2") (pinfunction "2_2") (pintype "passive"))
      (node (ref "U$5") (pin "PIN$3") (pinfunction "-_PIN$3") (pintype "bidirectional"))
    )
    (net (code "156") (name "Net-(U$5-ILIM)") (class "Default")
      (node (ref "R46") (pin "1") (pinfunction "1_1") (pintype "passive"))
      (node (ref "U$5") (pin "PIN$8") (pinfunction "ILIM_PIN$8") (pintype "bidirectional"))
    )
    (net (code "157") (name "Net-(U$6-+)") (class "Default")
      (node (ref "R48") (pin "2") (pinfunction "2_2") (pintype "passive"))
      (node (ref "R49") (pin "2") (pinfunction "2_2") (pintype "passive"))
      (node (ref "U$6") (pin "PIN$4") (pinfunction "+_PIN$4") (pintype "bidirectional"))
    )
    (net (code "158") (name "Net-(U$6--)") (class "Default")
      (node (ref "R51") (pin "2") (pinfunction "2_2") (pintype "passive"))
      (node (ref "R52") (pin "1") (pinfunction "1_1") (pintype "passive"))
      (node (ref "U$6") (pin "PIN$3") (pinfunction "-_PIN$3") (pintype "bidirectional"))
    )
    (net (code "159") (name "Net-(U$6-ILIM)") (class "Default")
      (node (ref "R50") (pin "1") (pinfunction "1_1") (pintype "passive"))
      (node (ref "U$6") (pin "PIN$8") (pinfunction "ILIM_PIN$8") (pintype "bidirectional"))
    )
    (net (code "160") (name "Net-(U$7-+)") (class "Default")
      (node (ref "C123") (pin "2") (pinfunction "2_2") (pintype "passive"))
      (node (ref "C39") (pin "2") (pinfunction "2_2") (pintype "passive"))
      (node (ref "R192") (pin "1") (pinfunction "1_1") (pintype "passive"))
      (node (ref "R59") (pin "2") (pinfunction "2_2") (pintype "passive"))
      (node (ref "R62") (pin "2") (pinfunction "2_2") (pintype "passive"))
      (node (ref "U$7") (pin "PIN$4") (pinfunction "+_PIN$4") (pintype "bidirectional"))
    )
    (net (code "161") (name "Net-(U$7--)") (class "Default")
      (node (ref "R56") (pin "1") (pinfunction "1_1") (pintype "passive"))
      (node (ref "R57") (pin "1") (pinfunction "1_1") (pintype "passive"))
      (node (ref "R58") (pin "2") (pinfunction "2_2") (pintype "passive"))
      (node (ref "R61") (pin "2") (pinfunction "2_2") (pintype "passive"))
      (node (ref "U$7") (pin "PIN$3") (pinfunction "-_PIN$3") (pintype "bidirectional"))
    )
    (net (code "162") (name "Net-(U$7-ILIM)") (class "Default")
      (node (ref "R65") (pin "1") (pinfunction "1_1") (pintype "passive"))
      (node (ref "U$7") (pin "PIN$8") (pinfunction "ILIM_PIN$8") (pintype "bidirectional"))
    )
    (net (code "163") (name "Net-(U$8-+)") (class "Default")
      (node (ref "R67") (pin "2") (pinfunction "2_2") (pintype "passive"))
      (node (ref "R68") (pin "2") (pinfunction "2_2") (pintype "passive"))
      (node (ref "U$8") (pin "PIN$4") (pinfunction "+_PIN$4") (pintype "bidirectional"))
    )
    (net (code "164") (name "Net-(U$8--)") (class "Default")
      (node (ref "R70") (pin "2") (pinfunction "2_2") (pintype "passive"))
      (node (ref "R71") (pin "1") (pinfunction "1_1") (pintype "passive"))
      (node (ref "U$8") (pin "PIN$3") (pinfunction "-_PIN$3") (pintype "bidirectional"))
    )
    (net (code "165") (name "Net-(U$8-ILIM)") (class "Default")
      (node (ref "R69") (pin "1") (pinfunction "1_1") (pintype "passive"))
      (node (ref "U$8") (pin "PIN$8") (pinfunction "ILIM_PIN$8") (pintype "bidirectional"))
    )
    (net (code "166") (name "Net-(U$9-+)") (class "Default")
      (node (ref "C124") (pin "2") (pinfunction "2_2") (pintype "passive"))
      (node (ref "C50") (pin "2") (pinfunction "2_2") (pintype "passive"))
      (node (ref "R188") (pin "1") (pinfunction "1_1") (pintype "passive"))
      (node (ref "R78") (pin "2") (pinfunction "2_2") (pintype "passive"))
      (node (ref "R81") (pin "2") (pinfunction "2_2") (pintype "passive"))
      (node (ref "U$9") (pin "PIN$4") (pinfunction "+_PIN$4") (pintype "bidirectional"))
    )
    (net (code "167") (name "Net-(U$9--)") (class "Default")
      (node (ref "R75") (pin "1") (pinfunction "1_1") (pintype "passive"))
      (node (ref "R76") (pin "1") (pinfunction "1_1") (pintype "passive"))
      (node (ref "R77") (pin "2") (pinfunction "2_2") (pintype "passive"))
      (node (ref "R80") (pin "2") (pinfunction "2_2") (pintype "passive"))
      (node (ref "U$9") (pin "PIN$3") (pinfunction "-_PIN$3") (pintype "bidirectional"))
    )
    (net (code "168") (name "Net-(U$9-ILIM)") (class "Default")
      (node (ref "R84") (pin "1") (pinfunction "1_1") (pintype "passive"))
      (node (ref "U$9") (pin "PIN$8") (pinfunction "ILIM_PIN$8") (pintype "bidirectional"))
    )
    (net (code "169") (name "Net-(U$10-+)") (class "Default")
      (node (ref "R86") (pin "2") (pinfunction "2_2") (pintype "passive"))
      (node (ref "R87") (pin "2") (pinfunction "2_2") (pintype "passive"))
      (node (ref "U$10") (pin "PIN$4") (pinfunction "+_PIN$4") (pintype "bidirectional"))
    )
    (net (code "170") (name "Net-(U$10--)") (class "Default")
      (node (ref "R89") (pin "2") (pinfunction "2_2") (pintype "passive"))
      (node (ref "R90") (pin "1") (pinfunction "1_1") (pintype "passive"))
      (node (ref "U$10") (pin "PIN$3") (pinfunction "-_PIN$3") (pintype "bidirectional"))
    )
    (net (code "171") (name "Net-(U$10-ILIM)") (class "Default")
      (node (ref "R88") (pin "1") (pinfunction "1_1") (pintype "passive"))
      (node (ref "U$10") (pin "PIN$8") (pinfunction "ILIM_PIN$8") (pintype "bidirectional"))
    )
    (net (code "172") (name "Net-(U$11-+)") (class "Default")
      (node (ref "C125") (pin "2") (pinfunction "2_2") (pintype "passive"))
      (node (ref "C61") (pin "2") (pinfunction "2_2") (pintype "passive"))
      (node (ref "R100") (pin "2") (pinfunction "2_2") (pintype "passive"))
      (node (ref "R189") (pin "1") (pinfunction "1_1") (pintype "passive"))
      (node (ref "R97") (pin "2") (pinfunction "2_2") (pintype "passive"))
      (node (ref "U$11") (pin "PIN$4") (pinfunction "+_PIN$4") (pintype "bidirectional"))
    )
    (net (code "173") (name "Net-(U$11--)") (class "Default")
      (node (ref "R94") (pin "1") (pinfunction "1_1") (pintype "passive"))
      (node (ref "R95") (pin "1") (pinfunction "1_1") (pintype "passive"))
      (node (ref "R96") (pin "2") (pinfunction "2_2") (pintype "passive"))
      (node (ref "R99") (pin "2") (pinfunction "2_2") (pintype "passive"))
      (node (ref "U$11") (pin "PIN$3") (pinfunction "-_PIN$3") (pintype "bidirectional"))
    )
    (net (code "174") (name "Net-(U$11-ILIM)") (class "Default")
      (node (ref "R103") (pin "1") (pinfunction "1_1") (pintype "passive"))
      (node (ref "U$11") (pin "PIN$8") (pinfunction "ILIM_PIN$8") (pintype "bidirectional"))
    )
    (net (code "175") (name "Net-(U$12-+)") (class "Default")
      (node (ref "R105") (pin "2") (pinfunction "2_2") (pintype "passive"))
      (node (ref "R106") (pin "2") (pinfunction "2_2") (pintype "passive"))
      (node (ref "U$12") (pin "PIN$4") (pinfunction "+_PIN$4") (pintype "bidirectional"))
    )
    (net (code "176") (name "Net-(U$12--)") (class "Default")
      (node (ref "R108") (pin "2") (pinfunction "2_2") (pintype "passive"))
      (node (ref "R109") (pin "1") (pinfunction "1_1") (pintype "passive"))
      (node (ref "U$12") (pin "PIN$3") (pinfunction "-_PIN$3") (pintype "bidirectional"))
    )
    (net (code "177") (name "Net-(U$12-ILIM)") (class "Default")
      (node (ref "R107") (pin "1") (pinfunction "1_1") (pintype "passive"))
      (node (ref "U$12") (pin "PIN$8") (pinfunction "ILIM_PIN$8") (pintype "bidirectional"))
    )
    (net (code "178") (name "Net-(U$13-+)") (class "Default")
      (node (ref "C126") (pin "2") (pinfunction "2_2") (pintype "passive"))
      (node (ref "C72") (pin "2") (pinfunction "2_2") (pintype "passive"))
      (node (ref "R116") (pin "2") (pinfunction "2_2") (pintype "passive"))
      (node (ref "R119") (pin "2") (pinfunction "2_2") (pintype "passive"))
      (node (ref "R191") (pin "1") (pinfunction "1_1") (pintype "passive"))
      (node (ref "U$13") (pin "PIN$4") (pinfunction "+_PIN$4") (pintype "bidirectional"))
    )
    (net (code "179") (name "Net-(U$13--)") (class "Default")
      (node (ref "R113") (pin "1") (pinfunction "1_1") (pintype "passive"))
      (node (ref "R114") (pin "1") (pinfunction "1_1") (pintype "passive"))
      (node (ref "R115") (pin "2") (pinfunction "2_2") (pintype "passive"))
      (node (ref "R118") (pin "2") (pinfunction "2_2") (pintype "passive"))
      (node (ref "U$13") (pin "PIN$3") (pinfunction "-_PIN$3") (pintype "bidirectional"))
    )
    (net (code "180") (name "Net-(U$13-ILIM)") (class "Default")
      (node (ref "R122") (pin "1") (pinfunction "1_1") (pintype "passive"))
      (node (ref "U$13") (pin "PIN$8") (pinfunction "ILIM_PIN$8") (pintype "bidirectional"))
    )
    (net (code "181") (name "Net-(U$14-+)") (class "Default")
      (node (ref "R124") (pin "2") (pinfunction "2_2") (pintype "passive"))
      (node (ref "R125") (pin "2") (pinfunction "2_2") (pintype "passive"))
      (node (ref "U$14") (pin "PIN$4") (pinfunction "+_PIN$4") (pintype "bidirectional"))
    )
    (net (code "182") (name "Net-(U$14--)") (class "Default")
      (node (ref "R127") (pin "2") (pinfunction "2_2") (pintype "passive"))
      (node (ref "R128") (pin "1") (pinfunction "1_1") (pintype "passive"))
      (node (ref "U$14") (pin "PIN$3") (pinfunction "-_PIN$3") (pintype "bidirectional"))
    )
    (net (code "183") (name "Net-(U$14-ILIM)") (class "Default")
      (node (ref "R126") (pin "1") (pinfunction "1_1") (pintype "passive"))
      (node (ref "U$14") (pin "PIN$8") (pinfunction "ILIM_PIN$8") (pintype "bidirectional"))
    )
    (net (code "184") (name "Net-(U$15-+)") (class "Default")
      (node (ref "C127") (pin "2") (pinfunction "2_2") (pintype "passive"))
      (node (ref "C83") (pin "2") (pinfunction "2_2") (pintype "passive"))
      (node (ref "R135") (pin "2") (pinfunction "2_2") (pintype "passive"))
      (node (ref "R149") (pin "2") (pinfunction "2_2") (pintype "passive"))
      (node (ref "R190") (pin "1") (pinfunction "1_1") (pintype "passive"))
      (node (ref "U$15") (pin "PIN$4") (pinfunction "+_PIN$4") (pintype "bidirectional"))
    )
    (net (code "185") (name "Net-(U$15--)") (class "Default")
      (node (ref "R132") (pin "1") (pinfunction "1_1") (pintype "passive"))
      (node (ref "R133") (pin "1") (pinfunction "1_1") (pintype "passive"))
      (node (ref "R134") (pin "2") (pinfunction "2_2") (pintype "passive"))
      (node (ref "R148") (pin "2") (pinfunction "2_2") (pintype "passive"))
      (node (ref "U$15") (pin "PIN$3") (pinfunction "-_PIN$3") (pintype "bidirectional"))
    )
    (net (code "186") (name "Net-(U$15-ILIM)") (class "Default")
      (node (ref "R152") (pin "1") (pinfunction "1_1") (pintype "passive"))
      (node (ref "U$15") (pin "PIN$8") (pinfunction "ILIM_PIN$8") (pintype "bidirectional"))
    )
    (net (code "187") (name "Net-(U$16-+)") (class "Default")
      (node (ref "R154") (pin "2") (pinfunction "2_2") (pintype "passive"))
      (node (ref "R165") (pin "2") (pinfunction "2_2") (pintype "passive"))
      (node (ref "U$16") (pin "PIN$4") (pinfunction "+_PIN$4") (pintype "bidirectional"))
    )
    (net (code "188") (name "Net-(U$16--)") (class "Default")
      (node (ref "R167") (pin "2") (pinfunction "2_2") (pintype "passive"))
      (node (ref "R168") (pin "1") (pinfunction "1_1") (pintype "passive"))
      (node (ref "U$16") (pin "PIN$3") (pinfunction "-_PIN$3") (pintype "bidirectional"))
    )
    (net (code "189") (name "Net-(U$16-ILIM)") (class "Default")
      (node (ref "R166") (pin "1") (pinfunction "1_1") (pintype "passive"))
      (node (ref "U$16") (pin "PIN$8") (pinfunction "ILIM_PIN$8") (pintype "bidirectional"))
    )
    (net (code "190") (name "Net-(U2-ROS)") (class "Default")
      (node (ref "R164") (pin "2") (pinfunction "2_2") (pintype "passive"))
      (node (ref "U2") (pin "5") (pinfunction "ROS_5") (pintype "input"))
    )
    (net (code "191") (name "Net-(U2-VIN+)") (class "Default")
      (node (ref "C1") (pin "2") (pinfunction "2_2") (pintype "passive"))
      (node (ref "R1") (pin "2") (pinfunction "2_2") (pintype "passive"))
      (node (ref "R11") (pin "1") (pinfunction "1_1") (pintype "passive"))
      (node (ref "R15") (pin "1") (pinfunction "1_1") (pintype "passive"))
      (node (ref "U$1") (pin "PIN$1") (pinfunction "OUT_PIN$1") (pintype "bidirectional"))
      (node (ref "U$1") (pin "PIN$2") (pinfunction "OUT_PIN$2") (pintype "bidirectional"))
      (node (ref "U2") (pin "2") (pinfunction "VIN+_2") (pintype "input"))
    )
    (net (code "192") (name "Net-(U3-ROS)") (class "Default")
      (node (ref "R36") (pin "2") (pinfunction "2_2") (pintype "passive"))
      (node (ref "U3") (pin "5") (pinfunction "ROS_5") (pintype "input"))
    )
    (net (code "193") (name "Net-(U3-VIN+)") (class "Default")
      (node (ref "C16") (pin "2") (pinfunction "2_2") (pintype "passive"))
      (node (ref "R17") (pin "2") (pinfunction "2_2") (pintype "passive"))
      (node (ref "R28") (pin "1") (pinfunction "1_1") (pintype "passive"))
      (node (ref "R32") (pin "1") (pinfunction "1_1") (pintype "passive"))
      (node (ref "U$3") (pin "PIN$1") (pinfunction "OUT_PIN$1") (pintype "bidirectional"))
      (node (ref "U$3") (pin "PIN$2") (pinfunction "OUT_PIN$2") (pintype "bidirectional"))
      (node (ref "U3") (pin "2") (pinfunction "VIN+_2") (pintype "input"))
    )
    (net (code "194") (name "Net-(U6-ROS)") (class "Default")
      (node (ref "R55") (pin "2") (pinfunction "2_2") (pintype "passive"))
      (node (ref "U6") (pin "5") (pinfunction "ROS_5") (pintype "input"))
    )
    (net (code "195") (name "Net-(U6-VIN+)") (class "Default")
      (node (ref "C27") (pin "2") (pinfunction "2_2") (pintype "passive"))
      (node (ref "R37") (pin "2") (pinfunction "2_2") (pintype "passive"))
      (node (ref "R47") (pin "1") (pinfunction "1_1") (pintype "passive"))
      (node (ref "R51") (pin "1") (pinfunction "1_1") (pintype "passive"))
      (node (ref "U$5") (pin "PIN$1") (pinfunction "OUT_PIN$1") (pintype "bidirectional"))
      (node (ref "U$5") (pin "PIN$2") (pinfunction "OUT_PIN$2") (pintype "bidirectional"))
      (node (ref "U6") (pin "2") (pinfunction "VIN+_2") (pintype "input"))
    )
    (net (code "196") (name "Net-(U8-ROS)") (class "Default")
      (node (ref "R74") (pin "2") (pinfunction "2_2") (pintype "passive"))
      (node (ref "U8") (pin "5") (pinfunction "ROS_5") (pintype "input"))
    )
    (net (code "197") (name "Net-(U8-VIN+)") (class "Default")
      (node (ref "C38") (pin "2") (pinfunction "2_2") (pintype "passive"))
      (node (ref "R56") (pin "2") (pinfunction "2_2") (pintype "passive"))
      (node (ref "R66") (pin "1") (pinfunction "1_1") (pintype "passive"))
      (node (ref "R70") (pin "1") (pinfunction "1_1") (pintype "passive"))
      (node (ref "U$7") (pin "PIN$1") (pinfunction "OUT_PIN$1") (pintype "bidirectional"))
      (node (ref "U$7") (pin "PIN$2") (pinfunction "OUT_PIN$2") (pintype "bidirectional"))
      (node (ref "U8") (pin "2") (pinfunction "VIN+_2") (pintype "input"))
    )
    (net (code "198") (name "Net-(U9-REFCOMP)") (class "Default")
      (node (ref "C86") (pin "1") (pinfunction "1_1") (pintype "passive"))
      (node (ref "U9") (pin "4") (pinfunction "REFCOMP_4") (pintype "passive"))
    )
    (net (code "199") (name "Net-(U9-VOUTA)") (class "Default")
      (node (ref "R158") (pin "1") (pinfunction "1_1") (pintype "passive"))
      (node (ref "U9") (pin "2") (pinfunction "VOUTA_2") (pintype "output"))
    )
    (net (code "200") (name "Net-(U9-VOUTB)") (class "Default")
      (node (ref "R157") (pin "1") (pinfunction "1_1") (pintype "passive"))
      (node (ref "U9") (pin "3") (pinfunction "VOUTB_3") (pintype "output"))
    )
    (net (code "201") (name "Net-(U9-VOUTC)") (class "Default")
      (node (ref "R156") (pin "1") (pinfunction "1_1") (pintype "passive"))
      (node (ref "U9") (pin "5") (pinfunction "VOUTC_5") (pintype "output"))
    )
    (net (code "202") (name "Net-(U9-VOUTD)") (class "Default")
      (node (ref "R155") (pin "1") (pinfunction "1_1") (pintype "passive"))
      (node (ref "U9") (pin "6") (pinfunction "VOUTD_6") (pintype "output"))
    )
    (net (code "203") (name "Net-(U9-VOUTE)") (class "Default")
      (node (ref "R162") (pin "1") (pinfunction "1_1") (pintype "passive"))
      (node (ref "U9") (pin "15") (pinfunction "VOUTE_15") (pintype "output"))
    )
    (net (code "204") (name "Net-(U9-VOUTF)") (class "Default")
      (node (ref "R161") (pin "1") (pinfunction "1_1") (pintype "passive"))
      (node (ref "U9") (pin "16") (pinfunction "VOUTF_16") (pintype "output"))
    )
    (net (code "205") (name "Net-(U9-VOUTG)") (class "Default")
      (node (ref "R160") (pin "1") (pinfunction "1_1") (pintype "passive"))
      (node (ref "U9") (pin "17") (pinfunction "VOUTG_17") (pintype "output"))
    )
    (net (code "206") (name "Net-(U9-VOUTH)") (class "Default")
      (node (ref "R159") (pin "1") (pinfunction "1_1") (pintype "passive"))
      (node (ref "U9") (pin "18") (pinfunction "VOUTH_18") (pintype "output"))
    )
    (net (code "207") (name "Net-(U9-~{CLR})") (class "Default")
      (node (ref "R163") (pin "2") (pinfunction "2_2") (pintype "passive"))
      (node (ref "R184") (pin "2") (pinfunction "2_2") (pintype "passive"))
      (node (ref "U9") (pin "13") (pinfunction "~{CLR}_13") (pintype "input"))
    )
    (net (code "208") (name "Net-(U10-REFCOMP)") (class "Default")
      (node (ref "C87") (pin "1") (pinfunction "1_1") (pintype "passive"))
      (node (ref "C95") (pin "1") (pinfunction "1_1") (pintype "passive"))
      (node (ref "U10") (pin "9") (pinfunction "REFCOMP_9") (pintype "output"))
    )
    (net (code "209") (name "Net-(U10-VREF)") (class "Default")
      (node (ref "C88") (pin "1") (pinfunction "1_1") (pintype "passive"))
      (node (ref "C96") (pin "1") (pinfunction "1_1") (pintype "passive"))
      (node (ref "U10") (pin "10") (pinfunction "VREF_10") (pintype "output"))
    )
    (net (code "210") (name "Net-(U13-ROS)") (class "Default")
      (node (ref "R93") (pin "2") (pinfunction "2_2") (pintype "passive"))
      (node (ref "U13") (pin "5") (pinfunction "ROS_5") (pintype "input"))
    )
    (net (code "211") (name "Net-(U13-VIN+)") (class "Default")
      (node (ref "C49") (pin "2") (pinfunction "2_2") (pintype "passive"))
      (node (ref "R75") (pin "2") (pinfunction "2_2") (pintype "passive"))
      (node (ref "R85") (pin "1") (pinfunction "1_1") (pintype "passive"))
      (node (ref "R89") (pin "1") (pinfunction "1_1") (pintype "passive"))
      (node (ref "U$9") (pin "PIN$1") (pinfunction "OUT_PIN$1") (pintype "bidirectional"))
      (node (ref "U$9") (pin "PIN$2") (pinfunction "OUT_PIN$2") (pintype "bidirectional"))
      (node (ref "U13") (pin "2") (pinfunction "VIN+_2") (pintype "input"))
    )
    (net (code "212") (name "Net-(U15-ROS)") (class "Default")
      (node (ref "R112") (pin "2") (pinfunction "2_2") (pintype "passive"))
      (node (ref "U15") (pin "5") (pinfunction "ROS_5") (pintype "input"))
    )
    (net (code "213") (name "Net-(U15-VIN+)") (class "Default")
      (node (ref "C60") (pin "2") (pinfunction "2_2") (pintype "passive"))
      (node (ref "R104") (pin "1") (pinfunction "1_1") (pintype "passive"))
      (node (ref "R108") (pin "1") (pinfunction "1_1") (pintype "passive"))
      (node (ref "R94") (pin "2") (pinfunction "2_2") (pintype "passive"))
      (node (ref "U$11") (pin "PIN$1") (pinfunction "OUT_PIN$1") (pintype "bidirectional"))
      (node (ref "U$11") (pin "PIN$2") (pinfunction "OUT_PIN$2") (pintype "bidirectional"))
      (node (ref "U15") (pin "2") (pinfunction "VIN+_2") (pintype "input"))
    )
    (net (code "214") (name "Net-(U17-ROS)") (class "Default")
      (node (ref "R131") (pin "2") (pinfunction "2_2") (pintype "passive"))
      (node (ref "U17") (pin "5") (pinfunction "ROS_5") (pintype "input"))
    )
    (net (code "215") (name "Net-(U17-VIN+)") (class "Default")
      (node (ref "C71") (pin "2") (pinfunction "2_2") (pintype "passive"))
      (node (ref "R113") (pin "2") (pinfunction "2_2") (pintype "passive"))
      (node (ref "R123") (pin "1") (pinfunction "1_1") (pintype "passive"))
      (node (ref "R127") (pin "1") (pinfunction "1_1") (pintype "passive"))
      (node (ref "U$13") (pin "PIN$1") (pinfunction "OUT_PIN$1") (pintype "bidirectional"))
      (node (ref "U$13") (pin "PIN$2") (pinfunction "OUT_PIN$2") (pintype "bidirectional"))
      (node (ref "U17") (pin "2") (pinfunction "VIN+_2") (pintype "input"))
    )
    (net (code "216") (name "Net-(U19-ROS)") (class "Default")
      (node (ref "R171") (pin "2") (pinfunction "2_2") (pintype "passive"))
      (node (ref "U19") (pin "5") (pinfunction "ROS_5") (pintype "input"))
    )
    (net (code "217") (name "Net-(U19-VIN+)") (class "Default")
      (node (ref "C82") (pin "2") (pinfunction "2_2") (pintype "passive"))
      (node (ref "R132") (pin "2") (pinfunction "2_2") (pintype "passive"))
      (node (ref "R153") (pin "1") (pinfunction "1_1") (pintype "passive"))
      (node (ref "R167") (pin "1") (pinfunction "1_1") (pintype "passive"))
      (node (ref "U$15") (pin "PIN$1") (pinfunction "OUT_PIN$1") (pintype "bidirectional"))
      (node (ref "U$15") (pin "PIN$2") (pinfunction "OUT_PIN$2") (pintype "bidirectional"))
      (node (ref "U19") (pin "2") (pinfunction "VIN+_2") (pintype "input"))
    )
    (net (code "218") (name "SCK_MS") (class "Default")
      (node (ref "IC6") (pin "8") (pinfunction "A4_8") (pintype "input"))
      (node (ref "R175") (pin "1") (pinfunction "1_1") (pintype "passive"))
      (node (ref "U026") (pin "11") (pinfunction "OUT1_11") (pintype "bidirectional"))
      (node (ref "U10") (pin "12") (pinfunction "SCK_12") (pintype "input"))
      (node (ref "U9") (pin "10") (pinfunction "SCK_10") (pintype "input"))
    )
    (net (code "219") (name "SCK_MS_A") (class "Default")
      (node (ref "R172") (pin "1") (pinfunction "1_1") (pintype "passive"))
      (node (ref "U021") (pin "6") (pinfunction "INB1_6") (pintype "bidirectional"))
      (node (ref "X002") (pin "5") (pinfunction "5_5") (pintype "passive"))
    )
    (net (code "220") (name "SCK_MS_B") (class "Default")
      (node (ref "R172") (pin "2") (pinfunction "2_2") (pintype "passive"))
      (node (ref "U021") (pin "5") (pinfunction "INB2_5") (pintype "bidirectional"))
      (node (ref "X002") (pin "4") (pinfunction "4_4") (pintype "passive"))
    )
    (net (code "221") (name "SCK_MS_I") (class "Default")
      (node (ref "R180") (pin "1") (pinfunction "1_1") (pintype "passive"))
      (node (ref "U021") (pin "3") (pinfunction "OUTB_3") (pintype "bidirectional"))
      (node (ref "U043") (pin "2") (pinfunction "C_2") (pintype "passive"))
    )
    (net (code "222") (name "SCK_MS_II") (class "Default")
      (node (ref "R180") (pin "2") (pinfunction "2_2") (pintype "passive"))
      (node (ref "U026") (pin "6") (pinfunction "CATH1_6") (pintype "bidirectional"))
      (node (ref "U043") (pin "1") (pinfunction "A_1") (pintype "passive"))
    )
    (net (code "223") (name "SCK_SM") (class "Default")
      (node (ref "IC6") (pin "12") (pinfunction "Y4_12") (pintype "tri_state"))
      (node (ref "R182") (pin "2") (pinfunction "2_2") (pintype "passive"))
      (node (ref "U045") (pin "2") (pinfunction "C_2") (pintype "passive"))
    )
    (net (code "224") (name "SCK_SM_A") (class "Default")
      (node (ref "U011") (pin "8") (pinfunction "OUTA1_8") (pintype "bidirectional"))
      (node (ref "X002") (pin "6") (pinfunction "6_6") (pintype "passive"))
    )
    (net (code "225") (name "SCK_SM_B") (class "Default")
      (node (ref "U011") (pin "7") (pinfunction "OUTA2_7") (pintype "bidirectional"))
      (node (ref "X002") (pin "3") (pinfunction "3_3") (pintype "passive"))
    )
    (net (code "226") (name "SCK_SM_I") (class "Default")
      (node (ref "R174") (pin "1") (pinfunction "1_1") (pintype "passive"))
      (node (ref "U011") (pin "2") (pinfunction "INA_2") (pintype "bidirectional"))
      (node (ref "U026") (pin "3") (pinfunction "OUT3_3") (pintype "bidirectional"))
    )
    (net (code "227") (name "SCK_SM_II") (class "Default")
      (node (ref "R182") (pin "1") (pinfunction "1_1") (pintype "passive"))
      (node (ref "U026") (pin "14") (pinfunction "AN3_14") (pintype "bidirectional"))
      (node (ref "U045") (pin "1") (pinfunction "A_1") (pintype "passive"))
    )
    (net (code "228") (name "VCC") (class "Default")
      (node (ref "C100") (pin "1") (pinfunction "1_1") (pintype "passive"))
      (node (ref "C11") (pin "+") (pinfunction "+_+") (pintype "passive"))
      (node (ref "C110") (pin "1") (pinfunction "1_1") (pintype "passive"))
      (node (ref "C111") (pin "1") (pinfunction "1_1") (pintype "passive"))
      (node (ref "C112") (pin "1") (pinfunction "1_1") (pintype "passive"))
      (node (ref "C113") (pin "1") (pinfunction "1_1") (pintype "passive"))
      (node (ref "C114") (pin "1") (pinfunction "1_1") (pintype "passive"))
      (node (ref "C115") (pin "1") (pinfunction "1_1") (pintype "passive"))
      (node (ref "C12") (pin "+") (pinfunction "+_+") (pintype "passive"))
      (node (ref "C13") (pin "+") (pinfunction "+_+") (pintype "passive"))
      (node (ref "C14") (pin "+") (pinfunction "+_+") (pintype "passive"))
      (node (ref "C19") (pin "1") (pinfunction "1_1") (pintype "passive"))
      (node (ref "C20") (pin "1") (pinfunction "1_1") (pintype "passive"))
      (node (ref "C21") (pin "1") (pinfunction "1_1") (pintype "passive"))
      (node (ref "C22") (pin "1") (pinfunction "1_1") (pintype "passive"))
      (node (ref "C23") (pin "1") (pinfunction "1_1") (pintype "passive"))
      (node (ref "C24") (pin "1") (pinfunction "1_1") (pintype "passive"))
      (node (ref "C30") (pin "1") (pinfunction "1_1") (pintype "passive"))
      (node (ref "C31") (pin "1") (pinfunction "1_1") (pintype "passive"))
      (node (ref "C32") (pin "1") (pinfunction "1_1") (pintype "passive"))
      (node (ref "C33") (pin "1") (pinfunction "1_1") (pintype "passive"))
      (node (ref "C34") (pin "1") (pinfunction "1_1") (pintype "passive"))
      (node (ref "C35") (pin "1") (pinfunction "1_1") (pintype "passive"))
      (node (ref "C4") (pin "1") (pinfunction "1_1") (pintype "passive"))
      (node (ref "C41") (pin "1") (pinfunction "1_1") (pintype "passive"))
      (node (ref "C42") (pin "1") (pinfunction "1_1") (pintype "passive"))
      (node (ref "C43") (pin "1") (pinfunction "1_1") (pintype "passive"))
      (node (ref "C44") (pin "1") (pinfunction "1_1") (pintype "passive"))
      (node (ref "C45") (pin "1") (pinfunction "1_1") (pintype "passive"))
      (node (ref "C46") (pin "1") (pinfunction "1_1") (pintype "passive"))
      (node (ref "C5") (pin "1") (pinfunction "1_1") (pintype "passive"))
      (node (ref "C52") (pin "1") (pinfunction "1_1") (pintype "passive"))
      (node (ref "C53") (pin "1") (pinfunction "1_1") (pintype "passive"))
      (node (ref "C54") (pin "1") (pinfunction "1_1") (pintype "passive"))
      (node (ref "C55") (pin "1") (pinfunction "1_1") (pintype "passive"))
      (node (ref "C56") (pin "1") (pinfunction "1_1") (pintype "passive"))
      (node (ref "C57") (pin "1") (pinfunction "1_1") (pintype "passive"))
      (node (ref "C6") (pin "1") (pinfunction "1_1") (pintype "passive"))
      (node (ref "C63") (pin "1") (pinfunction "1_1") (pintype "passive"))
      (node (ref "C64") (pin "1") (pinfunction "1_1") (pintype "passive"))
      (node (ref "C65") (pin "1") (pinfunction "1_1") (pintype "passive"))
      (node (ref "C66") (pin "1") (pinfunction "1_1") (pintype "passive"))
      (node (ref "C67") (pin "1") (pinfunction "1_1") (pintype "passive"))
      (node (ref "C68") (pin "1") (pinfunction "1_1") (pintype "passive"))
      (node (ref "C7") (pin "1") (pinfunction "1_1") (pintype "passive"))
      (node (ref "C74") (pin "1") (pinfunction "1_1") (pintype "passive"))
      (node (ref "C75") (pin "1") (pinfunction "1_1") (pintype "passive"))
      (node (ref "C76") (pin "1") (pinfunction "1_1") (pintype "passive"))
      (node (ref "C77") (pin "1") (pinfunction "1_1") (pintype "passive"))
      (node (ref "C78") (pin "1") (pinfunction "1_1") (pintype "passive"))
      (node (ref "C79") (pin "1") (pinfunction "1_1") (pintype "passive"))
      (node (ref "C8") (pin "1") (pinfunction "1_1") (pintype "passive"))
      (node (ref "C9") (pin "1") (pinfunction "1_1") (pintype "passive"))
      (node (ref "IC1") (pin "1") (pinfunction "VI_1") (pintype "input"))
      (node (ref "LED1") (pin "A") (pinfunction "A_A") (pintype "passive"))
      (node (ref "R105") (pin "1") (pinfunction "1_1") (pintype "passive"))
      (node (ref "R12") (pin "1") (pinfunction "1_1") (pintype "passive"))
      (node (ref "R124") (pin "1") (pinfunction "1_1") (pintype "passive"))
      (node (ref "R154") (pin "1") (pinfunction "1_1") (pintype "passive"))
      (node (ref "R29") (pin "1") (pinfunction "1_1") (pintype "passive"))
      (node (ref "R48") (pin "1") (pinfunction "1_1") (pintype "passive"))
      (node (ref "R67") (pin "1") (pinfunction "1_1") (pintype "passive"))
      (node (ref "R86") (pin "1") (pinfunction "1_1") (pintype "passive"))
      (node (ref "U$1") (pin "PIN$10") (pinfunction "V+_PIN$10") (pintype "bidirectional"))
      (node (ref "U$1") (pin "PIN$11") (pinfunction "V+_PIN$11") (pintype "bidirectional"))
      (node (ref "U$10") (pin "PIN$10") (pinfunction "V+_PIN$10") (pintype "bidirectional"))
      (node (ref "U$10") (pin "PIN$11") (pinfunction "V+_PIN$11") (pintype "bidirectional"))
      (node (ref "U$11") (pin "PIN$10") (pinfunction "V+_PIN$10") (pintype "bidirectional"))
      (node (ref "U$11") (pin "PIN$11") (pinfunction "V+_PIN$11") (pintype "bidirectional"))
      (node (ref "U$12") (pin "PIN$10") (pinfunction "V+_PIN$10") (pintype "bidirectional"))
      (node (ref "U$12") (pin "PIN$11") (pinfunction "V+_PIN$11") (pintype "bidirectional"))
      (node (ref "U$13") (pin "PIN$10") (pinfunction "V+_PIN$10") (pintype "bidirectional"))
      (node (ref "U$13") (pin "PIN$11") (pinfunction "V+_PIN$11") (pintype "bidirectional"))
      (node (ref "U$14") (pin "PIN$10") (pinfunction "V+_PIN$10") (pintype "bidirectional"))
      (node (ref "U$14") (pin "PIN$11") (pinfunction "V+_PIN$11") (pintype "bidirectional"))
      (node (ref "U$15") (pin "PIN$10") (pinfunction "V+_PIN$10") (pintype "bidirectional"))
      (node (ref "U$15") (pin "PIN$11") (pinfunction "V+_PIN$11") (pintype "bidirectional"))
      (node (ref "U$16") (pin "PIN$10") (pinfunction "V+_PIN$10") (pintype "bidirectional"))
      (node (ref "U$16") (pin "PIN$11") (pinfunction "V+_PIN$11") (pintype "bidirectional"))
      (node (ref "U$2") (pin "PIN$10") (pinfunction "V+_PIN$10") (pintype "bidirectional"))
      (node (ref "U$2") (pin "PIN$11") (pinfunction "V+_PIN$11") (pintype "bidirectional"))
      (node (ref "U$3") (pin "PIN$10") (pinfunction "V+_PIN$10") (pintype "bidirectional"))
      (node (ref "U$3") (pin "PIN$11") (pinfunction "V+_PIN$11") (pintype "bidirectional"))
      (node (ref "U$4") (pin "PIN$10") (pinfunction "V+_PIN$10") (pintype "bidirectional"))
      (node (ref "U$4") (pin "PIN$11") (pinfunction "V+_PIN$11") (pintype "bidirectional"))
      (node (ref "U$5") (pin "PIN$10") (pinfunction "V+_PIN$10") (pintype "bidirectional"))
      (node (ref "U$5") (pin "PIN$11") (pinfunction "V+_PIN$11") (pintype "bidirectional"))
      (node (ref "U$6") (pin "PIN$10") (pinfunction "V+_PIN$10") (pintype "bidirectional"))
      (node (ref "U$6") (pin "PIN$11") (pinfunction "V+_PIN$11") (pintype "bidirectional"))
      (node (ref "U$7") (pin "PIN$10") (pinfunction "V+_PIN$10") (pintype "bidirectional"))
      (node (ref "U$7") (pin "PIN$11") (pinfunction "V+_PIN$11") (pintype "bidirectional"))
      (node (ref "U$8") (pin "PIN$10") (pinfunction "V+_PIN$10") (pintype "bidirectional"))
      (node (ref "U$8") (pin "PIN$11") (pinfunction "V+_PIN$11") (pintype "bidirectional"))
      (node (ref "U$9") (pin "PIN$10") (pinfunction "V+_PIN$10") (pintype "bidirectional"))
      (node (ref "U$9") (pin "PIN$11") (pinfunction "V+_PIN$11") (pintype "bidirectional"))
      (node (ref "U031") (pin "P$2") (pinfunction "2_P$2") (pintype "passive"))
    )
    (net (code "229") (name "unconnected-(IC4A-Y4-Pad11)") (class "Default")
      (node (ref "IC4") (pin "11") (pinfunction "Y4_11") (pintype "output"))
    )
    (net (code "230") (name "unconnected-(IC4A-Y5-Pad10)") (class "Default")
      (node (ref "IC4") (pin "10") (pinfunction "Y5_10") (pintype "output"))
    )
    (net (code "231") (name "unconnected-(IC4A-Y6-Pad9)") (class "Default")
      (node (ref "IC4") (pin "9") (pinfunction "Y6_9") (pintype "output"))
    )
    (net (code "232") (name "unconnected-(IC4A-Y7-Pad7)") (class "Default")
      (node (ref "IC4") (pin "7") (pinfunction "Y7_7") (pintype "output"))
    )
    (net (code "233") (name "unconnected-(IC6B-A1-Pad11)") (class "Default")
      (node (ref "IC6") (pin "11") (pinfunction "A1_11") (pintype "input"))
    )
    (net (code "234") (name "unconnected-(IC6B-A2-Pad13)") (class "Default")
      (node (ref "IC6") (pin "13") (pinfunction "A2_13") (pintype "input"))
    )
    (net (code "235") (name "unconnected-(IC6B-A3-Pad15)") (class "Default")
      (node (ref "IC6") (pin "15") (pinfunction "A3_15") (pintype "input"))
    )
    (net (code "236") (name "unconnected-(IC6B-Y1-Pad9)") (class "Default")
      (node (ref "IC6") (pin "9") (pinfunction "Y1_9") (pintype "tri_state"))
    )
    (net (code "237") (name "unconnected-(IC6B-Y2-Pad7)") (class "Default")
      (node (ref "IC6") (pin "7") (pinfunction "Y2_7") (pintype "tri_state"))
    )
    (net (code "238") (name "unconnected-(IC6B-Y3-Pad5)") (class "Default")
      (node (ref "IC6") (pin "5") (pinfunction "Y3_5") (pintype "tri_state"))
    )
    (net (code "239") (name "unconnected-(U001-INB1-Pad6)") (class "Default")
      (node (ref "U001") (pin "6") (pinfunction "INB1_6") (pintype "bidirectional"))
    )
    (net (code "240") (name "unconnected-(U001-INB2-Pad5)") (class "Default")
      (node (ref "U001") (pin "5") (pinfunction "INB2_5") (pintype "bidirectional"))
    )
    (net (code "241") (name "unconnected-(U001-OUTB-Pad3)") (class "Default")
      (node (ref "U001") (pin "3") (pinfunction "OUTB_3") (pintype "bidirectional"))
    )
    (net (code "242") (name "unconnected-(U2-NC-Pad7)") (class "Default")
      (node (ref "U2") (pin "7") (pinfunction "NC_7") (pintype "no_connect"))
    )
    (net (code "243") (name "unconnected-(U3-NC-Pad7)") (class "Default")
      (node (ref "U3") (pin "7") (pinfunction "NC_7") (pintype "no_connect"))
    )
    (net (code "244") (name "unconnected-(U6-NC-Pad7)") (class "Default")
      (node (ref "U6") (pin "7") (pinfunction "NC_7") (pintype "no_connect"))
    )
    (net (code "245") (name "unconnected-(U8-NC-Pad7)") (class "Default")
      (node (ref "U8") (pin "7") (pinfunction "NC_7") (pintype "no_connect"))
    )
    (net (code "246") (name "unconnected-(U9-SDO-Pad12)") (class "Default")
      (node (ref "U9") (pin "12") (pinfunction "SDO_12") (pintype "output"))
    )
    (net (code "247") (name "unconnected-(U13-NC-Pad7)") (class "Default")
      (node (ref "U13") (pin "7") (pinfunction "NC_7") (pintype "no_connect"))
    )
    (net (code "248") (name "unconnected-(U15-NC-Pad7)") (class "Default")
      (node (ref "U15") (pin "7") (pinfunction "NC_7") (pintype "no_connect"))
    )
    (net (code "249") (name "unconnected-(U17-NC-Pad7)") (class "Default")
      (node (ref "U17") (pin "7") (pinfunction "NC_7") (pintype "no_connect"))
    )
    (net (code "250") (name "unconnected-(U19-NC-Pad7)") (class "Default")
      (node (ref "U19") (pin "7") (pinfunction "NC_7") (pintype "no_connect"))
    )
    (net (code "251") (name "unconnected-(U025-AN4-Pad7)") (class "Default")
      (node (ref "U025") (pin "7") (pinfunction "AN4_7") (pintype "bidirectional"))
    )
    (net (code "252") (name "unconnected-(U025-CATH4-Pad8)") (class "Default")
      (node (ref "U025") (pin "8") (pinfunction "CATH4_8") (pintype "bidirectional"))
    )
    (net (code "253") (name "unconnected-(U025-OUT4-Pad11)") (class "Default")
      (node (ref "U025") (pin "11") (pinfunction "OUT4_11") (pintype "bidirectional"))
    )
  )
)
